# AK4493-Combi.net
KiCad netlist of a schematic drawn in EAGLE
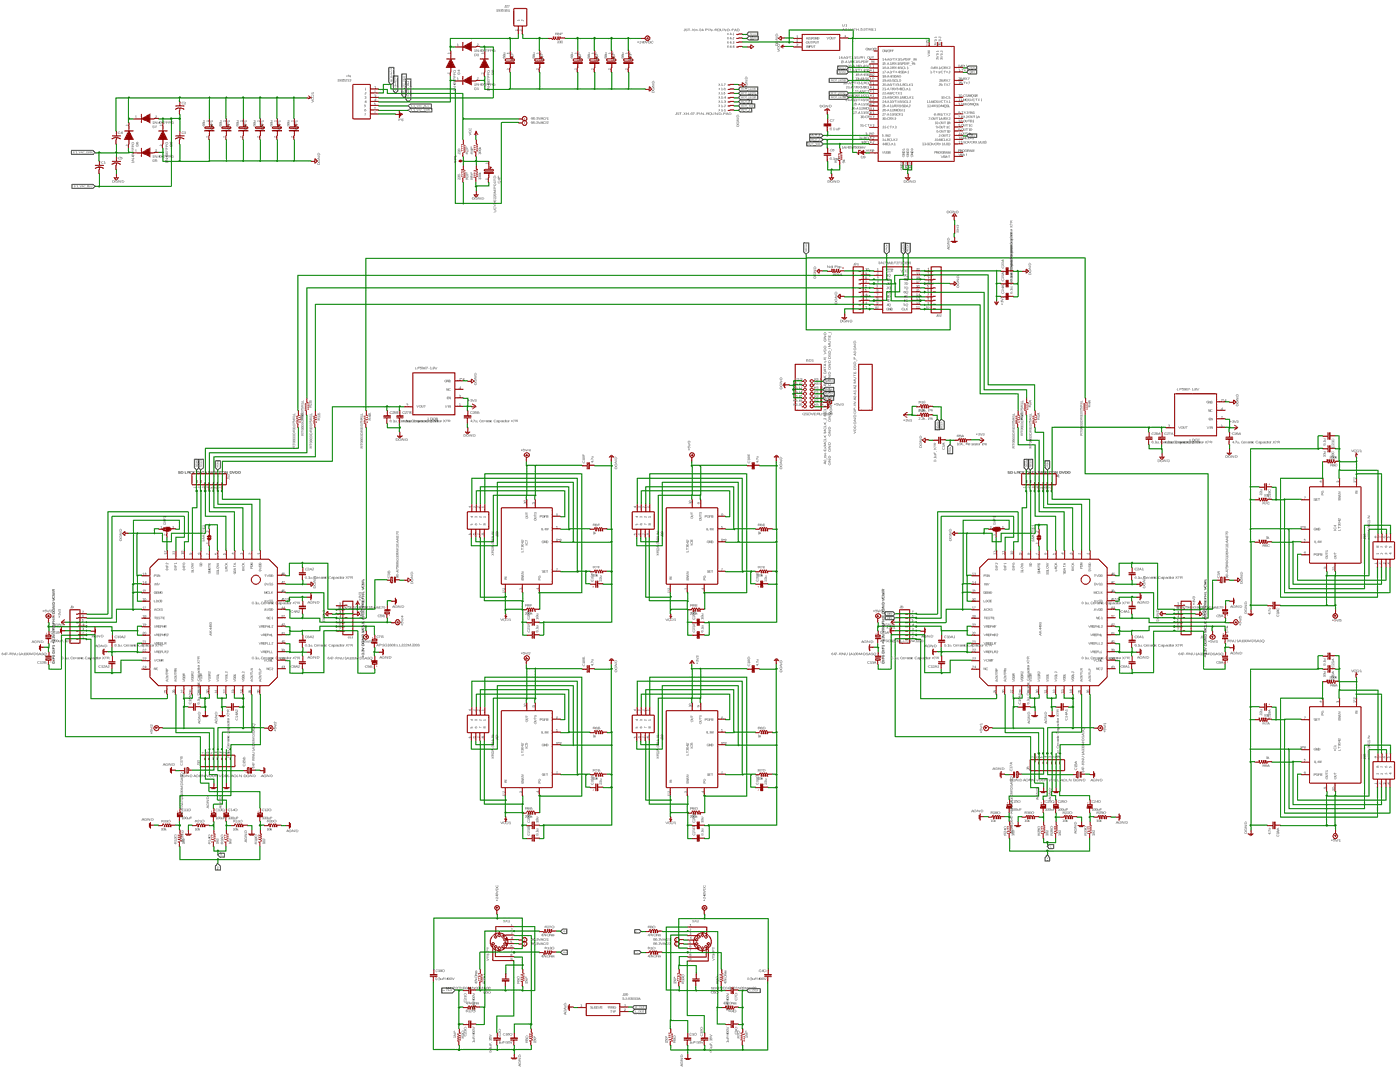
[diagram p0: schematic, sheet 1, overview]
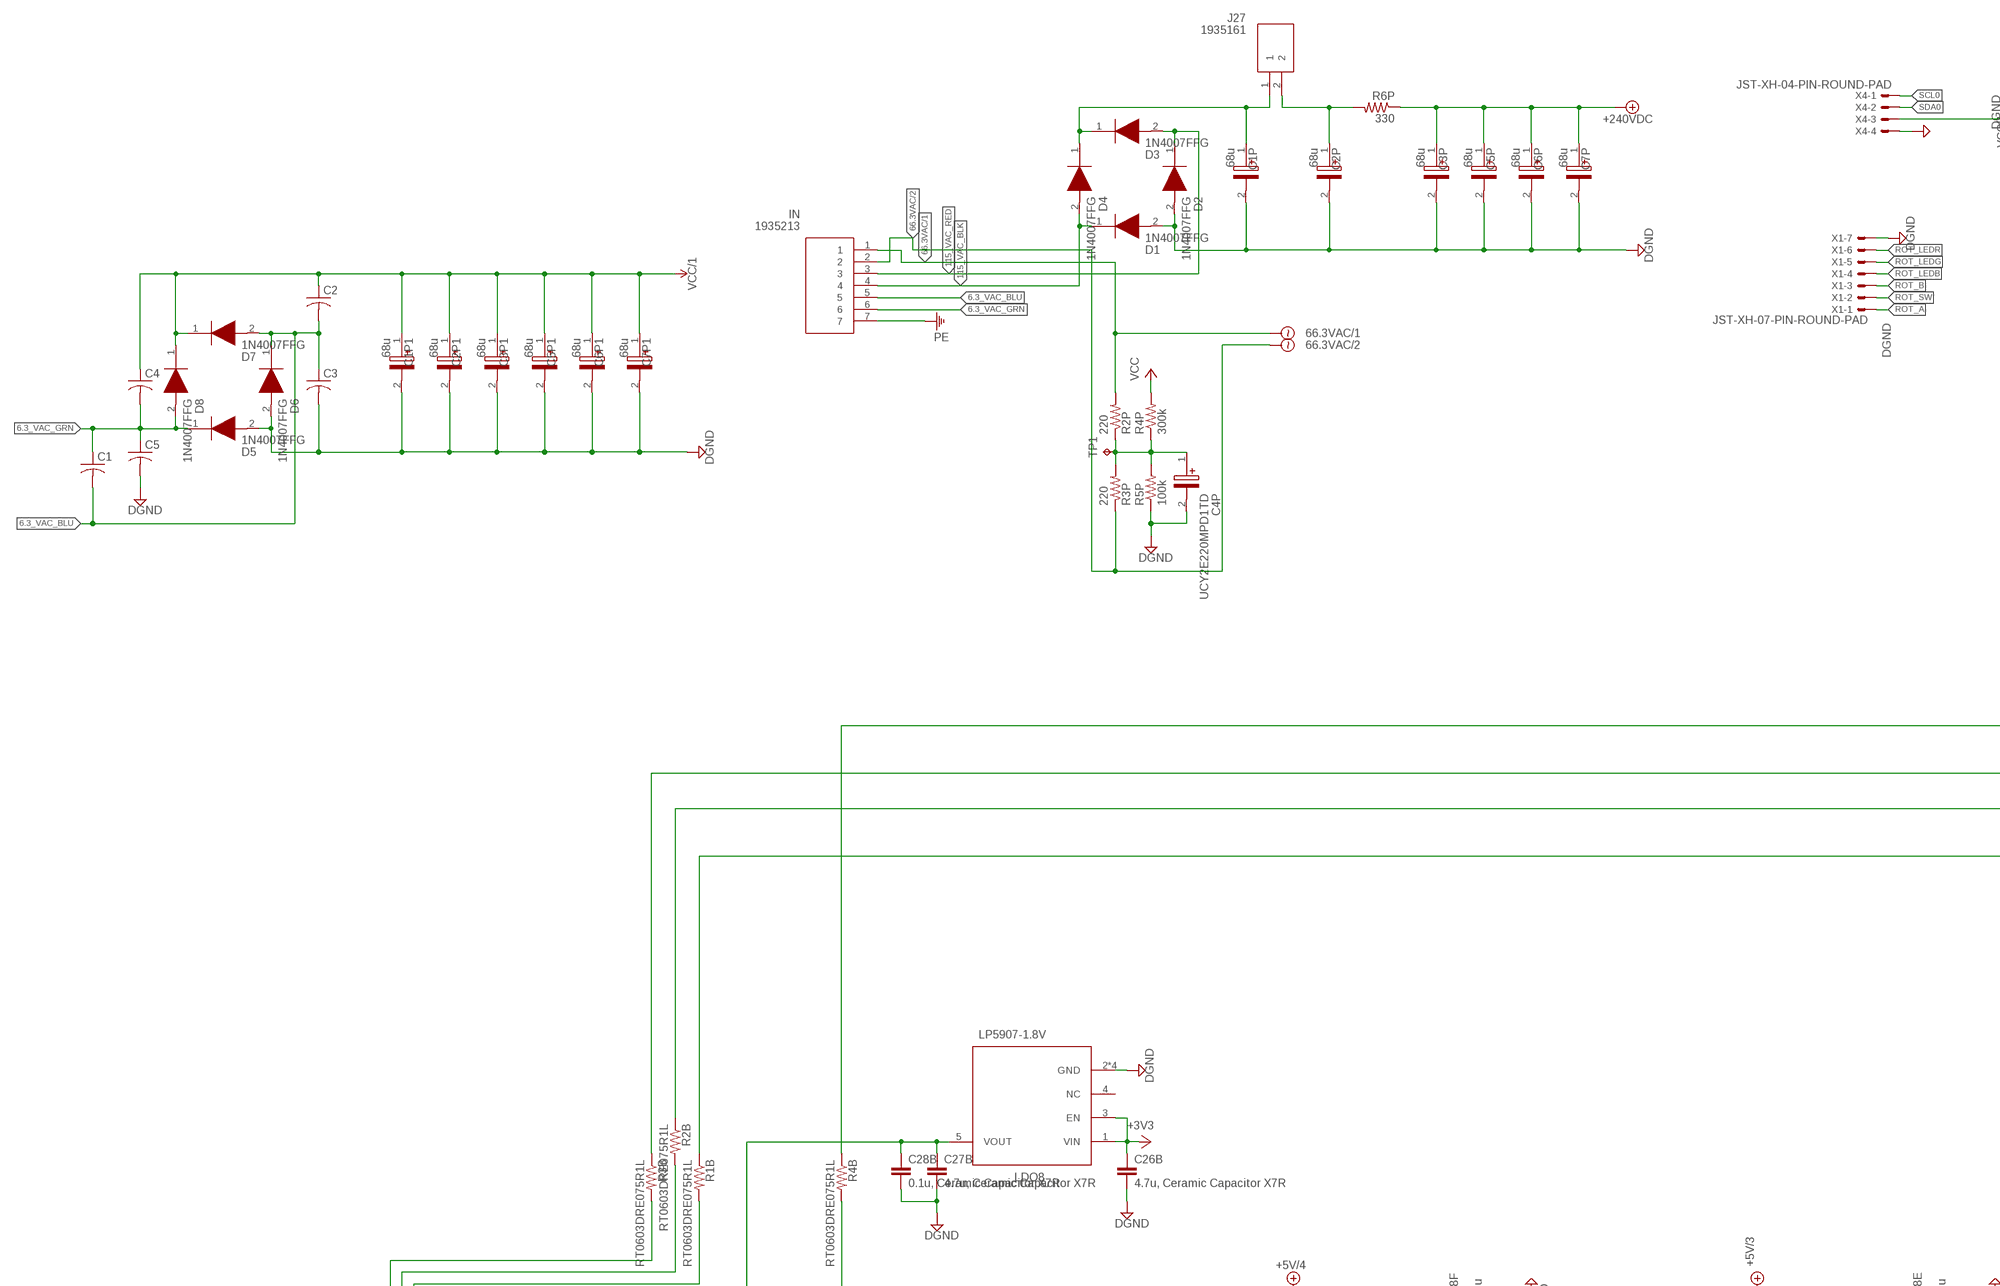
[diagram p1: schematic, sheet 1, part 1 of 4]
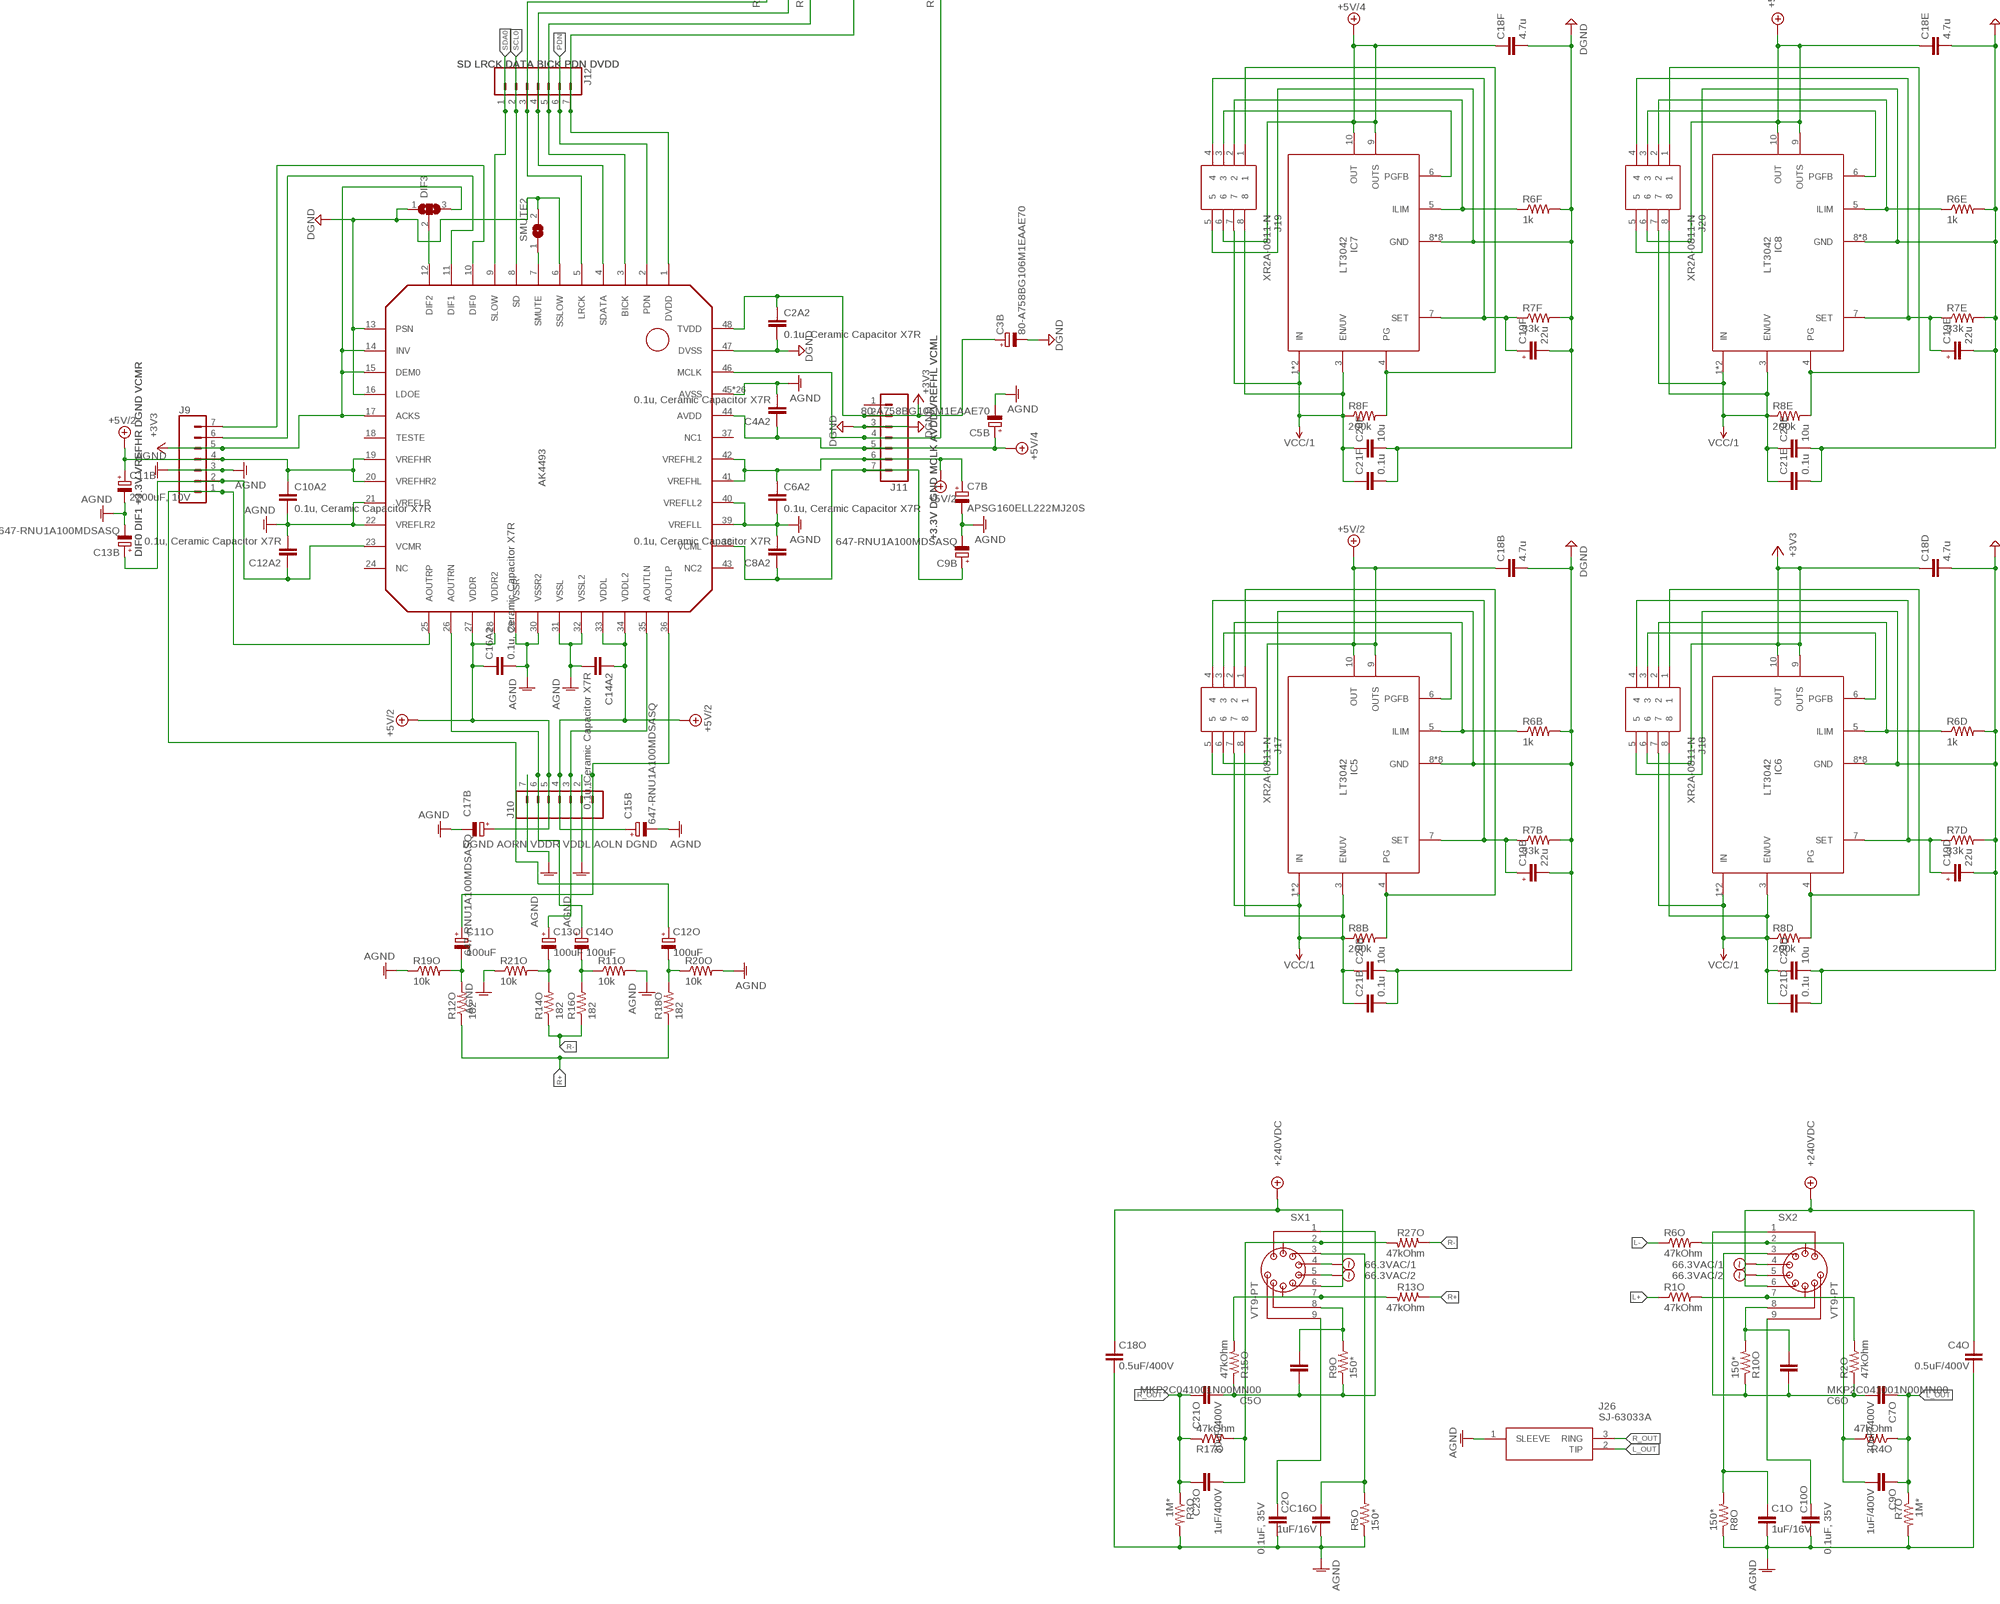
[diagram p2: schematic, sheet 1, part 2 of 4]
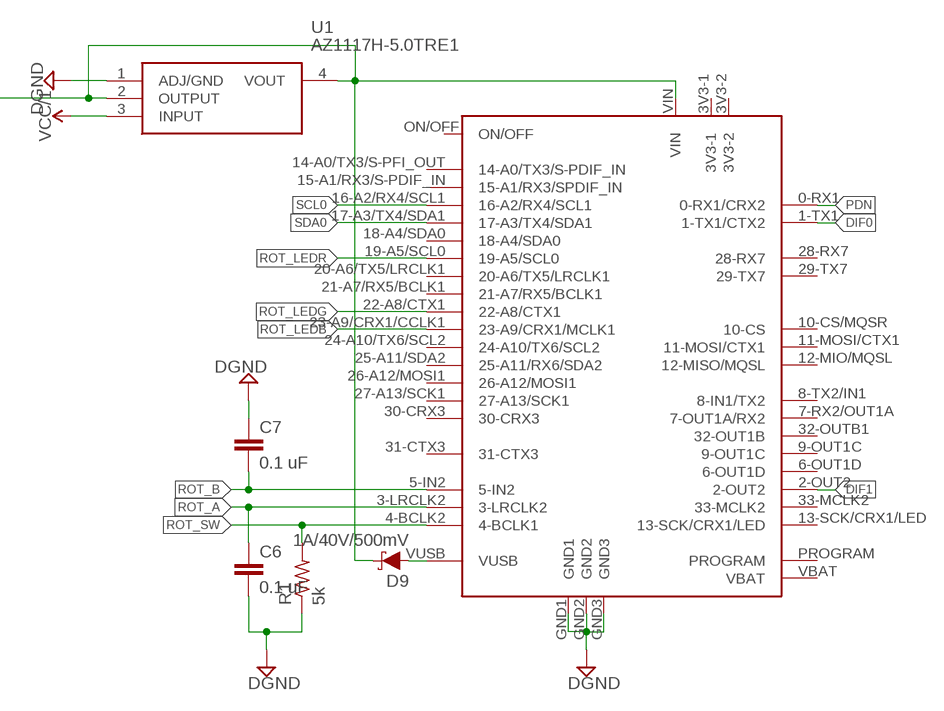
[diagram p3: schematic, sheet 1, part 3 of 4]
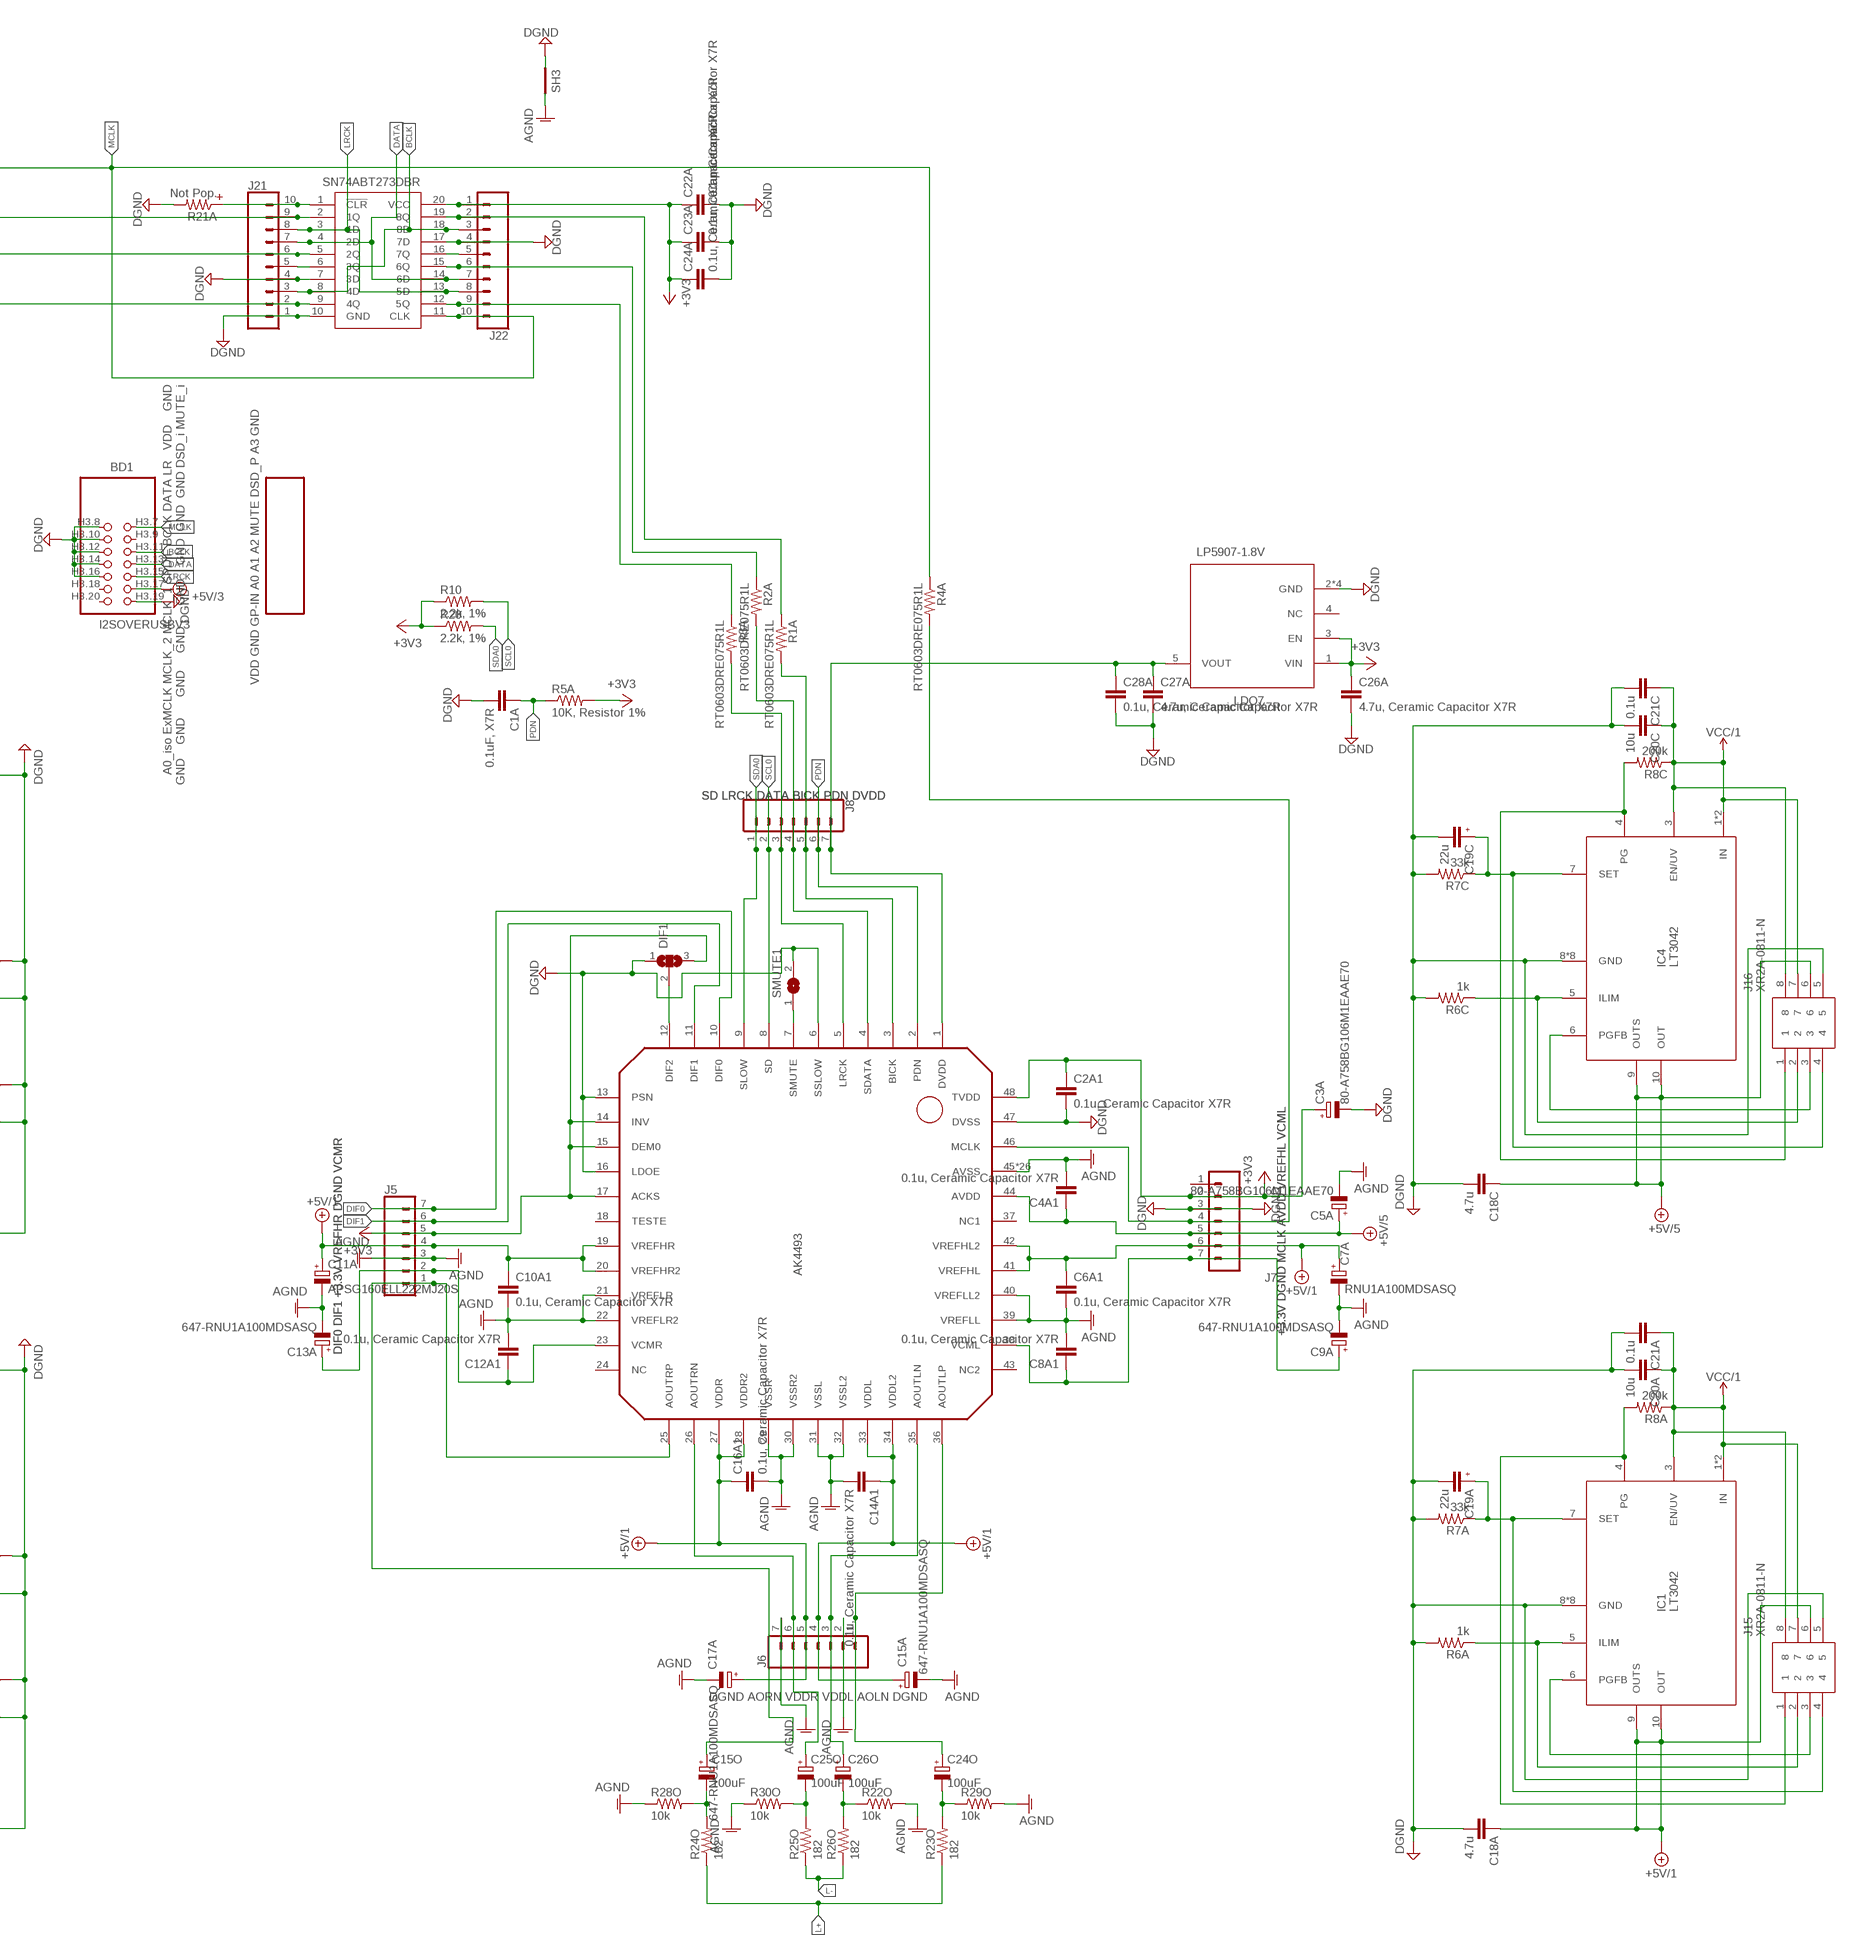
[diagram p4: schematic, sheet 1, part 4 of 4]

(export (version "E")
  (design (tool "Eeschema 10.0.6"))
  (components
    (comp (ref "BD1")
      (value "I2SOVERUSBV3")
      (footprint "eagle-import:I2SOVERUSBV3")
      (libsource (lib "eagle-import") (part "I2SOVERUSBV3"))
    )
    (comp (ref "C1")
      (value "C-US075-032X103")
      (footprint "eagle-import:C075-032X103")
      (libsource (lib "eagle-import") (part "C-US075-032X103"))
    )
    (comp (ref "C1A")
      (value "0.1uF, X7R")
      (footprint "eagle-import:CAPC2012X135N")
      (fields
        (field (name "MANUFACTURER_PART_NUMBER") "EMF212B7104KGHT")
        (field (name "MOUSER_PART_NUMBER") "963-EMF212B7104KGHT")
      )
      (libsource (lib "eagle-import") (part "EMF212B7104KGHT"))
    )
    (comp (ref "C1O")
      (value "1uF/16V")
      (footprint "eagle-import:MKP2C041001N00MN00")
      (fields
        (field (name "MANUFACTURER_PART_NUMBER") "MKP2C041001N00MN00")
        (field (name "MOUSER_PART_NUMBER") "505-MKP2C0411NMN")
      )
      (libsource (lib "eagle-import") (part "MKP2C041001N00MN00"))
    )
    (comp (ref "C1P")
      (value "68u")
      (footprint "eagle-import:CAPPRD750W80D1475H4700")
      (fields (field (name "MANUFACTURER_PART_NUMBER") "500HXW68MEFR14.5X45"))
      (libsource (lib "eagle-import") (part "500HXW68MEFR14.5X45"))
    )
    (comp (ref "C1P1")
      (value "68u")
      (footprint "eagle-import:CAPPRD750W80D1475H4700")
      (fields (field (name "MANUFACTURER_PART_NUMBER") "500HXW68MEFR14.5X45"))
      (libsource (lib "eagle-import") (part "500HXW68MEFR14.5X45"))
    )
    (comp (ref "C2")
      (value "C-US075-032X103")
      (footprint "eagle-import:C075-032X103")
      (libsource (lib "eagle-import") (part "C-US075-032X103"))
    )
    (comp (ref "C2A1")
      (value "0.1u, Ceramic Capacitor X7R")
      (footprint "eagle-import:CAPC1608X95N")
      (fields
        (field (name "MANUFACTURER_PART_NUMBER") "EMK107B7104KA-T")
        (field (name "MOUSER_PART_NUMBER") "963-EMK107B7104KA-T")
      )
      (libsource (lib "eagle-import") (part "EMK107B7104KA-T"))
    )
    (comp (ref "C2A2")
      (value "0.1u, Ceramic Capacitor X7R")
      (footprint "eagle-import:CAPC1608X95N")
      (fields
        (field (name "MANUFACTURER_PART_NUMBER") "EMK107B7104KA-T")
        (field (name "MOUSER_PART_NUMBER") "963-EMK107B7104KA-T")
      )
      (libsource (lib "eagle-import") (part "EMK107B7104KA-T"))
    )
    (comp (ref "C2O")
      (value "0.1uF, 35V")
      (footprint "eagle-import:MKS4B031002A00JC00")
      (fields
        (field (name "MANUFACTURER_PART_NUMBER") "MKS4B031002A00JC00")
        (field (name "MOUSER_PART_NUMBER") "505-MKS4B0312AJC")
      )
      (libsource (lib "eagle-import") (part "MKS4B031002A00JC00"))
    )
    (comp (ref "C2P")
      (value "68u")
      (footprint "eagle-import:CAPPRD750W80D1475H4700")
      (fields (field (name "MANUFACTURER_PART_NUMBER") "500HXW68MEFR14.5X45"))
      (libsource (lib "eagle-import") (part "500HXW68MEFR14.5X45"))
    )
    (comp (ref "C2P1")
      (value "68u")
      (footprint "eagle-import:CAPPRD750W80D1475H4700")
      (fields (field (name "MANUFACTURER_PART_NUMBER") "500HXW68MEFR14.5X45"))
      (libsource (lib "eagle-import") (part "500HXW68MEFR14.5X45"))
    )
    (comp (ref "C3")
      (value "C-US075-032X103")
      (footprint "eagle-import:C075-032X103")
      (libsource (lib "eagle-import") (part "C-US075-032X103"))
    )
    (comp (ref "C3A")
      (value "80-A758BG106M1EAAE70")
      (footprint "eagle-import:CAPPRD150W45D450H600")
      (fields
        (field (name "MANUFACTURER_PART_NUMBER") "RNU1A100MDSASQ")
        (field (name "MOUSER_PART_NUMBER") "647-RNU1A100MDSASQ")
      )
      (libsource (lib "eagle-import") (part "RNU1A100MDSASQ"))
    )
    (comp (ref "C3B")
      (value "80-A758BG106M1EAAE70")
      (footprint "eagle-import:CAPPRD200W55D500H800")
      (fields (field (name "MANUFACTURER_PART_NUMBER") "A758BG106M1EAAE070"))
      (libsource (lib "eagle-import") (part "A758BG106M1EAAE070"))
    )
    (comp (ref "C3P")
      (value "68u")
      (footprint "eagle-import:CAPPRD750W80D1475H4700")
      (fields (field (name "MANUFACTURER_PART_NUMBER") "500HXW68MEFR14.5X45"))
      (libsource (lib "eagle-import") (part "500HXW68MEFR14.5X45"))
    )
    (comp (ref "C3P1")
      (value "68u")
      (footprint "eagle-import:CAPPRD750W80D1475H4700")
      (fields (field (name "MANUFACTURER_PART_NUMBER") "500HXW68MEFR14.5X45"))
      (libsource (lib "eagle-import") (part "500HXW68MEFR14.5X45"))
    )
    (comp (ref "C4")
      (value "C-US075-032X103")
      (footprint "eagle-import:C075-032X103")
      (libsource (lib "eagle-import") (part "C-US075-032X103"))
    )
    (comp (ref "C4A1")
      (value "0.1u, Ceramic Capacitor X7R")
      (footprint "eagle-import:CAPC1608X95N")
      (fields
        (field (name "MANUFACTURER_PART_NUMBER") "EMK107B7104KA-T")
        (field (name "MOUSER_PART_NUMBER") "963-EMK107B7104KA-T")
      )
      (libsource (lib "eagle-import") (part "EMK107B7104KA-T"))
    )
    (comp (ref "C4A2")
      (value "0.1u, Ceramic Capacitor X7R")
      (footprint "eagle-import:CAPC1608X95N")
      (fields
        (field (name "MANUFACTURER_PART_NUMBER") "EMK107B7104KA-T")
        (field (name "MOUSER_PART_NUMBER") "963-EMK107B7104KA-T")
      )
      (libsource (lib "eagle-import") (part "EMK107B7104KA-T"))
    )
    (comp (ref "C4O")
      (value "0.5uF/400V")
      (footprint "eagle-import:MKP4G034705D00KSSD")
      (fields
        (field (name "MANUFACTURER_PART_NUMBER") "MKP4G034705D00KSSD")
        (field (name "MOUSER_PART_NUMBER") "505-MKP4G034705DKSSD")
      )
      (libsource (lib "eagle-import") (part "MKP4G034705D00KSSD"))
    )
    (comp (ref "C4P")
      (value "UCY2E220MPD1TD")
      (footprint "eagle-import:CAPPRD500W60D1025H1750")
      (fields (field (name "MOUSER_PART_NUMBER") "647-UCY2E220MPD1TD"))
      (libsource (lib "eagle-import") (part "UCY2E220MPD1TD"))
    )
    (comp (ref "C5")
      (value "C-US075-032X103")
      (footprint "eagle-import:C075-032X103")
      (libsource (lib "eagle-import") (part "C-US075-032X103"))
    )
    (comp (ref "C5A")
      (value "80-A758BG106M1EAAE70")
      (footprint "eagle-import:CAPPRD200W55D500H800")
      (fields (field (name "MANUFACTURER_PART_NUMBER") "A758BG106M1EAAE070"))
      (libsource (lib "eagle-import") (part "A758BG106M1EAAE070"))
    )
    (comp (ref "C5B")
      (value "80-A758BG106M1EAAE70")
      (footprint "eagle-import:CAPPRD200W55D500H800")
      (fields (field (name "MANUFACTURER_PART_NUMBER") "A758BG106M1EAAE070"))
      (libsource (lib "eagle-import") (part "A758BG106M1EAAE070"))
    )
    (comp (ref "C5O")
      (value "MKP2C041001N00MN00")
      (footprint "eagle-import:MKP2C041001N00MN00")
      (fields (field (name "MOUSER_PART_NUMBER") "505-MKP2C0411NMN"))
      (libsource (lib "eagle-import") (part "MKP2C041001N00MN00"))
    )
    (comp (ref "C5P")
      (value "68u")
      (footprint "eagle-import:CAPPRD750W80D1475H4700")
      (fields (field (name "MANUFACTURER_PART_NUMBER") "500HXW68MEFR14.5X45"))
      (libsource (lib "eagle-import") (part "500HXW68MEFR14.5X45"))
    )
    (comp (ref "C5P1")
      (value "68u")
      (footprint "eagle-import:CAPPRD750W80D1475H4700")
      (fields (field (name "MANUFACTURER_PART_NUMBER") "500HXW68MEFR14.5X45"))
      (libsource (lib "eagle-import") (part "500HXW68MEFR14.5X45"))
    )
    (comp (ref "C6")
      (value "0.1 uF")
      (footprint "eagle-import:C0603")
      (libsource (lib "eagle-import") (part "C0603"))
    )
    (comp (ref "C6A1")
      (value "0.1u, Ceramic Capacitor X7R")
      (footprint "eagle-import:CAPC1608X95N")
      (fields
        (field (name "MANUFACTURER_PART_NUMBER") "EMK107B7104KA-T")
        (field (name "MOUSER_PART_NUMBER") "963-EMK107B7104KA-T")
      )
      (libsource (lib "eagle-import") (part "EMK107B7104KA-T"))
    )
    (comp (ref "C6A2")
      (value "0.1u, Ceramic Capacitor X7R")
      (footprint "eagle-import:CAPC1608X95N")
      (fields
        (field (name "MANUFACTURER_PART_NUMBER") "EMK107B7104KA-T")
        (field (name "MOUSER_PART_NUMBER") "963-EMK107B7104KA-T")
      )
      (libsource (lib "eagle-import") (part "EMK107B7104KA-T"))
    )
    (comp (ref "C6O")
      (value "MKP2C041001N00MN00")
      (footprint "eagle-import:MKP2C041001N00MN00")
      (fields (field (name "MOUSER_PART_NUMBER") "505-MKP2C0411NMN"))
      (libsource (lib "eagle-import") (part "MKP2C041001N00MN00"))
    )
    (comp (ref "C6P")
      (value "68u")
      (footprint "eagle-import:CAPPRD750W80D1475H4700")
      (fields (field (name "MANUFACTURER_PART_NUMBER") "500HXW68MEFR14.5X45"))
      (libsource (lib "eagle-import") (part "500HXW68MEFR14.5X45"))
    )
    (comp (ref "C6P1")
      (value "68u")
      (footprint "eagle-import:CAPPRD750W80D1475H4700")
      (fields (field (name "MANUFACTURER_PART_NUMBER") "500HXW68MEFR14.5X45"))
      (libsource (lib "eagle-import") (part "500HXW68MEFR14.5X45"))
    )
    (comp (ref "C7")
      (value "0.1 uF")
      (footprint "eagle-import:C0603")
      (libsource (lib "eagle-import") (part "C0603"))
    )
    (comp (ref "C7A")
      (value "RNU1A100MDSASQ")
      (footprint "eagle-import:CAPPRD150W45D450H600")
      (fields (field (name "MOUSER_PART_NUMBER") "647-RNU1A100MDSASQ"))
      (libsource (lib "eagle-import") (part "RNU1A100MDSASQ"))
    )
    (comp (ref "C7B")
      (value "APSG160ELL222MJ20S")
      (footprint "eagle-import:CAPPRD500W60D1025H2150")
      (fields (field (name "MOUSER_PART_NUMBER") "661-APSG160E222MJ20S"))
      (libsource (lib "eagle-import") (part "APSG160ELL222MJ20S"))
    )
    (comp (ref "C7O")
      (value "30uF/400V")
      (footprint "eagle-import:DCP4G053006ID2KSSD")
      (fields
        (field (name "MANUFACTURER_PART_NUMBER") "DCP4G053006ID2KSSD")
        (field (name "MOUSER_PART_NUMBER") "505-DCP4G0536ID2KSSD")
      )
      (libsource (lib "eagle-import") (part "DCP4G053006ID2KSSD"))
    )
    (comp (ref "C7P")
      (value "68u")
      (footprint "eagle-import:CAPPRD750W80D1475H4700")
      (fields (field (name "MANUFACTURER_PART_NUMBER") "500HXW68MEFR14.5X45"))
      (libsource (lib "eagle-import") (part "500HXW68MEFR14.5X45"))
    )
    (comp (ref "C7P1")
      (value "68u")
      (footprint "eagle-import:CAPPRD750W80D1475H4700")
      (fields (field (name "MANUFACTURER_PART_NUMBER") "500HXW68MEFR14.5X45"))
      (libsource (lib "eagle-import") (part "500HXW68MEFR14.5X45"))
    )
    (comp (ref "C8A1")
      (value "0.1u, Ceramic Capacitor X7R")
      (footprint "eagle-import:CAPC1608X95N")
      (fields
        (field (name "MANUFACTURER_PART_NUMBER") "EMK107B7104KA-T")
        (field (name "MOUSER_PART_NUMBER") "963-EMK107B7104KA-T")
      )
      (libsource (lib "eagle-import") (part "EMK107B7104KA-T"))
    )
    (comp (ref "C8A2")
      (value "0.1u, Ceramic Capacitor X7R")
      (footprint "eagle-import:CAPC1608X95N")
      (fields
        (field (name "MANUFACTURER_PART_NUMBER") "EMK107B7104KA-T")
        (field (name "MOUSER_PART_NUMBER") "963-EMK107B7104KA-T")
      )
      (libsource (lib "eagle-import") (part "EMK107B7104KA-T"))
    )
    (comp (ref "C9A")
      (value "647-RNU1A100MDSASQ")
      (footprint "eagle-import:CAPPRD150W45D450H600")
      (fields (field (name "MANUFACTURER_PART_NUMBER") "RNU1A100MDSASQ"))
      (libsource (lib "eagle-import") (part "RNU1A100MDSASQ"))
    )
    (comp (ref "C9B")
      (value "647-RNU1A100MDSASQ")
      (footprint "eagle-import:CAPPRD150W45D450H600")
      (fields (field (name "MANUFACTURER_PART_NUMBER") "RNU1A100MDSASQ"))
      (libsource (lib "eagle-import") (part "RNU1A100MDSASQ"))
    )
    (comp (ref "C9O")
      (value "1uF/400V")
      (footprint "eagle-import:MKP4G041005I00JSSD")
      (fields
        (field (name "MANUFACTURER_PART_NUMBER") "MKP4G041005I00JSSD")
        (field (name "MOUSER_PART_NUMBER") "505-MKP4G041005I00JS")
      )
      (libsource (lib "eagle-import") (part "MKP4G041005I00JSSD"))
    )
    (comp (ref "C10A1")
      (value "0.1u, Ceramic Capacitor X7R")
      (footprint "eagle-import:CAPC1608X95N")
      (fields
        (field (name "MANUFACTURER_PART_NUMBER") "EMK107B7104KA-T")
        (field (name "MOUSER_PART_NUMBER") "963-EMK107B7104KA-T")
      )
      (libsource (lib "eagle-import") (part "EMK107B7104KA-T"))
    )
    (comp (ref "C10A2")
      (value "0.1u, Ceramic Capacitor X7R")
      (footprint "eagle-import:CAPC1608X95N")
      (fields
        (field (name "MANUFACTURER_PART_NUMBER") "EMK107B7104KA-T")
        (field (name "MOUSER_PART_NUMBER") "963-EMK107B7104KA-T")
      )
      (libsource (lib "eagle-import") (part "EMK107B7104KA-T"))
    )
    (comp (ref "C10O")
      (value "0.1uF, 35V")
      (footprint "eagle-import:MKS4B031002A00JC00")
      (fields
        (field (name "MANUFACTURER_PART_NUMBER") "MKS4B031002A00JC00")
        (field (name "MOUSER_PART_NUMBER") "505-MKS4B0312AJC")
      )
      (libsource (lib "eagle-import") (part "MKS4B031002A00JC00"))
    )
    (comp (ref "C11A")
      (value "APSG160ELL222MJ20S")
      (footprint "eagle-import:CAPPRD500W60D1025H2150")
      (fields (field (name "MOUSER_PART_NUMBER") "661-APSG160E222MJ20S"))
      (libsource (lib "eagle-import") (part "APSG160ELL222MJ20S"))
    )
    (comp (ref "C11B")
      (value "2200uF, 10V")
      (footprint "eagle-import:CAPPRD500W60D1025H2150")
      (fields
        (field (name "MANUFACTURER_PART_NUMBER") "APSG160ELL222MJ20S")
        (field (name "MOUSER_PART_NUMBER") "661-APSG160E222MJ20S")
      )
      (libsource (lib "eagle-import") (part "APSG160ELL222MJ20S"))
    )
    (comp (ref "C11O")
      (value "100uF")
      (footprint "eagle-import:CAPPRD350W60D825H1300")
      (fields
        (field (name "ARROW_PART_NUMBER") "UFW1H101MPD1TD")
        (field (name "MOUSER_PART_NUMBER") "647-UFW1H101MPD1TD")
      )
      (libsource (lib "eagle-import") (part "UFW1H101MPD1TD"))
    )
    (comp (ref "C12A1")
      (value "0.1u, Ceramic Capacitor X7R")
      (footprint "eagle-import:CAPC1608X95N")
      (fields
        (field (name "MANUFACTURER_PART_NUMBER") "EMK107B7104KA-T")
        (field (name "MOUSER_PART_NUMBER") "963-EMK107B7104KA-T")
      )
      (libsource (lib "eagle-import") (part "EMK107B7104KA-T"))
    )
    (comp (ref "C12A2")
      (value "0.1u, Ceramic Capacitor X7R")
      (footprint "eagle-import:CAPC1608X95N")
      (fields
        (field (name "MANUFACTURER_PART_NUMBER") "EMK107B7104KA-T")
        (field (name "MOUSER_PART_NUMBER") "963-EMK107B7104KA-T")
      )
      (libsource (lib "eagle-import") (part "EMK107B7104KA-T"))
    )
    (comp (ref "C12O")
      (value "100uF")
      (footprint "eagle-import:CAPPRD350W60D825H1300")
      (fields
        (field (name "ARROW_PART_NUMBER") "UFW1H101MPD1TD")
        (field (name "MOUSER_PART_NUMBER") "647-UFW1H101MPD1TD")
      )
      (libsource (lib "eagle-import") (part "UFW1H101MPD1TD"))
    )
    (comp (ref "C13A")
      (value "647-RNU1A100MDSASQ")
      (footprint "eagle-import:CAPPRD150W45D450H600")
      (fields (field (name "MANUFACTURER_PART_NUMBER") "RNU1A100MDSASQ"))
      (libsource (lib "eagle-import") (part "RNU1A100MDSASQ"))
    )
    (comp (ref "C13B")
      (value "647-RNU1A100MDSASQ")
      (footprint "eagle-import:CAPPRD150W45D450H600")
      (fields (field (name "MANUFACTURER_PART_NUMBER") "RNU1A100MDSASQ"))
      (libsource (lib "eagle-import") (part "RNU1A100MDSASQ"))
    )
    (comp (ref "C13O")
      (value "100uF")
      (footprint "eagle-import:CAPPRD350W60D825H1300")
      (fields
        (field (name "ARROW_PART_NUMBER") "UFW1H101MPD1TD")
        (field (name "MOUSER_PART_NUMBER") "647-UFW1H101MPD1TD")
      )
      (libsource (lib "eagle-import") (part "UFW1H101MPD1TD"))
    )
    (comp (ref "C14A1")
      (value "0.1u, Ceramic Capacitor X7R")
      (footprint "eagle-import:CAPC1608X95N")
      (fields
        (field (name "MANUFACTURER_PART_NUMBER") "EMK107B7104KA-T")
        (field (name "MOUSER_PART_NUMBER") "963-EMK107B7104KA-T")
      )
      (libsource (lib "eagle-import") (part "EMK107B7104KA-T"))
    )
    (comp (ref "C14A2")
      (value "0.1u, Ceramic Capacitor X7R")
      (footprint "eagle-import:CAPC1608X95N")
      (fields
        (field (name "MANUFACTURER_PART_NUMBER") "EMK107B7104KA-T")
        (field (name "MOUSER_PART_NUMBER") "963-EMK107B7104KA-T")
      )
      (libsource (lib "eagle-import") (part "EMK107B7104KA-T"))
    )
    (comp (ref "C14O")
      (value "100uF")
      (footprint "eagle-import:CAPPRD350W60D825H1300")
      (fields
        (field (name "ARROW_PART_NUMBER") "UFW1H101MPD1TD")
        (field (name "MOUSER_PART_NUMBER") "647-UFW1H101MPD1TD")
      )
      (libsource (lib "eagle-import") (part "UFW1H101MPD1TD"))
    )
    (comp (ref "C15A")
      (value "647-RNU1A100MDSASQ")
      (footprint "eagle-import:CAPPRD150W45D450H600")
      (fields (field (name "MANUFACTURER_PART_NUMBER") "RNU1A100MDSASQ"))
      (libsource (lib "eagle-import") (part "RNU1A100MDSASQ"))
    )
    (comp (ref "C15B")
      (value "647-RNU1A100MDSASQ")
      (footprint "eagle-import:CAPPRD150W45D450H600")
      (fields (field (name "MANUFACTURER_PART_NUMBER") "RNU1A100MDSASQ"))
      (libsource (lib "eagle-import") (part "RNU1A100MDSASQ"))
    )
    (comp (ref "C15O")
      (value "100uF")
      (footprint "eagle-import:CAPPRD350W60D825H1300")
      (fields
        (field (name "ARROW_PART_NUMBER") "UFW1H101MPD1TD")
        (field (name "MOUSER_PART_NUMBER") "647-UFW1H101MPD1TD")
      )
      (libsource (lib "eagle-import") (part "UFW1H101MPD1TD"))
    )
    (comp (ref "C16A1")
      (value "0.1u, Ceramic Capacitor X7R")
      (footprint "eagle-import:CAPC1608X95N")
      (fields
        (field (name "MANUFACTURER_PART_NUMBER") "EMK107B7104KA-T")
        (field (name "MOUSER_PART_NUMBER") "963-EMK107B7104KA-T")
      )
      (libsource (lib "eagle-import") (part "EMK107B7104KA-T"))
    )
    (comp (ref "C16A2")
      (value "0.1u, Ceramic Capacitor X7R")
      (footprint "eagle-import:CAPC1608X95N")
      (fields
        (field (name "MANUFACTURER_PART_NUMBER") "EMK107B7104KA-T")
        (field (name "MOUSER_PART_NUMBER") "963-EMK107B7104KA-T")
      )
      (libsource (lib "eagle-import") (part "EMK107B7104KA-T"))
    )
    (comp (ref "C16O")
      (value "1uF/16V")
      (footprint "eagle-import:MKP2C041001N00MN00")
      (fields
        (field (name "MANUFACTURER_PART_NUMBER") "MKP2C041001N00MN00")
        (field (name "MOUSER_PART_NUMBER") "505-MKP2C0411NMN")
      )
      (libsource (lib "eagle-import") (part "MKP2C041001N00MN00"))
    )
    (comp (ref "C17A")
      (value "647-RNU1A100MDSASQ")
      (footprint "eagle-import:CAPPRD150W45D450H600")
      (fields (field (name "MANUFACTURER_PART_NUMBER") "RNU1A100MDSASQ"))
      (libsource (lib "eagle-import") (part "RNU1A100MDSASQ"))
    )
    (comp (ref "C17B")
      (value "647-RNU1A100MDSASQ")
      (footprint "eagle-import:CAPPRD150W45D450H600")
      (fields (field (name "MANUFACTURER_PART_NUMBER") "RNU1A100MDSASQ"))
      (libsource (lib "eagle-import") (part "RNU1A100MDSASQ"))
    )
    (comp (ref "C18A")
      (value "4.7u")
      (footprint "eagle-import:CAPC2013X140N")
      (fields
        (field (name "MANUFACTURER_PART_NUMBER") "EMK212ABJ475KG-T")
        (field (name "MOUSER_PART_NUMBER") "963-EMK212ABJ475KG-T")
      )
      (libsource (lib "eagle-import") (part "EMK212ABJ475KG-T"))
    )
    (comp (ref "C18B")
      (value "4.7u")
      (footprint "eagle-import:CAPC2013X140N")
      (fields
        (field (name "MANUFACTURER_PART_NUMBER") "EMK212ABJ475KG-T")
        (field (name "MOUSER_PART_NUMBER") "963-EMK212ABJ475KG-T")
      )
      (libsource (lib "eagle-import") (part "EMK212ABJ475KG-T"))
    )
    (comp (ref "C18C")
      (value "4.7u")
      (footprint "eagle-import:CAPC2013X140N")
      (fields
        (field (name "MANUFACTURER_PART_NUMBER") "EMK212ABJ475KG-T")
        (field (name "MOUSER_PART_NUMBER") "963-EMK212ABJ475KG-T")
      )
      (libsource (lib "eagle-import") (part "EMK212ABJ475KG-T"))
    )
    (comp (ref "C18D")
      (value "4.7u")
      (footprint "eagle-import:CAPC2013X140N")
      (fields
        (field (name "MANUFACTURER_PART_NUMBER") "EMK212ABJ475KG-T")
        (field (name "MOUSER_PART_NUMBER") "963-EMK212ABJ475KG-T")
      )
      (libsource (lib "eagle-import") (part "EMK212ABJ475KG-T"))
    )
    (comp (ref "C18E")
      (value "4.7u")
      (footprint "eagle-import:CAPC2013X140N")
      (fields
        (field (name "MANUFACTURER_PART_NUMBER") "EMK212ABJ475KG-T")
        (field (name "MOUSER_PART_NUMBER") "963-EMK212ABJ475KG-T")
      )
      (libsource (lib "eagle-import") (part "EMK212ABJ475KG-T"))
    )
    (comp (ref "C18F")
      (value "4.7u")
      (footprint "eagle-import:CAPC2013X140N")
      (fields
        (field (name "MANUFACTURER_PART_NUMBER") "EMK212ABJ475KG-T")
        (field (name "MOUSER_PART_NUMBER") "963-EMK212ABJ475KG-T")
      )
      (libsource (lib "eagle-import") (part "EMK212ABJ475KG-T"))
    )
    (comp (ref "C18O")
      (value "0.5uF/400V")
      (footprint "eagle-import:MKP4G034705D00KSSD")
      (fields
        (field (name "MANUFACTURER_PART_NUMBER") "MKP4G034705D00KSSD")
        (field (name "MOUSER_PART_NUMBER") "505-MKP4G034705DKSSD")
      )
      (libsource (lib "eagle-import") (part "MKP4G034705D00KSSD"))
    )
    (comp (ref "C19A")
      (value "22u")
      (footprint "eagle-import:C1206")
      (fields
        (field (name "MANUFACTURER_PART_NUMBER") "EMK316BB7226ML-T")
        (field (name "MOUSER_PART_NUMBER") "963-EMK316BB7226ML-T")
      )
      (libsource (lib "eagle-import") (part "EMK316BB7226ML-T"))
    )
    (comp (ref "C19B")
      (value "22u")
      (footprint "eagle-import:C1206")
      (fields
        (field (name "MANUFACTURER_PART_NUMBER") "EMK316BB7226ML-T")
        (field (name "MOUSER_PART_NUMBER") "963-EMK316BB7226ML-T")
      )
      (libsource (lib "eagle-import") (part "EMK316BB7226ML-T"))
    )
    (comp (ref "C19C")
      (value "22u")
      (footprint "eagle-import:C1206")
      (fields
        (field (name "MANUFACTURER_PART_NUMBER") "EMK316BB7226ML-T")
        (field (name "MOUSER_PART_NUMBER") "963-EMK316BB7226ML-T")
      )
      (libsource (lib "eagle-import") (part "EMK316BB7226ML-T"))
    )
    (comp (ref "C19D")
      (value "22u")
      (footprint "eagle-import:C1206")
      (fields
        (field (name "MANUFACTURER_PART_NUMBER") "EMK316BB7226ML-T")
        (field (name "MOUSER_PART_NUMBER") "963-EMK316BB7226ML-T")
      )
      (libsource (lib "eagle-import") (part "EMK316BB7226ML-T"))
    )
    (comp (ref "C19E")
      (value "22u")
      (footprint "eagle-import:C1206")
      (fields
        (field (name "MANUFACTURER_PART_NUMBER") "EMK316BB7226ML-T")
        (field (name "MOUSER_PART_NUMBER") "963-EMK316BB7226ML-T")
      )
      (libsource (lib "eagle-import") (part "EMK316BB7226ML-T"))
    )
    (comp (ref "C19F")
      (value "22u")
      (footprint "eagle-import:C1206")
      (fields
        (field (name "MANUFACTURER_PART_NUMBER") "EMK316BB7226ML-T")
        (field (name "MOUSER_PART_NUMBER") "963-EMK316BB7226ML-T")
      )
      (libsource (lib "eagle-import") (part "EMK316BB7226ML-T"))
    )
    (comp (ref "C20A")
      (value "10u")
      (footprint "eagle-import:CAPC2012X135N")
      (fields
        (field (name "MANUFACTURER_PART_NUMBER") "EMK212BB7106KG-T")
        (field (name "MOUSER_PART_NUMBER") "963-EMK212BB7106KG-T")
      )
      (libsource (lib "eagle-import") (part "EMK212BB7106KG-T"))
    )
    (comp (ref "C20B")
      (value "10u")
      (footprint "eagle-import:CAPC2012X135N")
      (fields
        (field (name "MANUFACTURER_PART_NUMBER") "EMK212BB7106KG-T")
        (field (name "MOUSER_PART_NUMBER") "963-EMK212BB7106KG-T")
      )
      (libsource (lib "eagle-import") (part "EMK212BB7106KG-T"))
    )
    (comp (ref "C20C")
      (value "10u")
      (footprint "eagle-import:CAPC2012X135N")
      (fields
        (field (name "MANUFACTURER_PART_NUMBER") "EMK212BB7106KG-T")
        (field (name "MOUSER_PART_NUMBER") "963-EMK212BB7106KG-T")
      )
      (libsource (lib "eagle-import") (part "EMK212BB7106KG-T"))
    )
    (comp (ref "C20D")
      (value "10u")
      (footprint "eagle-import:CAPC2012X135N")
      (fields
        (field (name "MANUFACTURER_PART_NUMBER") "EMK212BB7106KG-T")
        (field (name "MOUSER_PART_NUMBER") "963-EMK212BB7106KG-T")
      )
      (libsource (lib "eagle-import") (part "EMK212BB7106KG-T"))
    )
    (comp (ref "C20E")
      (value "10u")
      (footprint "eagle-import:CAPC2012X135N")
      (fields
        (field (name "MANUFACTURER_PART_NUMBER") "EMK212BB7106KG-T")
        (field (name "MOUSER_PART_NUMBER") "963-EMK212BB7106KG-T")
      )
      (libsource (lib "eagle-import") (part "EMK212BB7106KG-T"))
    )
    (comp (ref "C20F")
      (value "10u")
      (footprint "eagle-import:CAPC2012X135N")
      (fields
        (field (name "MANUFACTURER_PART_NUMBER") "EMK212BB7106KG-T")
        (field (name "MOUSER_PART_NUMBER") "963-EMK212BB7106KG-T")
      )
      (libsource (lib "eagle-import") (part "EMK212BB7106KG-T"))
    )
    (comp (ref "C21A")
      (value "0.1u")
      (footprint "eagle-import:CAPC2012X135N")
      (fields
        (field (name "MANUFACTURER_PART_NUMBER") "EMF212B7104KGHT")
        (field (name "MOUSER_PART_NUMBER") "963-EMF212B7104KGHT")
      )
      (libsource (lib "eagle-import") (part "EMF212B7104KGHT"))
    )
    (comp (ref "C21B")
      (value "0.1u")
      (footprint "eagle-import:CAPC2012X135N")
      (fields
        (field (name "MANUFACTURER_PART_NUMBER") "EMF212B7104KGHT")
        (field (name "MOUSER_PART_NUMBER") "963-EMF212B7104KGHT")
      )
      (libsource (lib "eagle-import") (part "EMF212B7104KGHT"))
    )
    (comp (ref "C21C")
      (value "0.1u")
      (footprint "eagle-import:CAPC2012X135N")
      (fields
        (field (name "MANUFACTURER_PART_NUMBER") "EMF212B7104KGHT")
        (field (name "MOUSER_PART_NUMBER") "963-EMF212B7104KGHT")
      )
      (libsource (lib "eagle-import") (part "EMF212B7104KGHT"))
    )
    (comp (ref "C21D")
      (value "0.1u")
      (footprint "eagle-import:CAPC2012X135N")
      (fields
        (field (name "MANUFACTURER_PART_NUMBER") "EMF212B7104KGHT")
        (field (name "MOUSER_PART_NUMBER") "963-EMF212B7104KGHT")
      )
      (libsource (lib "eagle-import") (part "EMF212B7104KGHT"))
    )
    (comp (ref "C21E")
      (value "0.1u")
      (footprint "eagle-import:CAPC2012X135N")
      (fields
        (field (name "MANUFACTURER_PART_NUMBER") "EMF212B7104KGHT")
        (field (name "MOUSER_PART_NUMBER") "963-EMF212B7104KGHT")
      )
      (libsource (lib "eagle-import") (part "EMF212B7104KGHT"))
    )
    (comp (ref "C21F")
      (value "0.1u")
      (footprint "eagle-import:CAPC2012X135N")
      (fields
        (field (name "MANUFACTURER_PART_NUMBER") "EMF212B7104KGHT")
        (field (name "MOUSER_PART_NUMBER") "963-EMF212B7104KGHT")
      )
      (libsource (lib "eagle-import") (part "EMF212B7104KGHT"))
    )
    (comp (ref "C21O")
      (value "30uF/400V")
      (footprint "eagle-import:DCP4G053006ID2KSSD")
      (fields
        (field (name "MANUFACTURER_PART_NUMBER") "DCP4G053006ID2KSSD")
        (field (name "MOUSER_PART_NUMBER") "505-DCP4G0536ID2KSSD")
      )
      (libsource (lib "eagle-import") (part "DCP4G053006ID2KSSD"))
    )
    (comp (ref "C22A")
      (value "0.1u, Ceramic Capacitor X7R")
      (footprint "eagle-import:CAPC2012X135N")
      (fields
        (field (name "MANUFACTURER_PART_NUMBER") "EMF212B7104KGHT")
        (field (name "MOUSER_PART_NUMBER") "963-EMF212B7104KGHT")
      )
      (libsource (lib "eagle-import") (part "EMF212B7104KGHT"))
    )
    (comp (ref "C23A")
      (value "0.1u, Ceramic Capacitor X7R")
      (footprint "eagle-import:CAPC2012X135N")
      (fields
        (field (name "MANUFACTURER_PART_NUMBER") "EMF212B7104KGHT")
        (field (name "MOUSER_PART_NUMBER") "963-EMF212B7104KGHT")
      )
      (libsource (lib "eagle-import") (part "EMF212B7104KGHT"))
    )
    (comp (ref "C23O")
      (value "1uF/400V")
      (footprint "eagle-import:MKP4G041005I00JSSD")
      (fields
        (field (name "MANUFACTURER_PART_NUMBER") "MKP4G041005I00JSSD")
        (field (name "MOUSER_PART_NUMBER") "505-MKP4G041005I00JS")
      )
      (libsource (lib "eagle-import") (part "MKP4G041005I00JSSD"))
    )
    (comp (ref "C24A")
      (value "0.1u, Ceramic Capacitor X7R")
      (footprint "eagle-import:CAPC2012X135N")
      (fields
        (field (name "MANUFACTURER_PART_NUMBER") "EMF212B7104KGHT")
        (field (name "MOUSER_PART_NUMBER") "963-EMF212B7104KGHT")
      )
      (libsource (lib "eagle-import") (part "EMF212B7104KGHT"))
    )
    (comp (ref "C24O")
      (value "100uF")
      (footprint "eagle-import:CAPPRD350W60D825H1300")
      (fields
        (field (name "ARROW_PART_NUMBER") "UFW1H101MPD1TD")
        (field (name "MOUSER_PART_NUMBER") "647-UFW1H101MPD1TD")
      )
      (libsource (lib "eagle-import") (part "UFW1H101MPD1TD"))
    )
    (comp (ref "C25O")
      (value "100uF")
      (footprint "eagle-import:CAPPRD350W60D825H1300")
      (fields
        (field (name "ARROW_PART_NUMBER") "UFW1H101MPD1TD")
        (field (name "MOUSER_PART_NUMBER") "647-UFW1H101MPD1TD")
      )
      (libsource (lib "eagle-import") (part "UFW1H101MPD1TD"))
    )
    (comp (ref "C26A")
      (value "4.7u, Ceramic Capacitor X7R")
      (footprint "eagle-import:CAPC2013X140N")
      (fields
        (field (name "MANUFACTURER_PART_NUMBER") "EMK212ABJ475KG-T")
        (field (name "MOUSER_PART_NUMBER") "963-EMK212ABJ475KG-T")
      )
      (libsource (lib "eagle-import") (part "EMK212ABJ475KG-T"))
    )
    (comp (ref "C26B")
      (value "4.7u, Ceramic Capacitor X7R")
      (footprint "eagle-import:CAPC2013X140N")
      (fields
        (field (name "MANUFACTURER_PART_NUMBER") "EMK212ABJ475KG-T")
        (field (name "MOUSER_PART_NUMBER") "963-EMK212ABJ475KG-T")
      )
      (libsource (lib "eagle-import") (part "EMK212ABJ475KG-T"))
    )
    (comp (ref "C26O")
      (value "100uF")
      (footprint "eagle-import:CAPPRD350W60D825H1300")
      (fields
        (field (name "ARROW_PART_NUMBER") "UFW1H101MPD1TD")
        (field (name "MOUSER_PART_NUMBER") "647-UFW1H101MPD1TD")
      )
      (libsource (lib "eagle-import") (part "UFW1H101MPD1TD"))
    )
    (comp (ref "C27A")
      (value "4.7u, Ceramic Capacitor X7R")
      (footprint "eagle-import:CAPC2013X140N")
      (fields
        (field (name "MANUFACTURER_PART_NUMBER") "EMK212ABJ475KG-T")
        (field (name "MOUSER_PART_NUMBER") "963-EMK212ABJ475KG-T")
      )
      (libsource (lib "eagle-import") (part "EMK212ABJ475KG-T"))
    )
    (comp (ref "C27B")
      (value "4.7u, Ceramic Capacitor X7R")
      (footprint "eagle-import:CAPC2013X140N")
      (fields
        (field (name "MANUFACTURER_PART_NUMBER") "EMK212ABJ475KG-T")
        (field (name "MOUSER_PART_NUMBER") "963-EMK212ABJ475KG-T")
      )
      (libsource (lib "eagle-import") (part "EMK212ABJ475KG-T"))
    )
    (comp (ref "C28A")
      (value "0.1u, Ceramic Capacitor X7R")
      (footprint "eagle-import:CAPC2012X135N")
      (fields
        (field (name "MANUFACTURER_PART_NUMBER") "EMF212B7104KGHT")
        (field (name "MOUSER_PART_NUMBER") "963-EMF212B7104KGHT")
      )
      (libsource (lib "eagle-import") (part "EMF212B7104KGHT"))
    )
    (comp (ref "C28B")
      (value "0.1u, Ceramic Capacitor X7R")
      (footprint "eagle-import:CAPC2012X135N")
      (fields
        (field (name "MANUFACTURER_PART_NUMBER") "EMF212B7104KGHT")
        (field (name "MOUSER_PART_NUMBER") "963-EMF212B7104KGHT")
      )
      (libsource (lib "eagle-import") (part "EMF212B7104KGHT"))
    )
    (comp (ref "D1")
      (value "1N4007FFG")
      (footprint "eagle-import:DIOAD1405W86L465D235")
      (fields (field (name "MOUSER_PART_NUMBER") "863-1N4007FFG"))
      (libsource (lib "eagle-import") (part "1N4007FFG"))
    )
    (comp (ref "D2")
      (value "1N4007FFG")
      (footprint "eagle-import:DIOAD1405W86L465D235")
      (fields (field (name "MOUSER_PART_NUMBER") "863-1N4007FFG"))
      (libsource (lib "eagle-import") (part "1N4007FFG"))
    )
    (comp (ref "D3")
      (value "1N4007FFG")
      (footprint "eagle-import:DIOAD1405W86L465D235")
      (fields (field (name "MOUSER_PART_NUMBER") "863-1N4007FFG"))
      (libsource (lib "eagle-import") (part "1N4007FFG"))
    )
    (comp (ref "D4")
      (value "1N4007FFG")
      (footprint "eagle-import:DIOAD1405W86L465D235")
      (fields (field (name "MOUSER_PART_NUMBER") "863-1N4007FFG"))
      (libsource (lib "eagle-import") (part "1N4007FFG"))
    )
    (comp (ref "D5")
      (value "1N4007FFG")
      (footprint "eagle-import:DIOAD1405W86L465D235")
      (fields (field (name "MOUSER_PART_NUMBER") "863-1N4007FFG"))
      (libsource (lib "eagle-import") (part "1N4007FFG"))
    )
    (comp (ref "D6")
      (value "1N4007FFG")
      (footprint "eagle-import:DIOAD1405W86L465D235")
      (fields (field (name "MOUSER_PART_NUMBER") "863-1N4007FFG"))
      (libsource (lib "eagle-import") (part "1N4007FFG"))
    )
    (comp (ref "D7")
      (value "1N4007FFG")
      (footprint "eagle-import:DIOAD1405W86L465D235")
      (fields (field (name "MOUSER_PART_NUMBER") "863-1N4007FFG"))
      (libsource (lib "eagle-import") (part "1N4007FFG"))
    )
    (comp (ref "D8")
      (value "1N4007FFG")
      (footprint "eagle-import:DIOAD1405W86L465D235")
      (fields (field (name "MOUSER_PART_NUMBER") "863-1N4007FFG"))
      (libsource (lib "eagle-import") (part "1N4007FFG"))
    )
    (comp (ref "D9")
      (value "1A/40V/500mV")
      (footprint "eagle-import:SMA-DIODE")
      (libsource (lib "eagle-import") (part "DIODE-SCHOTTKY-SS14"))
    )
    (comp (ref "DIF1")
      (value "SJ2W")
      (footprint "eagle-import:SJ_2")
      (libsource (lib "eagle-import") (part "SJ2W"))
    )
    (comp (ref "DIF3")
      (value "SJ2W")
      (footprint "eagle-import:SJ_2")
      (libsource (lib "eagle-import") (part "SJ2W"))
    )
    (comp (ref "IC1")
      (value "LT3042")
      (footprint "eagle-import:SOP50P490X110-11N")
      (fields
        (field (name "MANUFACTURER_PART_NUMBER") "LT3042EMSE#PBF")
        (field (name "MOUSER_PART_NUMBER") "584-LT3042EMSE#PBF")
      )
      (libsource (lib "eagle-import") (part "LT3042"))
    )
    (comp (ref "IC2")
      (value "AK4493")
      (footprint "eagle-import:LQFP48_")
      (libsource (lib "eagle-import") (part "AK4493"))
    )
    (comp (ref "IC3")
      (value "AK4493")
      (footprint "eagle-import:LQFP48_")
      (libsource (lib "eagle-import") (part "AK4493"))
    )
    (comp (ref "IC4")
      (value "LT3042")
      (footprint "eagle-import:SOP50P490X110-11N")
      (fields
        (field (name "MANUFACTURER_PART_NUMBER") "LT3042EMSE#PBF")
        (field (name "MOUSER_PART_NUMBER") "584-LT3042EMSE#PBF")
      )
      (libsource (lib "eagle-import") (part "LT3042"))
    )
    (comp (ref "IC4A")
      (value "SN74ABT273DBR")
      (footprint "eagle-import:SOP65P780X200-20N")
      (fields (field (name "MOUSER_PART_NUMBER") "595-SN74ABT273DBR"))
      (libsource (lib "eagle-import") (part "SN74ABT273DBR"))
    )
    (comp (ref "IC5")
      (value "LT3042")
      (footprint "eagle-import:SOP50P490X110-11N")
      (fields
        (field (name "MANUFACTURER_PART_NUMBER") "LT3042EMSE#PBF")
        (field (name "MOUSER_PART_NUMBER") "584-LT3042EMSE#PBF")
      )
      (libsource (lib "eagle-import") (part "LT3042"))
    )
    (comp (ref "IC6")
      (value "LT3042")
      (footprint "eagle-import:SOP50P490X110-11N")
      (fields
        (field (name "MANUFACTURER_PART_NUMBER") "LT3042EMSE#PBF")
        (field (name "MOUSER_PART_NUMBER") "584-LT3042EMSE#PBF")
      )
      (libsource (lib "eagle-import") (part "LT3042"))
    )
    (comp (ref "IC7")
      (value "LT3042")
      (footprint "eagle-import:SOP50P490X110-11N")
      (fields
        (field (name "MANUFACTURER_PART_NUMBER") "LT3042EMSE#PBF")
        (field (name "MOUSER_PART_NUMBER") "584-LT3042EMSE#PBF")
      )
      (libsource (lib "eagle-import") (part "LT3042"))
    )
    (comp (ref "IC8")
      (value "LT3042")
      (footprint "eagle-import:SOP50P490X110-11N")
      (fields
        (field (name "MANUFACTURER_PART_NUMBER") "LT3042EMSE#PBF")
        (field (name "MOUSER_PART_NUMBER") "584-LT3042EMSE#PBF")
      )
      (libsource (lib "eagle-import") (part "LT3042"))
    )
    (comp (ref "IN")
      (value "1935213")
      (footprint "eagle-import:1935213")
      (fields (field (name "MOUSER_PART_NUMBER") "651-1935213"))
      (libsource (lib "eagle-import") (part "1935213"))
    )
    (comp (ref "J5")
      (value "CONN_07")
      (footprint "eagle-import:1X07")
      (libsource (lib "eagle-import") (part "CONN_07"))
    )
    (comp (ref "J6")
      (value "CONN_07")
      (footprint "eagle-import:1X07")
      (libsource (lib "eagle-import") (part "CONN_07"))
    )
    (comp (ref "J7")
      (value "CONN_07")
      (footprint "eagle-import:1X07")
      (libsource (lib "eagle-import") (part "CONN_07"))
    )
    (comp (ref "J8")
      (value "CONN_07")
      (footprint "eagle-import:1X07")
      (libsource (lib "eagle-import") (part "CONN_07"))
    )
    (comp (ref "J9")
      (value "CONN_07")
      (footprint "eagle-import:1X07")
      (libsource (lib "eagle-import") (part "CONN_07"))
    )
    (comp (ref "J10")
      (value "CONN_07")
      (footprint "eagle-import:1X07")
      (libsource (lib "eagle-import") (part "CONN_07"))
    )
    (comp (ref "J11")
      (value "CONN_07")
      (footprint "eagle-import:1X07")
      (libsource (lib "eagle-import") (part "CONN_07"))
    )
    (comp (ref "J12")
      (value "CONN_07")
      (footprint "eagle-import:1X07")
      (libsource (lib "eagle-import") (part "CONN_07"))
    )
    (comp (ref "J15")
      (value "XR2A-0811-N")
      (footprint "eagle-import:DIPS762W51P254L1016H390Q8N")
      (fields (field (name "MOUSER_PART_NUMBER") "653-XR2A-0811-N"))
      (libsource (lib "eagle-import") (part "XR2A-0811-N"))
    )
    (comp (ref "J16")
      (value "XR2A-0811-N")
      (footprint "eagle-import:DIPS762W51P254L1016H390Q8N")
      (fields (field (name "MOUSER_PART_NUMBER") "653-XR2A-0811-N"))
      (libsource (lib "eagle-import") (part "XR2A-0811-N"))
    )
    (comp (ref "J17")
      (value "XR2A-0811-N")
      (footprint "eagle-import:DIPS762W51P254L1016H390Q8N")
      (fields (field (name "MOUSER_PART_NUMBER") "653-XR2A-0811-N"))
      (libsource (lib "eagle-import") (part "XR2A-0811-N"))
    )
    (comp (ref "J18")
      (value "XR2A-0811-N")
      (footprint "eagle-import:DIPS762W51P254L1016H390Q8N")
      (fields (field (name "MOUSER_PART_NUMBER") "653-XR2A-0811-N"))
      (libsource (lib "eagle-import") (part "XR2A-0811-N"))
    )
    (comp (ref "J19")
      (value "XR2A-0811-N")
      (footprint "eagle-import:DIPS762W51P254L1016H390Q8N")
      (fields (field (name "MOUSER_PART_NUMBER") "653-XR2A-0811-N"))
      (libsource (lib "eagle-import") (part "XR2A-0811-N"))
    )
    (comp (ref "J20")
      (value "XR2A-0811-N")
      (footprint "eagle-import:DIPS762W51P254L1016H390Q8N")
      (fields (field (name "MOUSER_PART_NUMBER") "653-XR2A-0811-N"))
      (libsource (lib "eagle-import") (part "XR2A-0811-N"))
    )
    (comp (ref "J21")
      (value "CONN_10\"")
      (footprint "eagle-import:1X10")
      (libsource (lib "eagle-import") (part "CONN_10{dblquote}"))
    )
    (comp (ref "J22")
      (value "CONN_10\"")
      (footprint "eagle-import:1X10")
      (libsource (lib "eagle-import") (part "CONN_10{dblquote}"))
    )
    (comp (ref "J26")
      (value "SJ-63033A")
      (footprint "eagle-import:SJ63033A")
      (libsource (lib "eagle-import") (part "SJ-63033A"))
    )
    (comp (ref "J27")
      (value "1935161")
      (footprint "eagle-import:1935161")
      (fields (field (name "MOUSER_PART_NUMBER") "651-1935161"))
      (libsource (lib "eagle-import") (part "1935161"))
    )
    (comp (ref "LDO7")
      (value "LP5907-1.8V")
      (footprint "eagle-import:SOT95P280X145-5N")
      (fields
        (field (name "ARROW_PART_NUMBER") "LP5907MFX-1.8/NOPB")
        (field (name "MOUSER_PART_NUMBER") "595-LP5907MFX-1.8NPB")
      )
      (libsource (lib "eagle-import") (part "LP5907-1.8V"))
    )
    (comp (ref "LDO8")
      (value "LP5907-1.8V")
      (footprint "eagle-import:SOT95P280X145-5N")
      (fields
        (field (name "ARROW_PART_NUMBER") "LP5907MFX-1.8/NOPB")
        (field (name "MOUSER_PART_NUMBER") "595-LP5907MFX-1.8NPB")
      )
      (libsource (lib "eagle-import") (part "LP5907-1.8V"))
    )
    (comp (ref "R1")
      (value "5k")
      (footprint "eagle-import:R0603")
      (libsource (lib "eagle-import") (part "R-US_R0603"))
    )
    (comp (ref "R1A")
      (value "RT0603DRE075R1L")
      (footprint "eagle-import:RESC1608X55N")
      (libsource (lib "eagle-import") (part "RT0603DRE075R1L"))
    )
    (comp (ref "R1B")
      (value "RT0603DRE075R1L")
      (footprint "eagle-import:RESC1608X55N")
      (libsource (lib "eagle-import") (part "RT0603DRE075R1L"))
    )
    (comp (ref "R1O")
      (value "47kOhm")
      (footprint "eagle-import:RESAD1540W55L620D230")
      (fields
        (field (name "MANUFACTURER_PART_NUMBER") "LR1F47K")
        (field (name "MOUSER_PART_NUMBER") "279-LR1F47K")
      )
      (libsource (lib "eagle-import") (part "LR1F47K"))
    )
    (comp (ref "R2A")
      (value "RT0603DRE075R1L")
      (footprint "eagle-import:RESC1608X55N")
      (libsource (lib "eagle-import") (part "RT0603DRE075R1L"))
    )
    (comp (ref "R2B")
      (value "RT0603DRE075R1L")
      (footprint "eagle-import:RESC1608X55N")
      (libsource (lib "eagle-import") (part "RT0603DRE075R1L"))
    )
    (comp (ref "R2O")
      (value "47kOhm")
      (footprint "eagle-import:RESAD1540W55L620D230")
      (fields
        (field (name "MANUFACTURER_PART_NUMBER") "LR1F47K")
        (field (name "MOUSER_PART_NUMBER") "279-LR1F47K")
      )
      (libsource (lib "eagle-import") (part "LR1F47K"))
    )
    (comp (ref "R2P")
      (value "220")
      (footprint "eagle-import:0411_15")
      (libsource (lib "eagle-import") (part "R-US_0411/15"))
    )
    (comp (ref "R3A")
      (value "RT0603DRE075R1L")
      (footprint "eagle-import:RESC1608X55N")
      (libsource (lib "eagle-import") (part "RT0603DRE075R1L"))
    )
    (comp (ref "R3B")
      (value "RT0603DRE075R1L")
      (footprint "eagle-import:RESC1608X55N")
      (libsource (lib "eagle-import") (part "RT0603DRE075R1L"))
    )
    (comp (ref "R3O")
      (value "1M*")
      (footprint "eagle-import:RESAD1540W60L620D230")
      (fields
        (field (name "MANUFACTURER_PART_NUMBER") "LR1F1M0")
        (field (name "MOUSER_PART_NUMBER") "279-LR1F1M0")
      )
      (libsource (lib "eagle-import") (part "LR1F1M0"))
    )
    (comp (ref "R3P")
      (value "220")
      (footprint "eagle-import:0411_15")
      (libsource (lib "eagle-import") (part "R-US_0411/15"))
    )
    (comp (ref "R4A")
      (value "RT0603DRE075R1L")
      (footprint "eagle-import:RESC1608X55N")
      (libsource (lib "eagle-import") (part "RT0603DRE075R1L"))
    )
    (comp (ref "R4B")
      (value "RT0603DRE075R1L")
      (footprint "eagle-import:RESC1608X55N")
      (libsource (lib "eagle-import") (part "RT0603DRE075R1L"))
    )
    (comp (ref "R4O")
      (value "47kOhm")
      (footprint "eagle-import:RESAD1540W55L620D230")
      (fields
        (field (name "MANUFACTURER_PART_NUMBER") "LR1F47K")
        (field (name "MOUSER_PART_NUMBER") "279-LR1F47K")
      )
      (libsource (lib "eagle-import") (part "LR1F47K"))
    )
    (comp (ref "R4P")
      (value "300k")
      (footprint "eagle-import:0411_15")
      (libsource (lib "eagle-import") (part "R-US_0411/15"))
    )
    (comp (ref "R5A")
      (value "10K, Resistor 1%")
      (footprint "eagle-import:RESC2012X50N")
      (fields
        (field (name "MANUFACTURER_PART_NUMBER") "RCS080510K0FKEA")
        (field (name "MOUSER_PART_NUMBER") "71-RCS080510K0FKEA")
      )
      (libsource (lib "eagle-import") (part "RCS080510K0FKEA"))
    )
    (comp (ref "R5O")
      (value "150*")
      (footprint "eagle-import:RESAD1540W55L620D230")
      (fields (field (name "MANUFACTURER_PART_NUMBER") "LR1F150R"))
      (libsource (lib "eagle-import") (part "LR1F150R"))
    )
    (comp (ref "R5P")
      (value "100k")
      (footprint "eagle-import:0411_15")
      (libsource (lib "eagle-import") (part "R-US_0411/15"))
    )
    (comp (ref "R6A")
      (value "1k")
      (footprint "eagle-import:RESC2012X60N")
      (fields
        (field (name "MANUFACTURER_PART_NUMBER") "CHP0805-FX-1001ELF")
        (field (name "MOUSER_PART_NUMBER") "652-CHP0805FX1001ELF")
      )
      (libsource (lib "eagle-import") (part "CHP0805-FX-1001ELF"))
    )
    (comp (ref "R6B")
      (value "1k")
      (footprint "eagle-import:RESC2012X60N")
      (fields
        (field (name "MANUFACTURER_PART_NUMBER") "CHP0805-FX-1001ELF")
        (field (name "MOUSER_PART_NUMBER") "652-CHP0805FX1001ELF")
      )
      (libsource (lib "eagle-import") (part "CHP0805-FX-1001ELF"))
    )
    (comp (ref "R6C")
      (value "1k")
      (footprint "eagle-import:RESC2012X60N")
      (fields
        (field (name "MANUFACTURER_PART_NUMBER") "CHP0805-FX-1001ELF")
        (field (name "MOUSER_PART_NUMBER") "652-CHP0805FX1001ELF")
      )
      (libsource (lib "eagle-import") (part "CHP0805-FX-1001ELF"))
    )
    (comp (ref "R6D")
      (value "1k")
      (footprint "eagle-import:RESC2012X60N")
      (fields
        (field (name "MANUFACTURER_PART_NUMBER") "CHP0805-FX-1001ELF")
        (field (name "MOUSER_PART_NUMBER") "652-CHP0805FX1001ELF")
      )
      (libsource (lib "eagle-import") (part "CHP0805-FX-1001ELF"))
    )
    (comp (ref "R6E")
      (value "1k")
      (footprint "eagle-import:RESC2012X60N")
      (fields
        (field (name "MANUFACTURER_PART_NUMBER") "CHP0805-FX-1001ELF")
        (field (name "MOUSER_PART_NUMBER") "652-CHP0805FX1001ELF")
      )
      (libsource (lib "eagle-import") (part "CHP0805-FX-1001ELF"))
    )
    (comp (ref "R6F")
      (value "1k")
      (footprint "eagle-import:RESC2012X60N")
      (fields
        (field (name "MANUFACTURER_PART_NUMBER") "CHP0805-FX-1001ELF")
        (field (name "MOUSER_PART_NUMBER") "652-CHP0805FX1001ELF")
      )
      (libsource (lib "eagle-import") (part "CHP0805-FX-1001ELF"))
    )
    (comp (ref "R6O")
      (value "47kOhm")
      (footprint "eagle-import:RESAD1540W55L620D230")
      (fields
        (field (name "MANUFACTURER_PART_NUMBER") "LR1F47K")
        (field (name "MOUSER_PART_NUMBER") "279-LR1F47K")
      )
      (libsource (lib "eagle-import") (part "LR1F47K"))
    )
    (comp (ref "R6P")
      (value "330")
      (footprint "eagle-import:0411_15")
      (libsource (lib "eagle-import") (part "R-US_0411/15"))
    )
    (comp (ref "R7A")
      (value "33k")
      (footprint "eagle-import:R0805")
      (fields
        (field (name "MANUFACTURER_PART_NUMBER") "CPF0805B51KE1")
        (field (name "MOUSER_PART_NUMBER") "279-CPF0805B51KE1")
      )
      (libsource (lib "eagle-import") (part "CPF0805B51KE1"))
    )
    (comp (ref "R7B")
      (value "33k")
      (footprint "eagle-import:R0805")
      (fields
        (field (name "MANUFACTURER_PART_NUMBER") "CPF0805B51KE1")
        (field (name "MOUSER_PART_NUMBER") "279-CPF0805B51KE1")
      )
      (libsource (lib "eagle-import") (part "CPF0805B51KE1"))
    )
    (comp (ref "R7C")
      (value "33k")
      (footprint "eagle-import:R0805")
      (fields
        (field (name "MANUFACTURER_PART_NUMBER") "CPF0805B51KE1")
        (field (name "MOUSER_PART_NUMBER") "279-CPF0805B51KE1")
      )
      (libsource (lib "eagle-import") (part "CPF0805B51KE1"))
    )
    (comp (ref "R7D")
      (value "33k")
      (footprint "eagle-import:R0805")
      (fields
        (field (name "MANUFACTURER_PART_NUMBER") "CPF0805B51KE1")
        (field (name "MOUSER_PART_NUMBER") "279-CPF0805B51KE1")
      )
      (libsource (lib "eagle-import") (part "CPF0805B51KE1"))
    )
    (comp (ref "R7E")
      (value "33k")
      (footprint "eagle-import:R0805")
      (fields
        (field (name "MANUFACTURER_PART_NUMBER") "CPF0805B51KE1")
        (field (name "MOUSER_PART_NUMBER") "279-CPF0805B51KE1")
      )
      (libsource (lib "eagle-import") (part "CPF0805B51KE1"))
    )
    (comp (ref "R7F")
      (value "33k")
      (footprint "eagle-import:R0805")
      (fields
        (field (name "MANUFACTURER_PART_NUMBER") "CPF0805B51KE1")
        (field (name "MOUSER_PART_NUMBER") "279-CPF0805B51KE1")
      )
      (libsource (lib "eagle-import") (part "CPF0805B51KE1"))
    )
    (comp (ref "R7O")
      (value "1M*")
      (footprint "eagle-import:RESAD1540W60L620D230")
      (fields
        (field (name "MANUFACTURER_PART_NUMBER") "LR1F1M0")
        (field (name "MOUSER_PART_NUMBER") "279-LR1F1M0")
      )
      (libsource (lib "eagle-import") (part "LR1F1M0"))
    )
    (comp (ref "R8A")
      (value "200k")
      (footprint "eagle-import:R0805")
      (fields
        (field (name "MANUFACTURER_PART_NUMBER") "RR1220P-204-D")
        (field (name "MOUSER_PART_NUMBER") "754-RR1220P-204D")
      )
      (libsource (lib "eagle-import") (part "RR1220P-204-D"))
    )
    (comp (ref "R8B")
      (value "200k")
      (footprint "eagle-import:R0805")
      (fields
        (field (name "MANUFACTURER_PART_NUMBER") "RR1220P-204-D")
        (field (name "MOUSER_PART_NUMBER") "754-RR1220P-204D")
      )
      (libsource (lib "eagle-import") (part "RR1220P-204-D"))
    )
    (comp (ref "R8C")
      (value "200k")
      (footprint "eagle-import:R0805")
      (fields
        (field (name "MANUFACTURER_PART_NUMBER") "RR1220P-204-D")
        (field (name "MOUSER_PART_NUMBER") "754-RR1220P-204D")
      )
      (libsource (lib "eagle-import") (part "RR1220P-204-D"))
    )
    (comp (ref "R8D")
      (value "200k")
      (footprint "eagle-import:R0805")
      (fields
        (field (name "MANUFACTURER_PART_NUMBER") "RR1220P-204-D")
        (field (name "MOUSER_PART_NUMBER") "754-RR1220P-204D")
      )
      (libsource (lib "eagle-import") (part "RR1220P-204-D"))
    )
    (comp (ref "R8E")
      (value "200k")
      (footprint "eagle-import:R0805")
      (fields
        (field (name "MANUFACTURER_PART_NUMBER") "RR1220P-204-D")
        (field (name "MOUSER_PART_NUMBER") "754-RR1220P-204D")
      )
      (libsource (lib "eagle-import") (part "RR1220P-204-D"))
    )
    (comp (ref "R8F")
      (value "200k")
      (footprint "eagle-import:R0805")
      (fields
        (field (name "MANUFACTURER_PART_NUMBER") "RR1220P-204-D")
        (field (name "MOUSER_PART_NUMBER") "754-RR1220P-204D")
      )
      (libsource (lib "eagle-import") (part "RR1220P-204-D"))
    )
    (comp (ref "R8O")
      (value "150*")
      (footprint "eagle-import:RESAD1540W55L620D230")
      (fields (field (name "MANUFACTURER_PART_NUMBER") "LR1F150R"))
      (libsource (lib "eagle-import") (part "LR1F150R"))
    )
    (comp (ref "R9O")
      (value "150*")
      (footprint "eagle-import:RESAD1540W55L620D230")
      (fields (field (name "MANUFACTURER_PART_NUMBER") "LR1F150R"))
      (libsource (lib "eagle-import") (part "LR1F150R"))
    )
    (comp (ref "R10")
      (value "2.2k, 1%")
      (footprint "eagle-import:RCS0805_E3")
      (fields
        (field (name "MANUFACTURER_PART_NUMBER") "RCS08052K20FKEA")
        (field (name "MOUSER_PART_NUMBER") "71-RCS08052K20FKEA")
      )
      (libsource (lib "eagle-import") (part "RCS08052K20FKEA"))
    )
    (comp (ref "R10O")
      (value "150*")
      (footprint "eagle-import:RESAD1540W55L620D230")
      (fields (field (name "MANUFACTURER_PART_NUMBER") "LR1F150R"))
      (libsource (lib "eagle-import") (part "LR1F150R"))
    )
    (comp (ref "R11O")
      (value "10k")
      (footprint "eagle-import:RESAD1540W55L620D230")
      (fields
        (field (name "MANUFACTURER_PART_NUMBER") "LR1F10K")
        (field (name "MOUSER_PART_NUMBER") "279-LR1F10K")
      )
      (libsource (lib "eagle-import") (part "LR1F10K"))
    )
    (comp (ref "R12O")
      (value "182")
      (footprint "eagle-import:RESAD1590W60L630D240")
      (fields (field (name "MANUFACTURER_PART_NUMBER") "MF0207FTE52-182R"))
      (libsource (lib "eagle-import") (part "MF0207FTE52-182R"))
    )
    (comp (ref "R13O")
      (value "47kOhm")
      (footprint "eagle-import:RESAD1540W55L620D230")
      (fields
        (field (name "MANUFACTURER_PART_NUMBER") "LR1F47K")
        (field (name "MOUSER_PART_NUMBER") "279-LR1F47K")
      )
      (libsource (lib "eagle-import") (part "LR1F47K"))
    )
    (comp (ref "R14O")
      (value "182")
      (footprint "eagle-import:RESAD1590W60L630D240")
      (fields (field (name "MANUFACTURER_PART_NUMBER") "MF0207FTE52-182R"))
      (libsource (lib "eagle-import") (part "MF0207FTE52-182R"))
    )
    (comp (ref "R15O")
      (value "47kOhm")
      (footprint "eagle-import:RESAD1540W55L620D230")
      (fields
        (field (name "MANUFACTURER_PART_NUMBER") "LR1F47K")
        (field (name "MOUSER_PART_NUMBER") "279-LR1F47K")
      )
      (libsource (lib "eagle-import") (part "LR1F47K"))
    )
    (comp (ref "R16O")
      (value "182")
      (footprint "eagle-import:RESAD1590W60L630D240")
      (fields (field (name "MANUFACTURER_PART_NUMBER") "MF0207FTE52-182R"))
      (libsource (lib "eagle-import") (part "MF0207FTE52-182R"))
    )
    (comp (ref "R17O")
      (value "47kOhm")
      (footprint "eagle-import:RESAD1540W55L620D230")
      (fields
        (field (name "MANUFACTURER_PART_NUMBER") "LR1F47K")
        (field (name "MOUSER_PART_NUMBER") "279-LR1F47K")
      )
      (libsource (lib "eagle-import") (part "LR1F47K"))
    )
    (comp (ref "R18O")
      (value "182")
      (footprint "eagle-import:RESAD1590W60L630D240")
      (fields (field (name "MANUFACTURER_PART_NUMBER") "MF0207FTE52-182R"))
      (libsource (lib "eagle-import") (part "MF0207FTE52-182R"))
    )
    (comp (ref "R19O")
      (value "10k")
      (footprint "eagle-import:RESAD1540W55L620D230")
      (fields
        (field (name "MANUFACTURER_PART_NUMBER") "LR1F10K")
        (field (name "MOUSER_PART_NUMBER") "279-LR1F10K")
      )
      (libsource (lib "eagle-import") (part "LR1F10K"))
    )
    (comp (ref "R20")
      (value "2.2k, 1%")
      (footprint "eagle-import:RCS0805_E3")
      (fields
        (field (name "MANUFACTURER_PART_NUMBER") "RCS08052K20FKEA")
        (field (name "MOUSER_PART_NUMBER") "71-RCS08052K20FKEA")
      )
      (libsource (lib "eagle-import") (part "RCS08052K20FKEA"))
    )
    (comp (ref "R20O")
      (value "10k")
      (footprint "eagle-import:RESAD1540W55L620D230")
      (fields
        (field (name "MANUFACTURER_PART_NUMBER") "LR1F10K")
        (field (name "MOUSER_PART_NUMBER") "279-LR1F10K")
      )
      (libsource (lib "eagle-import") (part "LR1F10K"))
    )
    (comp (ref "R21A")
      (value "Not Pop.")
      (footprint "eagle-import:R0805-POL")
      (libsource (lib "eagle-import") (part "R-POLR0805"))
    )
    (comp (ref "R21O")
      (value "10k")
      (footprint "eagle-import:RESAD1540W55L620D230")
      (fields
        (field (name "MANUFACTURER_PART_NUMBER") "LR1F10K")
        (field (name "MOUSER_PART_NUMBER") "279-LR1F10K")
      )
      (libsource (lib "eagle-import") (part "LR1F10K"))
    )
    (comp (ref "R22O")
      (value "10k")
      (footprint "eagle-import:RESAD1540W55L620D230")
      (fields
        (field (name "MANUFACTURER_PART_NUMBER") "LR1F10K")
        (field (name "MOUSER_PART_NUMBER") "279-LR1F10K")
      )
      (libsource (lib "eagle-import") (part "LR1F10K"))
    )
    (comp (ref "R23O")
      (value "182")
      (footprint "eagle-import:RESAD1590W60L630D240")
      (fields (field (name "MANUFACTURER_PART_NUMBER") "MF0207FTE52-182R"))
      (libsource (lib "eagle-import") (part "MF0207FTE52-182R"))
    )
    (comp (ref "R24O")
      (value "182")
      (footprint "eagle-import:RESAD1590W60L630D240")
      (fields (field (name "MANUFACTURER_PART_NUMBER") "MF0207FTE52-182R"))
      (libsource (lib "eagle-import") (part "MF0207FTE52-182R"))
    )
    (comp (ref "R25O")
      (value "182")
      (footprint "eagle-import:RESAD1590W60L630D240")
      (fields (field (name "MANUFACTURER_PART_NUMBER") "MF0207FTE52-182R"))
      (libsource (lib "eagle-import") (part "MF0207FTE52-182R"))
    )
    (comp (ref "R26O")
      (value "182")
      (footprint "eagle-import:RESAD1590W60L630D240")
      (fields (field (name "MANUFACTURER_PART_NUMBER") "MF0207FTE52-182R"))
      (libsource (lib "eagle-import") (part "MF0207FTE52-182R"))
    )
    (comp (ref "R27O")
      (value "47kOhm")
      (footprint "eagle-import:RESAD1540W55L620D230")
      (fields
        (field (name "MANUFACTURER_PART_NUMBER") "LR1F47K")
        (field (name "MOUSER_PART_NUMBER") "279-LR1F47K")
      )
      (libsource (lib "eagle-import") (part "LR1F47K"))
    )
    (comp (ref "R28O")
      (value "10k")
      (footprint "eagle-import:RESAD1540W55L620D230")
      (fields
        (field (name "MANUFACTURER_PART_NUMBER") "LR1F10K")
        (field (name "MOUSER_PART_NUMBER") "279-LR1F10K")
      )
      (libsource (lib "eagle-import") (part "LR1F10K"))
    )
    (comp (ref "R29O")
      (value "10k")
      (footprint "eagle-import:RESAD1540W55L620D230")
      (fields
        (field (name "MANUFACTURER_PART_NUMBER") "LR1F10K")
        (field (name "MOUSER_PART_NUMBER") "279-LR1F10K")
      )
      (libsource (lib "eagle-import") (part "LR1F10K"))
    )
    (comp (ref "R30O")
      (value "10k")
      (footprint "eagle-import:RESAD1540W55L620D230")
      (fields
        (field (name "MANUFACTURER_PART_NUMBER") "LR1F10K")
        (field (name "MOUSER_PART_NUMBER") "279-LR1F10K")
      )
      (libsource (lib "eagle-import") (part "LR1F10K"))
    )
    (comp (ref "SH3")
      (value "SHORTA5")
      (footprint "eagle-import:SHORT_ALL-50")
      (libsource (lib "eagle-import") (part "SHORTA5"))
    )
    (comp (ref "SMUTE1")
      (value "SJ")
      (footprint "eagle-import:SJ")
      (libsource (lib "eagle-import") (part "SJ"))
    )
    (comp (ref "SMUTE2")
      (value "SJ")
      (footprint "eagle-import:SJ")
      (libsource (lib "eagle-import") (part "SJ"))
    )
    (comp (ref "SX1")
      (value "VT9-PT")
      (footprint "eagle-import:VT9-PT")
      (libsource (lib "eagle-import") (part "VT9-PT"))
    )
    (comp (ref "SX2")
      (value "VT9-PT")
      (footprint "eagle-import:VT9-PT")
      (libsource (lib "eagle-import") (part "VT9-PT"))
    )
    (comp (ref "TP1")
      (value "TPB2,54")
      (footprint "eagle-import:B2,54")
      (libsource (lib "eagle-import") (part "TPB2,54"))
    )
    (comp (ref "U$1")
      (value "TEENSY40")
      (footprint "eagle-import:TEENSY40")
      (libsource (lib "eagle-import") (part "TEENSY40"))
    )
    (comp (ref "U1")
      (value "AZ1117H-5.0TRE1")
      (footprint "eagle-import:SOT230P700X180-4N")
      (fields (field (name "MOUSER_PART_NUMBER") "621-AZ1117H-5.0TRE1"))
      (libsource (lib "eagle-import") (part "AZ1117H-5.0TRE1"))
    )
    (comp (ref "X1")
      (value "JST-XH-07-PIN-ROUND-PAD")
      (footprint "eagle-import:JST-XH-07-PACKAGE-ROUND-PAD")
      (libsource (lib "eagle-import") (part "JST-XH-07-PIN-ROUND-PAD"))
    )
    (comp (ref "X4")
      (value "JST-XH-04-PIN-ROUND-PAD")
      (footprint "eagle-import:JST-XH-04-PACKAGE-ROUND-PAD")
      (libsource (lib "eagle-import") (part "JST-XH-04-PIN-ROUND-PAD"))
    )
  )
  (nets
    (net (code "1") (name "+3V3") (class "Default")
      (node (ref "C18D") (pin "1") (pinfunction "1_1") (pintype "passive"))
      (node (ref "C22A") (pin "1") (pinfunction "1_1") (pintype "passive"))
      (node (ref "C23A") (pin "1") (pinfunction "1_1") (pintype "passive"))
      (node (ref "C24A") (pin "1") (pinfunction "1_1") (pintype "passive"))
      (node (ref "C26A") (pin "1") (pinfunction "1_1") (pintype "passive"))
      (node (ref "C26B") (pin "1") (pinfunction "1_1") (pintype "passive"))
      (node (ref "C2A1") (pin "1") (pinfunction "1_1") (pintype "passive"))
      (node (ref "C2A2") (pin "1") (pinfunction "1_1") (pintype "passive"))
      (node (ref "C3A") (pin "1") (pinfunction "+_1") (pintype "passive"))
      (node (ref "C3B") (pin "1") (pinfunction "+_1") (pintype "passive"))
      (node (ref "DIF1") (pin "3") (pinfunction "3_3") (pintype "passive"))
      (node (ref "DIF3") (pin "3") (pinfunction "3_3") (pintype "passive"))
      (node (ref "IC2") (pin "14") (pinfunction "INV_14") (pintype "input"))
      (node (ref "IC2") (pin "15") (pinfunction "DEM0_15") (pintype "input"))
      (node (ref "IC2") (pin "17") (pinfunction "ACKS_17") (pintype "input"))
      (node (ref "IC2") (pin "48") (pinfunction "TVDD_48") (pintype "power_in"))
      (node (ref "IC3") (pin "14") (pinfunction "INV_14") (pintype "input"))
      (node (ref "IC3") (pin "15") (pinfunction "DEM0_15") (pintype "input"))
      (node (ref "IC3") (pin "17") (pinfunction "ACKS_17") (pintype "input"))
      (node (ref "IC3") (pin "48") (pinfunction "TVDD_48") (pintype "power_in"))
      (node (ref "IC4A") (pin "20") (pinfunction "VCC_20") (pintype "bidirectional"))
      (node (ref "IC6") (pin "10") (pinfunction "OUT_10") (pintype "bidirectional"))
      (node (ref "IC6") (pin "9") (pinfunction "OUTS_9") (pintype "bidirectional"))
      (node (ref "J11") (pin "2") (pinfunction "2_2") (pintype "passive"))
      (node (ref "J18") (pin "6") (pinfunction "6_6") (pintype "bidirectional"))
      (node (ref "J22") (pin "1") (pinfunction "1_1") (pintype "passive"))
      (node (ref "J5") (pin "5") (pinfunction "5_5") (pintype "passive"))
      (node (ref "J7") (pin "2") (pinfunction "2_2") (pintype "passive"))
      (node (ref "J9") (pin "5") (pinfunction "5_5") (pintype "passive"))
      (node (ref "LDO7") (pin "1") (pinfunction "VIN_1") (pintype "bidirectional"))
      (node (ref "LDO7") (pin "3") (pinfunction "EN_3") (pintype "bidirectional"))
      (node (ref "LDO8") (pin "1") (pinfunction "VIN_1") (pintype "bidirectional"))
      (node (ref "LDO8") (pin "3") (pinfunction "EN_3") (pintype "bidirectional"))
      (node (ref "R10") (pin "1") (pinfunction "1_1") (pintype "passive"))
      (node (ref "R20") (pin "1") (pinfunction "1_1") (pintype "passive"))
      (node (ref "R5A") (pin "2") (pinfunction "2_2") (pintype "passive"))
    )
    (net (code "2") (name "+5V{slash}1") (class "Default")
      (node (ref "C10A1") (pin "1") (pinfunction "1_1") (pintype "passive"))
      (node (ref "C11A") (pin "1") (pinfunction "+_1") (pintype "passive"))
      (node (ref "C14A1") (pin "1") (pinfunction "1_1") (pintype "passive"))
      (node (ref "C15A") (pin "1") (pinfunction "+_1") (pintype "passive"))
      (node (ref "C16A1") (pin "1") (pinfunction "1_1") (pintype "passive"))
      (node (ref "C17A") (pin "1") (pinfunction "+_1") (pintype "passive"))
      (node (ref "C18A") (pin "1") (pinfunction "1_1") (pintype "passive"))
      (node (ref "C6A1") (pin "1") (pinfunction "1_1") (pintype "passive"))
      (node (ref "C7A") (pin "1") (pinfunction "+_1") (pintype "passive"))
      (node (ref "IC1") (pin "10") (pinfunction "OUT_10") (pintype "bidirectional"))
      (node (ref "IC1") (pin "9") (pinfunction "OUTS_9") (pintype "bidirectional"))
      (node (ref "IC2") (pin "19") (pinfunction "VREFHR_19") (pintype "input"))
      (node (ref "IC2") (pin "20") (pinfunction "VREFHR2_20") (pintype "input"))
      (node (ref "IC2") (pin "27") (pinfunction "VDDR_27") (pintype "power_in"))
      (node (ref "IC2") (pin "28") (pinfunction "VDDR2_28") (pintype "power_in"))
      (node (ref "IC2") (pin "33") (pinfunction "VDDL_33") (pintype "power_in"))
      (node (ref "IC2") (pin "34") (pinfunction "VDDL2_34") (pintype "power_in"))
      (node (ref "IC2") (pin "41") (pinfunction "VREFHL_41") (pintype "input"))
      (node (ref "IC2") (pin "42") (pinfunction "VREFHL2_42") (pintype "input"))
      (node (ref "J15") (pin "6") (pinfunction "6_6") (pintype "bidirectional"))
      (node (ref "J5") (pin "4") (pinfunction "4_4") (pintype "passive"))
      (node (ref "J6") (pin "4") (pinfunction "4_4") (pintype "passive"))
      (node (ref "J6") (pin "5") (pinfunction "5_5") (pintype "passive"))
      (node (ref "J7") (pin "6") (pinfunction "6_6") (pintype "passive"))
    )
    (net (code "3") (name "+5V{slash}2") (class "Default")
      (node (ref "C10A2") (pin "1") (pinfunction "1_1") (pintype "passive"))
      (node (ref "C11B") (pin "1") (pinfunction "+_1") (pintype "passive"))
      (node (ref "C14A2") (pin "1") (pinfunction "1_1") (pintype "passive"))
      (node (ref "C15B") (pin "1") (pinfunction "+_1") (pintype "passive"))
      (node (ref "C16A2") (pin "1") (pinfunction "1_1") (pintype "passive"))
      (node (ref "C17B") (pin "1") (pinfunction "+_1") (pintype "passive"))
      (node (ref "C18B") (pin "1") (pinfunction "1_1") (pintype "passive"))
      (node (ref "C6A2") (pin "1") (pinfunction "1_1") (pintype "passive"))
      (node (ref "C7B") (pin "1") (pinfunction "+_1") (pintype "passive"))
      (node (ref "IC3") (pin "19") (pinfunction "VREFHR_19") (pintype "input"))
      (node (ref "IC3") (pin "20") (pinfunction "VREFHR2_20") (pintype "input"))
      (node (ref "IC3") (pin "27") (pinfunction "VDDR_27") (pintype "power_in"))
      (node (ref "IC3") (pin "28") (pinfunction "VDDR2_28") (pintype "power_in"))
      (node (ref "IC3") (pin "33") (pinfunction "VDDL_33") (pintype "power_in"))
      (node (ref "IC3") (pin "34") (pinfunction "VDDL2_34") (pintype "power_in"))
      (node (ref "IC3") (pin "41") (pinfunction "VREFHL_41") (pintype "input"))
      (node (ref "IC3") (pin "42") (pinfunction "VREFHL2_42") (pintype "input"))
      (node (ref "IC5") (pin "10") (pinfunction "OUT_10") (pintype "bidirectional"))
      (node (ref "IC5") (pin "9") (pinfunction "OUTS_9") (pintype "bidirectional"))
      (node (ref "J10") (pin "4") (pinfunction "4_4") (pintype "passive"))
      (node (ref "J10") (pin "5") (pinfunction "5_5") (pintype "passive"))
      (node (ref "J11") (pin "6") (pinfunction "6_6") (pintype "passive"))
      (node (ref "J17") (pin "6") (pinfunction "6_6") (pintype "bidirectional"))
      (node (ref "J9") (pin "4") (pinfunction "4_4") (pintype "passive"))
    )
    (net (code "4") (name "+5V{slash}3") (class "Default")
      (node (ref "BD1") (pin "H3.17") (pinfunction "H3.17_H3.17") (pintype "passive"))
      (node (ref "C18E") (pin "1") (pinfunction "1_1") (pintype "passive"))
      (node (ref "IC8") (pin "10") (pinfunction "OUT_10") (pintype "bidirectional"))
      (node (ref "IC8") (pin "9") (pinfunction "OUTS_9") (pintype "bidirectional"))
      (node (ref "J20") (pin "6") (pinfunction "6_6") (pintype "bidirectional"))
    )
    (net (code "5") (name "+5V{slash}4") (class "Default")
      (node (ref "C18F") (pin "1") (pinfunction "1_1") (pintype "passive"))
      (node (ref "C4A2") (pin "1") (pinfunction "1_1") (pintype "passive"))
      (node (ref "C5B") (pin "1") (pinfunction "+_1") (pintype "passive"))
      (node (ref "IC3") (pin "44") (pinfunction "AVDD_44") (pintype "power_in"))
      (node (ref "IC7") (pin "10") (pinfunction "OUT_10") (pintype "bidirectional"))
      (node (ref "IC7") (pin "9") (pinfunction "OUTS_9") (pintype "bidirectional"))
      (node (ref "J11") (pin "5") (pinfunction "5_5") (pintype "passive"))
      (node (ref "J19") (pin "6") (pinfunction "6_6") (pintype "bidirectional"))
    )
    (net (code "6") (name "+5V{slash}5") (class "Default")
      (node (ref "C18C") (pin "1") (pinfunction "1_1") (pintype "passive"))
      (node (ref "C4A1") (pin "1") (pinfunction "1_1") (pintype "passive"))
      (node (ref "C5A") (pin "1") (pinfunction "+_1") (pintype "passive"))
      (node (ref "IC2") (pin "44") (pinfunction "AVDD_44") (pintype "power_in"))
      (node (ref "IC4") (pin "10") (pinfunction "OUT_10") (pintype "bidirectional"))
      (node (ref "IC4") (pin "9") (pinfunction "OUTS_9") (pintype "bidirectional"))
      (node (ref "J16") (pin "6") (pinfunction "6_6") (pintype "bidirectional"))
      (node (ref "J7") (pin "5") (pinfunction "5_5") (pintype "passive"))
    )
    (net (code "7") (name "+240VDC") (class "Default")
      (node (ref "C18O") (pin "1") (pinfunction "1_1") (pintype "passive"))
      (node (ref "C3P") (pin "1") (pinfunction "+_1") (pintype "bidirectional"))
      (node (ref "C4O") (pin "1") (pinfunction "1_1") (pintype "passive"))
      (node (ref "C5P") (pin "1") (pinfunction "+_1") (pintype "bidirectional"))
      (node (ref "C6P") (pin "1") (pinfunction "+_1") (pintype "bidirectional"))
      (node (ref "C7P") (pin "1") (pinfunction "+_1") (pintype "bidirectional"))
      (node (ref "R6P") (pin "1") (pinfunction "1_1") (pintype "passive"))
      (node (ref "SX1") (pin "6") (pinfunction "6_6") (pintype "passive"))
      (node (ref "SX2") (pin "6") (pinfunction "6_6") (pintype "passive"))
    )
    (net (code "8") (name "6.3_VAC_BLU") (class "Default")
      (node (ref "C1") (pin "2") (pinfunction "2_2") (pintype "passive"))
      (node (ref "C2") (pin "2") (pinfunction "2_2") (pintype "passive"))
      (node (ref "C3") (pin "1") (pinfunction "1_1") (pintype "passive"))
      (node (ref "D6") (pin "1") (pinfunction "K_1") (pintype "bidirectional"))
      (node (ref "D7") (pin "2") (pinfunction "A_2") (pintype "bidirectional"))
      (node (ref "IN") (pin "5") (pinfunction "5_5") (pintype "bidirectional"))
    )
    (net (code "9") (name "6.3_VAC_GRN") (class "Default")
      (node (ref "C1") (pin "1") (pinfunction "1_1") (pintype "passive"))
      (node (ref "C4") (pin "2") (pinfunction "2_2") (pintype "passive"))
      (node (ref "C5") (pin "1") (pinfunction "1_1") (pintype "passive"))
      (node (ref "D5") (pin "1") (pinfunction "K_1") (pintype "bidirectional"))
      (node (ref "D8") (pin "2") (pinfunction "A_2") (pintype "bidirectional"))
      (node (ref "IN") (pin "6") (pinfunction "6_6") (pintype "bidirectional"))
    )
    (net (code "10") (name "66.3VAC{slash}1") (class "Default")
      (node (ref "IN") (pin "1") (pinfunction "1_1") (pintype "bidirectional"))
      (node (ref "R2P") (pin "2") (pinfunction "2_2") (pintype "passive"))
      (node (ref "SX1") (pin "4") (pinfunction "4_4") (pintype "passive"))
      (node (ref "SX2") (pin "4") (pinfunction "4_4") (pintype "passive"))
    )
    (net (code "11") (name "66.3VAC{slash}2") (class "Default")
      (node (ref "IN") (pin "2") (pinfunction "2_2") (pintype "bidirectional"))
      (node (ref "R3P") (pin "1") (pinfunction "1_1") (pintype "passive"))
      (node (ref "SX1") (pin "5") (pinfunction "5_5") (pintype "passive"))
      (node (ref "SX2") (pin "5") (pinfunction "5_5") (pintype "passive"))
    )
    (net (code "12") (name "115_VAC_BLK") (class "Default")
      (node (ref "D1") (pin "1") (pinfunction "K_1") (pintype "bidirectional"))
      (node (ref "D4") (pin "2") (pinfunction "A_2") (pintype "bidirectional"))
      (node (ref "IN") (pin "4") (pinfunction "4_4") (pintype "bidirectional"))
    )
    (net (code "13") (name "115_VAC_RED") (class "Default")
      (node (ref "D2") (pin "1") (pinfunction "K_1") (pintype "bidirectional"))
      (node (ref "D3") (pin "2") (pinfunction "A_2") (pintype "bidirectional"))
      (node (ref "IN") (pin "3") (pinfunction "3_3") (pintype "bidirectional"))
    )
    (net (code "14") (name "AGND") (class "Default")
      (node (ref "C10A1") (pin "2") (pinfunction "2_2") (pintype "passive"))
      (node (ref "C10A2") (pin "2") (pinfunction "2_2") (pintype "passive"))
      (node (ref "C10O") (pin "2") (pinfunction "2_2") (pintype "passive"))
      (node (ref "C11A") (pin "2") (pinfunction "-_2") (pintype "passive"))
      (node (ref "C11B") (pin "2") (pinfunction "-_2") (pintype "passive"))
      (node (ref "C12A1") (pin "2") (pinfunction "2_2") (pintype "passive"))
      (node (ref "C12A2") (pin "2") (pinfunction "2_2") (pintype "passive"))
      (node (ref "C13A") (pin "2") (pinfunction "-_2") (pintype "passive"))
      (node (ref "C13B") (pin "2") (pinfunction "-_2") (pintype "passive"))
      (node (ref "C14A1") (pin "2") (pinfunction "2_2") (pintype "passive"))
      (node (ref "C14A2") (pin "2") (pinfunction "2_2") (pintype "passive"))
      (node (ref "C15A") (pin "2") (pinfunction "-_2") (pintype "passive"))
      (node (ref "C15B") (pin "2") (pinfunction "-_2") (pintype "passive"))
      (node (ref "C16A1") (pin "2") (pinfunction "2_2") (pintype "passive"))
      (node (ref "C16A2") (pin "2") (pinfunction "2_2") (pintype "passive"))
      (node (ref "C16O") (pin "2") (pinfunction "2_2") (pintype "passive"))
      (node (ref "C17A") (pin "2") (pinfunction "-_2") (pintype "passive"))
      (node (ref "C17B") (pin "2") (pinfunction "-_2") (pintype "passive"))
      (node (ref "C18O") (pin "2") (pinfunction "2_2") (pintype "passive"))
      (node (ref "C1O") (pin "2") (pinfunction "2_2") (pintype "passive"))
      (node (ref "C2O") (pin "2") (pinfunction "2_2") (pintype "passive"))
      (node (ref "C4A1") (pin "2") (pinfunction "2_2") (pintype "passive"))
      (node (ref "C4A2") (pin "2") (pinfunction "2_2") (pintype "passive"))
      (node (ref "C4O") (pin "2") (pinfunction "2_2") (pintype "passive"))
      (node (ref "C5A") (pin "2") (pinfunction "-_2") (pintype "passive"))
      (node (ref "C5B") (pin "2") (pinfunction "-_2") (pintype "passive"))
      (node (ref "C6A1") (pin "2") (pinfunction "2_2") (pintype "passive"))
      (node (ref "C6A2") (pin "2") (pinfunction "2_2") (pintype "passive"))
      (node (ref "C7A") (pin "2") (pinfunction "-_2") (pintype "passive"))
      (node (ref "C7B") (pin "2") (pinfunction "-_2") (pintype "passive"))
      (node (ref "C8A1") (pin "2") (pinfunction "2_2") (pintype "passive"))
      (node (ref "C8A2") (pin "2") (pinfunction "2_2") (pintype "passive"))
      (node (ref "C9A") (pin "2") (pinfunction "-_2") (pintype "passive"))
      (node (ref "C9B") (pin "2") (pinfunction "-_2") (pintype "passive"))
      (node (ref "IC2") (pin "21") (pinfunction "VREFLR_21") (pintype "input"))
      (node (ref "IC2") (pin "22") (pinfunction "VREFLR2_22") (pintype "input"))
      (node (ref "IC2") (pin "29") (pinfunction "VSSR_29") (pintype "power_in"))
      (node (ref "IC2") (pin "30") (pinfunction "VSSR2_30") (pintype "power_in"))
      (node (ref "IC2") (pin "31") (pinfunction "VSSL_31") (pintype "power_in"))
      (node (ref "IC2") (pin "32") (pinfunction "VSSL2_32") (pintype "power_in"))
      (node (ref "IC2") (pin "39") (pinfunction "VREFLL_39") (pintype "input"))
      (node (ref "IC2") (pin "40") (pinfunction "VREFLL2_40") (pintype "input"))
      (node (ref "IC2") (pin "45") (pinfunction "AVSS_45") (pintype "power_in"))
      (node (ref "IC2") (pin "P$1") (pinfunction "AVSS_P$1") (pintype "power_in"))
      (node (ref "IC2") (pin "P$10") (pinfunction "AVSS_P$10") (pintype "power_in"))
      (node (ref "IC2") (pin "P$11") (pinfunction "AVSS_P$11") (pintype "power_in"))
      (node (ref "IC2") (pin "P$12") (pinfunction "AVSS_P$12") (pintype "power_in"))
      (node (ref "IC2") (pin "P$13") (pinfunction "AVSS_P$13") (pintype "power_in"))
      (node (ref "IC2") (pin "P$14") (pinfunction "AVSS_P$14") (pintype "power_in"))
      (node (ref "IC2") (pin "P$15") (pinfunction "AVSS_P$15") (pintype "power_in"))
      (node (ref "IC2") (pin "P$16") (pinfunction "AVSS_P$16") (pintype "power_in"))
      (node (ref "IC2") (pin "P$17") (pinfunction "AVSS_P$17") (pintype "power_in"))
      (node (ref "IC2") (pin "P$18") (pinfunction "AVSS_P$18") (pintype "power_in"))
      (node (ref "IC2") (pin "P$19") (pinfunction "AVSS_P$19") (pintype "power_in"))
      (node (ref "IC2") (pin "P$2") (pinfunction "AVSS_P$2") (pintype "power_in"))
      (node (ref "IC2") (pin "P$20") (pinfunction "AVSS_P$20") (pintype "power_in"))
      (node (ref "IC2") (pin "P$21") (pinfunction "AVSS_P$21") (pintype "power_in"))
      (node (ref "IC2") (pin "P$22") (pinfunction "AVSS_P$22") (pintype "power_in"))
      (node (ref "IC2") (pin "P$23") (pinfunction "AVSS_P$23") (pintype "power_in"))
      (node (ref "IC2") (pin "P$24") (pinfunction "AVSS_P$24") (pintype "power_in"))
      (node (ref "IC2") (pin "P$25") (pinfunction "AVSS_P$25") (pintype "power_in"))
      (node (ref "IC2") (pin "P$3") (pinfunction "AVSS_P$3") (pintype "power_in"))
      (node (ref "IC2") (pin "P$4") (pinfunction "AVSS_P$4") (pintype "power_in"))
      (node (ref "IC2") (pin "P$5") (pinfunction "AVSS_P$5") (pintype "power_in"))
      (node (ref "IC2") (pin "P$6") (pinfunction "AVSS_P$6") (pintype "power_in"))
      (node (ref "IC2") (pin "P$7") (pinfunction "AVSS_P$7") (pintype "power_in"))
      (node (ref "IC2") (pin "P$8") (pinfunction "AVSS_P$8") (pintype "power_in"))
      (node (ref "IC2") (pin "P$9") (pinfunction "AVSS_P$9") (pintype "power_in"))
      (node (ref "IC3") (pin "21") (pinfunction "VREFLR_21") (pintype "input"))
      (node (ref "IC3") (pin "22") (pinfunction "VREFLR2_22") (pintype "input"))
      (node (ref "IC3") (pin "29") (pinfunction "VSSR_29") (pintype "power_in"))
      (node (ref "IC3") (pin "30") (pinfunction "VSSR2_30") (pintype "power_in"))
      (node (ref "IC3") (pin "31") (pinfunction "VSSL_31") (pintype "power_in"))
      (node (ref "IC3") (pin "32") (pinfunction "VSSL2_32") (pintype "power_in"))
      (node (ref "IC3") (pin "39") (pinfunction "VREFLL_39") (pintype "input"))
      (node (ref "IC3") (pin "40") (pinfunction "VREFLL2_40") (pintype "input"))
      (node (ref "IC3") (pin "45") (pinfunction "AVSS_45") (pintype "power_in"))
      (node (ref "IC3") (pin "P$1") (pinfunction "AVSS_P$1") (pintype "power_in"))
      (node (ref "IC3") (pin "P$10") (pinfunction "AVSS_P$10") (pintype "power_in"))
      (node (ref "IC3") (pin "P$11") (pinfunction "AVSS_P$11") (pintype "power_in"))
      (node (ref "IC3") (pin "P$12") (pinfunction "AVSS_P$12") (pintype "power_in"))
      (node (ref "IC3") (pin "P$13") (pinfunction "AVSS_P$13") (pintype "power_in"))
      (node (ref "IC3") (pin "P$14") (pinfunction "AVSS_P$14") (pintype "power_in"))
      (node (ref "IC3") (pin "P$15") (pinfunction "AVSS_P$15") (pintype "power_in"))
      (node (ref "IC3") (pin "P$16") (pinfunction "AVSS_P$16") (pintype "power_in"))
      (node (ref "IC3") (pin "P$17") (pinfunction "AVSS_P$17") (pintype "power_in"))
      (node (ref "IC3") (pin "P$18") (pinfunction "AVSS_P$18") (pintype "power_in"))
      (node (ref "IC3") (pin "P$19") (pinfunction "AVSS_P$19") (pintype "power_in"))
      (node (ref "IC3") (pin "P$2") (pinfunction "AVSS_P$2") (pintype "power_in"))
      (node (ref "IC3") (pin "P$20") (pinfunction "AVSS_P$20") (pintype "power_in"))
      (node (ref "IC3") (pin "P$21") (pinfunction "AVSS_P$21") (pintype "power_in"))
      (node (ref "IC3") (pin "P$22") (pinfunction "AVSS_P$22") (pintype "power_in"))
      (node (ref "IC3") (pin "P$23") (pinfunction "AVSS_P$23") (pintype "power_in"))
      (node (ref "IC3") (pin "P$24") (pinfunction "AVSS_P$24") (pintype "power_in"))
      (node (ref "IC3") (pin "P$25") (pinfunction "AVSS_P$25") (pintype "power_in"))
      (node (ref "IC3") (pin "P$3") (pinfunction "AVSS_P$3") (pintype "power_in"))
      (node (ref "IC3") (pin "P$4") (pinfunction "AVSS_P$4") (pintype "power_in"))
      (node (ref "IC3") (pin "P$5") (pinfunction "AVSS_P$5") (pintype "power_in"))
      (node (ref "IC3") (pin "P$6") (pinfunction "AVSS_P$6") (pintype "power_in"))
      (node (ref "IC3") (pin "P$7") (pinfunction "AVSS_P$7") (pintype "power_in"))
      (node (ref "IC3") (pin "P$8") (pinfunction "AVSS_P$8") (pintype "power_in"))
      (node (ref "IC3") (pin "P$9") (pinfunction "AVSS_P$9") (pintype "power_in"))
      (node (ref "J10") (pin "2") (pinfunction "2_2") (pintype "passive"))
      (node (ref "J10") (pin "7") (pinfunction "7_7") (pintype "passive"))
      (node (ref "J26") (pin "1") (pinfunction "SLEEVE_1") (pintype "bidirectional"))
      (node (ref "J5") (pin "3") (pinfunction "3_3") (pintype "passive"))
      (node (ref "J6") (pin "2") (pinfunction "2_2") (pintype "passive"))
      (node (ref "J6") (pin "7") (pinfunction "7_7") (pintype "passive"))
      (node (ref "J9") (pin "3") (pinfunction "3_3") (pintype "passive"))
      (node (ref "R11O") (pin "2") (pinfunction "2_2") (pintype "passive"))
      (node (ref "R19O") (pin "1") (pinfunction "1_1") (pintype "passive"))
      (node (ref "R20O") (pin "2") (pinfunction "2_2") (pintype "passive"))
      (node (ref "R21O") (pin "1") (pinfunction "1_1") (pintype "passive"))
      (node (ref "R22O") (pin "2") (pinfunction "2_2") (pintype "passive"))
      (node (ref "R28O") (pin "1") (pinfunction "1_1") (pintype "passive"))
      (node (ref "R29O") (pin "2") (pinfunction "2_2") (pintype "passive"))
      (node (ref "R30O") (pin "1") (pinfunction "1_1") (pintype "passive"))
      (node (ref "R3O") (pin "2") (pinfunction "2_2") (pintype "passive"))
      (node (ref "R5O") (pin "1") (pinfunction "1_1") (pintype "passive"))
      (node (ref "R7O") (pin "2") (pinfunction "2_2") (pintype "passive"))
      (node (ref "R8O") (pin "1") (pinfunction "1_1") (pintype "passive"))
      (node (ref "SH3") (pin "2") (pinfunction "P$2_2") (pintype "bidirectional"))
    )
    (net (code "15") (name "BCLK") (class "Default")
      (node (ref "BD1") (pin "H3.11") (pinfunction "H3.11_H3.11") (pintype "passive"))
      (node (ref "IC4A") (pin "18") (pinfunction "8D_18") (pintype "bidirectional"))
      (node (ref "IC4A") (pin "8") (pinfunction "4D_8") (pintype "bidirectional"))
      (node (ref "J21") (pin "3") (pinfunction "3_3") (pintype "passive"))
      (node (ref "J22") (pin "3") (pinfunction "3_3") (pintype "passive"))
    )
    (net (code "16") (name "DATA") (class "Default")
      (node (ref "BD1") (pin "H3.13") (pinfunction "H3.13_H3.13") (pintype "passive"))
      (node (ref "IC4A") (pin "14") (pinfunction "6D_14") (pintype "bidirectional"))
      (node (ref "IC4A") (pin "4") (pinfunction "2D_4") (pintype "bidirectional"))
      (node (ref "J21") (pin "7") (pinfunction "7_7") (pintype "passive"))
      (node (ref "J22") (pin "7") (pinfunction "7_7") (pintype "passive"))
    )
    (net (code "17") (name "DGND") (class "Default")
      (node (ref "BD1") (pin "H3.10") (pinfunction "H3.10_H3.10") (pintype "passive"))
      (node (ref "BD1") (pin "H3.12") (pinfunction "H3.12_H3.12") (pintype "passive"))
      (node (ref "BD1") (pin "H3.14") (pinfunction "H3.14_H3.14") (pintype "passive"))
      (node (ref "BD1") (pin "H3.16") (pinfunction "H3.16_H3.16") (pintype "passive"))
      (node (ref "BD1") (pin "H3.19") (pinfunction "H3.19_H3.19") (pintype "passive"))
      (node (ref "BD1") (pin "H3.8") (pinfunction "H3.8_H3.8") (pintype "passive"))
      (node (ref "C18A") (pin "2") (pinfunction "2_2") (pintype "passive"))
      (node (ref "C18B") (pin "2") (pinfunction "2_2") (pintype "passive"))
      (node (ref "C18C") (pin "2") (pinfunction "2_2") (pintype "passive"))
      (node (ref "C18D") (pin "2") (pinfunction "2_2") (pintype "passive"))
      (node (ref "C18E") (pin "2") (pinfunction "2_2") (pintype "passive"))
      (node (ref "C18F") (pin "2") (pinfunction "2_2") (pintype "passive"))
      (node (ref "C19A") (pin "2") (pinfunction "2_2") (pintype "passive"))
      (node (ref "C19A") (pin "DGND") (pinfunction "2_DGND") (pintype "passive"))
      (node (ref "C19B") (pin "2") (pinfunction "2_2") (pintype "passive"))
      (node (ref "C19B") (pin "DGND") (pinfunction "2_DGND") (pintype "passive"))
      (node (ref "C19C") (pin "2") (pinfunction "2_2") (pintype "passive"))
      (node (ref "C19C") (pin "DGND") (pinfunction "2_DGND") (pintype "passive"))
      (node (ref "C19D") (pin "2") (pinfunction "2_2") (pintype "passive"))
      (node (ref "C19D") (pin "DGND") (pinfunction "2_DGND") (pintype "passive"))
      (node (ref "C19E") (pin "2") (pinfunction "2_2") (pintype "passive"))
      (node (ref "C19E") (pin "DGND") (pinfunction "2_DGND") (pintype "passive"))
      (node (ref "C19F") (pin "2") (pinfunction "2_2") (pintype "passive"))
      (node (ref "C19F") (pin "DGND") (pinfunction "2_DGND") (pintype "passive"))
      (node (ref "C1A") (pin "2") (pinfunction "2_2") (pintype "passive"))
      (node (ref "C1P") (pin "2") (pinfunction "-_2") (pintype "bidirectional"))
      (node (ref "C1P1") (pin "2") (pinfunction "-_2") (pintype "bidirectional"))
      (node (ref "C20A") (pin "2") (pinfunction "2_2") (pintype "passive"))
      (node (ref "C20B") (pin "2") (pinfunction "2_2") (pintype "passive"))
      (node (ref "C20C") (pin "2") (pinfunction "2_2") (pintype "passive"))
      (node (ref "C20D") (pin "2") (pinfunction "2_2") (pintype "passive"))
      (node (ref "C20E") (pin "2") (pinfunction "2_2") (pintype "passive"))
      (node (ref "C20F") (pin "2") (pinfunction "2_2") (pintype "passive"))
      (node (ref "C21A") (pin "2") (pinfunction "2_2") (pintype "passive"))
      (node (ref "C21B") (pin "2") (pinfunction "2_2") (pintype "passive"))
      (node (ref "C21C") (pin "2") (pinfunction "2_2") (pintype "passive"))
      (node (ref "C21D") (pin "2") (pinfunction "2_2") (pintype "passive"))
      (node (ref "C21E") (pin "2") (pinfunction "2_2") (pintype "passive"))
      (node (ref "C21F") (pin "2") (pinfunction "2_2") (pintype "passive"))
      (node (ref "C22A") (pin "2") (pinfunction "2_2") (pintype "passive"))
      (node (ref "C23A") (pin "2") (pinfunction "2_2") (pintype "passive"))
      (node (ref "C24A") (pin "2") (pinfunction "2_2") (pintype "passive"))
      (node (ref "C26A") (pin "2") (pinfunction "2_2") (pintype "passive"))
      (node (ref "C26B") (pin "2") (pinfunction "2_2") (pintype "passive"))
      (node (ref "C27A") (pin "2") (pinfunction "2_2") (pintype "passive"))
      (node (ref "C27B") (pin "2") (pinfunction "2_2") (pintype "passive"))
      (node (ref "C28A") (pin "2") (pinfunction "2_2") (pintype "passive"))
      (node (ref "C28B") (pin "2") (pinfunction "2_2") (pintype "passive"))
      (node (ref "C2A1") (pin "2") (pinfunction "2_2") (pintype "passive"))
      (node (ref "C2A2") (pin "2") (pinfunction "2_2") (pintype "passive"))
      (node (ref "C2P") (pin "2") (pinfunction "-_2") (pintype "bidirectional"))
      (node (ref "C2P1") (pin "2") (pinfunction "-_2") (pintype "bidirectional"))
      (node (ref "C3") (pin "2") (pinfunction "2_2") (pintype "passive"))
      (node (ref "C3A") (pin "2") (pinfunction "-_2") (pintype "passive"))
      (node (ref "C3B") (pin "2") (pinfunction "-_2") (pintype "passive"))
      (node (ref "C3P") (pin "2") (pinfunction "-_2") (pintype "bidirectional"))
      (node (ref "C3P1") (pin "2") (pinfunction "-_2") (pintype "bidirectional"))
      (node (ref "C4P") (pin "2") (pinfunction "-_2") (pintype "bidirectional"))
      (node (ref "C5") (pin "2") (pinfunction "2_2") (pintype "passive"))
      (node (ref "C5P") (pin "2") (pinfunction "-_2") (pintype "bidirectional"))
      (node (ref "C5P1") (pin "2") (pinfunction "-_2") (pintype "bidirectional"))
      (node (ref "C6") (pin "2") (pinfunction "2_2") (pintype "passive"))
      (node (ref "C6P") (pin "2") (pinfunction "-_2") (pintype "bidirectional"))
      (node (ref "C6P1") (pin "2") (pinfunction "-_2") (pintype "bidirectional"))
      (node (ref "C7") (pin "1") (pinfunction "1_1") (pintype "passive"))
      (node (ref "C7P") (pin "2") (pinfunction "-_2") (pintype "bidirectional"))
      (node (ref "C7P1") (pin "2") (pinfunction "-_2") (pintype "bidirectional"))
      (node (ref "D1") (pin "2") (pinfunction "A_2") (pintype "bidirectional"))
      (node (ref "D2") (pin "2") (pinfunction "A_2") (pintype "bidirectional"))
      (node (ref "D5") (pin "2") (pinfunction "A_2") (pintype "bidirectional"))
      (node (ref "D6") (pin "2") (pinfunction "A_2") (pintype "bidirectional"))
      (node (ref "DIF1") (pin "1") (pinfunction "1_1") (pintype "passive"))
      (node (ref "DIF3") (pin "1") (pinfunction "1_1") (pintype "passive"))
      (node (ref "IC1") (pin "11") (pinfunction "GND_11") (pintype "bidirectional"))
      (node (ref "IC1") (pin "8") (pinfunction "GND_8") (pintype "bidirectional"))
      (node (ref "IC1") (pin "P$1") (pinfunction "GND_P$1") (pintype "bidirectional"))
      (node (ref "IC1") (pin "P$2") (pinfunction "GND_P$2") (pintype "bidirectional"))
      (node (ref "IC1") (pin "P$3") (pinfunction "GND_P$3") (pintype "bidirectional"))
      (node (ref "IC1") (pin "P$4") (pinfunction "GND_P$4") (pintype "bidirectional"))
      (node (ref "IC1") (pin "P$5") (pinfunction "GND_P$5") (pintype "bidirectional"))
      (node (ref "IC1") (pin "P$6") (pinfunction "GND_P$6") (pintype "bidirectional"))
      (node (ref "IC2") (pin "13") (pinfunction "PSN_13") (pintype "input"))
      (node (ref "IC2") (pin "16") (pinfunction "LDOE_16") (pintype "input"))
      (node (ref "IC2") (pin "47") (pinfunction "DVSS_47") (pintype "power_in"))
      (node (ref "IC2") (pin "6") (pinfunction "SSLOW_6") (pintype "input"))
      (node (ref "IC3") (pin "13") (pinfunction "PSN_13") (pintype "input"))
      (node (ref "IC3") (pin "16") (pinfunction "LDOE_16") (pintype "input"))
      (node (ref "IC3") (pin "47") (pinfunction "DVSS_47") (pintype "power_in"))
      (node (ref "IC3") (pin "6") (pinfunction "SSLOW_6") (pintype "input"))
      (node (ref "IC4") (pin "11") (pinfunction "GND_11") (pintype "bidirectional"))
      (node (ref "IC4") (pin "8") (pinfunction "GND_8") (pintype "bidirectional"))
      (node (ref "IC4") (pin "P$1") (pinfunction "GND_P$1") (pintype "bidirectional"))
      (node (ref "IC4") (pin "P$2") (pinfunction "GND_P$2") (pintype "bidirectional"))
      (node (ref "IC4") (pin "P$3") (pinfunction "GND_P$3") (pintype "bidirectional"))
      (node (ref "IC4") (pin "P$4") (pinfunction "GND_P$4") (pintype "bidirectional"))
      (node (ref "IC4") (pin "P$5") (pinfunction "GND_P$5") (pintype "bidirectional"))
      (node (ref "IC4") (pin "P$6") (pinfunction "GND_P$6") (pintype "bidirectional"))
      (node (ref "IC4A") (pin "10") (pinfunction "GND_10") (pintype "bidirectional"))
      (node (ref "IC4A") (pin "17") (pinfunction "7D_17") (pintype "bidirectional"))
      (node (ref "IC4A") (pin "7") (pinfunction "3D_7") (pintype "bidirectional"))
      (node (ref "IC5") (pin "11") (pinfunction "GND_11") (pintype "bidirectional"))
      (node (ref "IC5") (pin "8") (pinfunction "GND_8") (pintype "bidirectional"))
      (node (ref "IC5") (pin "P$1") (pinfunction "GND_P$1") (pintype "bidirectional"))
      (node (ref "IC5") (pin "P$2") (pinfunction "GND_P$2") (pintype "bidirectional"))
      (node (ref "IC5") (pin "P$3") (pinfunction "GND_P$3") (pintype "bidirectional"))
      (node (ref "IC5") (pin "P$4") (pinfunction "GND_P$4") (pintype "bidirectional"))
      (node (ref "IC5") (pin "P$5") (pinfunction "GND_P$5") (pintype "bidirectional"))
      (node (ref "IC5") (pin "P$6") (pinfunction "GND_P$6") (pintype "bidirectional"))
      (node (ref "IC6") (pin "11") (pinfunction "GND_11") (pintype "bidirectional"))
      (node (ref "IC6") (pin "8") (pinfunction "GND_8") (pintype "bidirectional"))
      (node (ref "IC6") (pin "P$1") (pinfunction "GND_P$1") (pintype "bidirectional"))
      (node (ref "IC6") (pin "P$2") (pinfunction "GND_P$2") (pintype "bidirectional"))
      (node (ref "IC6") (pin "P$3") (pinfunction "GND_P$3") (pintype "bidirectional"))
      (node (ref "IC6") (pin "P$4") (pinfunction "GND_P$4") (pintype "bidirectional"))
      (node (ref "IC6") (pin "P$5") (pinfunction "GND_P$5") (pintype "bidirectional"))
      (node (ref "IC6") (pin "P$6") (pinfunction "GND_P$6") (pintype "bidirectional"))
      (node (ref "IC7") (pin "11") (pinfunction "GND_11") (pintype "bidirectional"))
      (node (ref "IC7") (pin "8") (pinfunction "GND_8") (pintype "bidirectional"))
      (node (ref "IC7") (pin "P$1") (pinfunction "GND_P$1") (pintype "bidirectional"))
      (node (ref "IC7") (pin "P$2") (pinfunction "GND_P$2") (pintype "bidirectional"))
      (node (ref "IC7") (pin "P$3") (pinfunction "GND_P$3") (pintype "bidirectional"))
      (node (ref "IC7") (pin "P$4") (pinfunction "GND_P$4") (pintype "bidirectional"))
      (node (ref "IC7") (pin "P$5") (pinfunction "GND_P$5") (pintype "bidirectional"))
      (node (ref "IC7") (pin "P$6") (pinfunction "GND_P$6") (pintype "bidirectional"))
      (node (ref "IC8") (pin "11") (pinfunction "GND_11") (pintype "bidirectional"))
      (node (ref "IC8") (pin "8") (pinfunction "GND_8") (pintype "bidirectional"))
      (node (ref "IC8") (pin "P$1") (pinfunction "GND_P$1") (pintype "bidirectional"))
      (node (ref "IC8") (pin "P$2") (pinfunction "GND_P$2") (pintype "bidirectional"))
      (node (ref "IC8") (pin "P$3") (pinfunction "GND_P$3") (pintype "bidirectional"))
      (node (ref "IC8") (pin "P$4") (pinfunction "GND_P$4") (pintype "bidirectional"))
      (node (ref "IC8") (pin "P$5") (pinfunction "GND_P$5") (pintype "bidirectional"))
      (node (ref "IC8") (pin "P$6") (pinfunction "GND_P$6") (pintype "bidirectional"))
      (node (ref "J11") (pin "3") (pinfunction "3_3") (pintype "passive"))
      (node (ref "J15") (pin "5") (pinfunction "5_5") (pintype "bidirectional"))
      (node (ref "J16") (pin "5") (pinfunction "5_5") (pintype "bidirectional"))
      (node (ref "J17") (pin "5") (pinfunction "5_5") (pintype "bidirectional"))
      (node (ref "J18") (pin "5") (pinfunction "5_5") (pintype "bidirectional"))
      (node (ref "J19") (pin "5") (pinfunction "5_5") (pintype "bidirectional"))
      (node (ref "J20") (pin "5") (pinfunction "5_5") (pintype "bidirectional"))
      (node (ref "J21") (pin "1") (pinfunction "1_1") (pintype "passive"))
      (node (ref "J21") (pin "4") (pinfunction "4_4") (pintype "passive"))
      (node (ref "J22") (pin "4") (pinfunction "4_4") (pintype "passive"))
      (node (ref "J7") (pin "3") (pinfunction "3_3") (pintype "passive"))
      (node (ref "LDO7") (pin "2") (pinfunction "GND_2") (pintype "bidirectional"))
      (node (ref "LDO7") (pin "DGND") (pinfunction "GND_DGND") (pintype "bidirectional"))
      (node (ref "LDO7") (pin "DGND2") (pinfunction "GND_DGND2") (pintype "bidirectional"))
      (node (ref "LDO7") (pin "DGND3") (pinfunction "GND_DGND3") (pintype "bidirectional"))
      (node (ref "LDO8") (pin "2") (pinfunction "GND_2") (pintype "bidirectional"))
      (node (ref "LDO8") (pin "DGND") (pinfunction "GND_DGND") (pintype "bidirectional"))
      (node (ref "LDO8") (pin "DGND2") (pinfunction "GND_DGND2") (pintype "bidirectional"))
      (node (ref "LDO8") (pin "DGND3") (pinfunction "GND_DGND3") (pintype "bidirectional"))
      (node (ref "R1") (pin "1") (pinfunction "1_1") (pintype "passive"))
      (node (ref "R21A") (pin "2") (pinfunction "2_2") (pintype "passive"))
      (node (ref "R21A") (pin "DGND") (pinfunction "2_DGND") (pintype "passive"))
      (node (ref "R5P") (pin "1") (pinfunction "1_1") (pintype "passive"))
      (node (ref "R6A") (pin "2") (pinfunction "2_2") (pintype "passive"))
      (node (ref "R6B") (pin "2") (pinfunction "2_2") (pintype "passive"))
      (node (ref "R6C") (pin "2") (pinfunction "2_2") (pintype "passive"))
      (node (ref "R6D") (pin "2") (pinfunction "2_2") (pintype "passive"))
      (node (ref "R6E") (pin "2") (pinfunction "2_2") (pintype "passive"))
      (node (ref "R6F") (pin "2") (pinfunction "2_2") (pintype "passive"))
      (node (ref "R7A") (pin "2") (pinfunction "2_2") (pintype "passive"))
      (node (ref "R7B") (pin "2") (pinfunction "2_2") (pintype "passive"))
      (node (ref "R7C") (pin "2") (pinfunction "2_2") (pintype "passive"))
      (node (ref "R7D") (pin "2") (pinfunction "2_2") (pintype "passive"))
      (node (ref "R7E") (pin "2") (pinfunction "2_2") (pintype "passive"))
      (node (ref "R7F") (pin "2") (pinfunction "2_2") (pintype "passive"))
      (node (ref "SH3") (pin "1") (pinfunction "P$1_1") (pintype "bidirectional"))
      (node (ref "SMUTE1") (pin "2") (pinfunction "2_2") (pintype "passive"))
      (node (ref "SMUTE2") (pin "2") (pinfunction "2_2") (pintype "passive"))
      (node (ref "U$1") (pin "GND1") (pinfunction "GND1_GND1") (pintype "bidirectional"))
      (node (ref "U$1") (pin "GND2") (pinfunction "GND2_GND2") (pintype "bidirectional"))
      (node (ref "U$1") (pin "GND3") (pinfunction "GND3_GND3") (pintype "bidirectional"))
      (node (ref "U1") (pin "1") (pinfunction "ADJ/GND_1") (pintype "bidirectional"))
      (node (ref "X1") (pin "7") (pinfunction "S_7") (pintype "passive"))
      (node (ref "X4") (pin "4") (pinfunction "S_4") (pintype "passive"))
    )
    (net (code "18") (name "DIF0") (class "Default")
      (node (ref "IC2") (pin "10") (pinfunction "DIF0_10") (pintype "input"))
      (node (ref "J5") (pin "7") (pinfunction "7_7") (pintype "passive"))
      (node (ref "U$1") (pin "1-TX1") (pinfunction "1-TX1/CTX2_1-TX1") (pintype "bidirectional"))
    )
    (net (code "19") (name "DIF1") (class "Default")
      (node (ref "IC2") (pin "11") (pinfunction "DIF1_11") (pintype "input"))
      (node (ref "J5") (pin "6") (pinfunction "6_6") (pintype "passive"))
      (node (ref "U$1") (pin "2-OUT2") (pinfunction "2-OUT2_2-OUT2") (pintype "bidirectional"))
    )
    (net (code "20") (name "L+") (class "Default")
      (node (ref "R1O") (pin "1") (pinfunction "1_1") (pintype "passive"))
      (node (ref "R23O") (pin "1") (pinfunction "1_1") (pintype "passive"))
      (node (ref "R24O") (pin "1") (pinfunction "1_1") (pintype "passive"))
    )
    (net (code "21") (name "L-") (class "Default")
      (node (ref "R25O") (pin "1") (pinfunction "1_1") (pintype "passive"))
      (node (ref "R26O") (pin "1") (pinfunction "1_1") (pintype "passive"))
      (node (ref "R6O") (pin "1") (pinfunction "1_1") (pintype "passive"))
    )
    (net (code "22") (name "LRCK") (class "Default")
      (node (ref "BD1") (pin "H3.15") (pinfunction "H3.15_H3.15") (pintype "passive"))
      (node (ref "IC4A") (pin "13") (pinfunction "5D_13") (pintype "bidirectional"))
      (node (ref "IC4A") (pin "3") (pinfunction "1D_3") (pintype "bidirectional"))
      (node (ref "J21") (pin "8") (pinfunction "8_8") (pintype "passive"))
      (node (ref "J22") (pin "8") (pinfunction "8_8") (pintype "passive"))
    )
    (net (code "23") (name "L_OUT") (class "Default")
      (node (ref "C7O") (pin "1") (pinfunction "1_1") (pintype "passive"))
      (node (ref "C9O") (pin "1") (pinfunction "1_1") (pintype "passive"))
      (node (ref "J26") (pin "2") (pinfunction "TIP_2") (pintype "bidirectional"))
      (node (ref "R4O") (pin "1") (pinfunction "1_1") (pintype "passive"))
      (node (ref "R7O") (pin "1") (pinfunction "1_1") (pintype "passive"))
    )
    (net (code "24") (name "MCLK") (class "Default")
      (node (ref "BD1") (pin "H3.7") (pinfunction "H3.7_H3.7") (pintype "passive"))
      (node (ref "IC4A") (pin "11") (pinfunction "CLK_11") (pintype "bidirectional"))
      (node (ref "J22") (pin "10") (pinfunction "10_10") (pintype "passive"))
      (node (ref "R4A") (pin "1") (pinfunction "1_1") (pintype "passive"))
      (node (ref "R4B") (pin "1") (pinfunction "1_1") (pintype "passive"))
    )
    (net (code "25") (name "Net-(C1O-Pad1)") (class "Default")
      (node (ref "C1O") (pin "1") (pinfunction "1_1") (pintype "passive"))
      (node (ref "R8O") (pin "2") (pinfunction "2_2") (pintype "passive"))
      (node (ref "SX2") (pin "3") (pinfunction "3_3") (pintype "passive"))
    )
    (net (code "26") (name "Net-(C1P-+)") (class "Default")
      (node (ref "C1P") (pin "1") (pinfunction "+_1") (pintype "bidirectional"))
      (node (ref "D3") (pin "1") (pinfunction "K_1") (pintype "bidirectional"))
      (node (ref "D4") (pin "1") (pinfunction "K_1") (pintype "bidirectional"))
      (node (ref "J27") (pin "1") (pinfunction "1_1") (pintype "bidirectional"))
    )
    (net (code "27") (name "Net-(C2O-Pad1)") (class "Default")
      (node (ref "C2O") (pin "1") (pinfunction "1_1") (pintype "passive"))
      (node (ref "SX1") (pin "9") (pinfunction "9_9") (pintype "passive"))
    )
    (net (code "28") (name "Net-(C2P-+)") (class "Default")
      (node (ref "C2P") (pin "1") (pinfunction "+_1") (pintype "bidirectional"))
      (node (ref "J27") (pin "2") (pinfunction "2_2") (pintype "bidirectional"))
      (node (ref "R6P") (pin "2") (pinfunction "2_2") (pintype "passive"))
    )
    (net (code "29") (name "Net-(C4P-+)") (class "Default")
      (node (ref "C4P") (pin "1") (pinfunction "+_1") (pintype "bidirectional"))
      (node (ref "R2P") (pin "1") (pinfunction "1_1") (pintype "passive"))
      (node (ref "R3P") (pin "2") (pinfunction "2_2") (pintype "passive"))
      (node (ref "R4P") (pin "1") (pinfunction "1_1") (pintype "passive"))
      (node (ref "R5P") (pin "2") (pinfunction "2_2") (pintype "passive"))
      (node (ref "TP1") (pin "TP") (pinfunction "TP_TP") (pintype "input"))
    )
    (net (code "30") (name "Net-(C5O-Pad2)") (class "Default")
      (node (ref "C5O") (pin "2") (pinfunction "2_2") (pintype "passive"))
      (node (ref "R9O") (pin "2") (pinfunction "2_2") (pintype "passive"))
      (node (ref "SX1") (pin "8") (pinfunction "8_8") (pintype "passive"))
    )
    (net (code "31") (name "Net-(C6O-Pad1)") (class "Default")
      (node (ref "C6O") (pin "1") (pinfunction "1_1") (pintype "passive"))
      (node (ref "C7O") (pin "2") (pinfunction "2_2") (pintype "passive"))
      (node (ref "R10O") (pin "1") (pinfunction "1_1") (pintype "passive"))
      (node (ref "R2O") (pin "1") (pinfunction "1_1") (pintype "passive"))
      (node (ref "SX2") (pin "1") (pinfunction "1_1") (pintype "passive"))
    )
    (net (code "32") (name "Net-(C6O-Pad2)") (class "Default")
      (node (ref "C6O") (pin "2") (pinfunction "2_2") (pintype "passive"))
      (node (ref "R10O") (pin "2") (pinfunction "2_2") (pintype "passive"))
      (node (ref "SX2") (pin "8") (pinfunction "8_8") (pintype "passive"))
    )
    (net (code "33") (name "Net-(C9A-+)") (class "Default")
      (node (ref "C8A1") (pin "1") (pinfunction "1_1") (pintype "passive"))
      (node (ref "C9A") (pin "1") (pinfunction "+_1") (pintype "passive"))
      (node (ref "IC2") (pin "38") (pinfunction "VCML_38") (pintype "power_in"))
      (node (ref "J7") (pin "7") (pinfunction "7_7") (pintype "passive"))
    )
    (net (code "34") (name "Net-(C9B-+)") (class "Default")
      (node (ref "C8A2") (pin "1") (pinfunction "1_1") (pintype "passive"))
      (node (ref "C9B") (pin "1") (pinfunction "+_1") (pintype "passive"))
      (node (ref "IC3") (pin "38") (pinfunction "VCML_38") (pintype "power_in"))
      (node (ref "J11") (pin "7") (pinfunction "7_7") (pintype "passive"))
    )
    (net (code "35") (name "Net-(C9O-Pad2)") (class "Default")
      (node (ref "C9O") (pin "2") (pinfunction "2_2") (pintype "passive"))
      (node (ref "R4O") (pin "2") (pinfunction "2_2") (pintype "passive"))
      (node (ref "R6O") (pin "2") (pinfunction "2_2") (pintype "passive"))
      (node (ref "SX2") (pin "2") (pinfunction "2_2") (pintype "passive"))
    )
    (net (code "36") (name "Net-(C10O-Pad1)") (class "Default")
      (node (ref "C10O") (pin "1") (pinfunction "1_1") (pintype "passive"))
      (node (ref "SX2") (pin "9") (pinfunction "9_9") (pintype "passive"))
    )
    (net (code "37") (name "Net-(C11O-+)") (class "Default")
      (node (ref "C11O") (pin "1") (pinfunction "+_1") (pintype "passive"))
      (node (ref "IC3") (pin "36") (pinfunction "AOUTLP_36") (pintype "output"))
      (node (ref "J10") (pin "1") (pinfunction "1_1") (pintype "passive"))
    )
    (net (code "38") (name "Net-(C11O--)") (class "Default")
      (node (ref "C11O") (pin "2") (pinfunction "-_2") (pintype "passive"))
      (node (ref "R12O") (pin "2") (pinfunction "2_2") (pintype "passive"))
      (node (ref "R19O") (pin "2") (pinfunction "2_2") (pintype "passive"))
    )
    (net (code "39") (name "Net-(C12O-+)") (class "Default")
      (node (ref "C12O") (pin "1") (pinfunction "+_1") (pintype "passive"))
      (node (ref "IC3") (pin "25") (pinfunction "AOUTRP_25") (pintype "output"))
      (node (ref "J9") (pin "1") (pinfunction "1_1") (pintype "passive"))
    )
    (net (code "40") (name "Net-(C12O--)") (class "Default")
      (node (ref "C12O") (pin "2") (pinfunction "-_2") (pintype "passive"))
      (node (ref "R18O") (pin "2") (pinfunction "2_2") (pintype "passive"))
      (node (ref "R20O") (pin "1") (pinfunction "1_1") (pintype "passive"))
    )
    (net (code "41") (name "Net-(C13A-+)") (class "Default")
      (node (ref "C12A1") (pin "1") (pinfunction "1_1") (pintype "passive"))
      (node (ref "C13A") (pin "1") (pinfunction "+_1") (pintype "passive"))
      (node (ref "IC2") (pin "23") (pinfunction "VCMR_23") (pintype "power_in"))
      (node (ref "J5") (pin "2") (pinfunction "2_2") (pintype "passive"))
    )
    (net (code "42") (name "Net-(C13B-+)") (class "Default")
      (node (ref "C12A2") (pin "1") (pinfunction "1_1") (pintype "passive"))
      (node (ref "C13B") (pin "1") (pinfunction "+_1") (pintype "passive"))
      (node (ref "IC3") (pin "23") (pinfunction "VCMR_23") (pintype "power_in"))
      (node (ref "J9") (pin "2") (pinfunction "2_2") (pintype "passive"))
    )
    (net (code "43") (name "Net-(C13O-+)") (class "Default")
      (node (ref "C13O") (pin "1") (pinfunction "+_1") (pintype "passive"))
      (node (ref "IC3") (pin "35") (pinfunction "AOUTLN_35") (pintype "output"))
      (node (ref "J10") (pin "3") (pinfunction "3_3") (pintype "passive"))
    )
    (net (code "44") (name "Net-(C13O--)") (class "Default")
      (node (ref "C13O") (pin "2") (pinfunction "-_2") (pintype "passive"))
      (node (ref "R14O") (pin "2") (pinfunction "2_2") (pintype "passive"))
      (node (ref "R21O") (pin "2") (pinfunction "2_2") (pintype "passive"))
    )
    (net (code "45") (name "Net-(C14O-+)") (class "Default")
      (node (ref "C14O") (pin "1") (pinfunction "+_1") (pintype "passive"))
      (node (ref "IC3") (pin "26") (pinfunction "AOUTRN_26") (pintype "output"))
      (node (ref "J10") (pin "6") (pinfunction "6_6") (pintype "passive"))
    )
    (net (code "46") (name "Net-(C14O--)") (class "Default")
      (node (ref "C14O") (pin "2") (pinfunction "-_2") (pintype "passive"))
      (node (ref "R11O") (pin "1") (pinfunction "1_1") (pintype "passive"))
      (node (ref "R16O") (pin "2") (pinfunction "2_2") (pintype "passive"))
    )
    (net (code "47") (name "Net-(C15O-+)") (class "Default")
      (node (ref "C15O") (pin "1") (pinfunction "+_1") (pintype "passive"))
      (node (ref "IC2") (pin "25") (pinfunction "AOUTRP_25") (pintype "output"))
      (node (ref "J5") (pin "1") (pinfunction "1_1") (pintype "passive"))
    )
    (net (code "48") (name "Net-(C15O--)") (class "Default")
      (node (ref "C15O") (pin "2") (pinfunction "-_2") (pintype "passive"))
      (node (ref "R24O") (pin "2") (pinfunction "2_2") (pintype "passive"))
      (node (ref "R28O") (pin "2") (pinfunction "2_2") (pintype "passive"))
    )
    (net (code "49") (name "Net-(C16O-Pad1)") (class "Default")
      (node (ref "C16O") (pin "1") (pinfunction "1_1") (pintype "passive"))
      (node (ref "R5O") (pin "2") (pinfunction "2_2") (pintype "passive"))
      (node (ref "SX1") (pin "3") (pinfunction "3_3") (pintype "passive"))
    )
    (net (code "50") (name "Net-(C21O-Pad2)") (class "Default")
      (node (ref "C21O") (pin "2") (pinfunction "2_2") (pintype "passive"))
      (node (ref "C5O") (pin "1") (pinfunction "1_1") (pintype "passive"))
      (node (ref "R15O") (pin "1") (pinfunction "1_1") (pintype "passive"))
      (node (ref "R9O") (pin "1") (pinfunction "1_1") (pintype "passive"))
      (node (ref "SX1") (pin "1") (pinfunction "1_1") (pintype "passive"))
    )
    (net (code "51") (name "Net-(C23O-Pad2)") (class "Default")
      (node (ref "C23O") (pin "2") (pinfunction "2_2") (pintype "passive"))
      (node (ref "R17O") (pin "2") (pinfunction "2_2") (pintype "passive"))
      (node (ref "R27O") (pin "2") (pinfunction "2_2") (pintype "passive"))
      (node (ref "SX1") (pin "2") (pinfunction "2_2") (pintype "passive"))
    )
    (net (code "52") (name "Net-(C24O-+)") (class "Default")
      (node (ref "C24O") (pin "1") (pinfunction "+_1") (pintype "passive"))
      (node (ref "IC2") (pin "36") (pinfunction "AOUTLP_36") (pintype "output"))
      (node (ref "J6") (pin "1") (pinfunction "1_1") (pintype "passive"))
    )
    (net (code "53") (name "Net-(C24O--)") (class "Default")
      (node (ref "C24O") (pin "2") (pinfunction "-_2") (pintype "passive"))
      (node (ref "R23O") (pin "2") (pinfunction "2_2") (pintype "passive"))
      (node (ref "R29O") (pin "1") (pinfunction "1_1") (pintype "passive"))
    )
    (net (code "54") (name "Net-(C25O-+)") (class "Default")
      (node (ref "C25O") (pin "1") (pinfunction "+_1") (pintype "passive"))
      (node (ref "IC2") (pin "26") (pinfunction "AOUTRN_26") (pintype "output"))
      (node (ref "J6") (pin "6") (pinfunction "6_6") (pintype "passive"))
    )
    (net (code "55") (name "Net-(C25O--)") (class "Default")
      (node (ref "C25O") (pin "2") (pinfunction "-_2") (pintype "passive"))
      (node (ref "R25O") (pin "2") (pinfunction "2_2") (pintype "passive"))
      (node (ref "R30O") (pin "2") (pinfunction "2_2") (pintype "passive"))
    )
    (net (code "56") (name "Net-(C26O-+)") (class "Default")
      (node (ref "C26O") (pin "1") (pinfunction "+_1") (pintype "passive"))
      (node (ref "IC2") (pin "35") (pinfunction "AOUTLN_35") (pintype "output"))
      (node (ref "J6") (pin "3") (pinfunction "3_3") (pintype "passive"))
    )
    (net (code "57") (name "Net-(C26O--)") (class "Default")
      (node (ref "C26O") (pin "2") (pinfunction "-_2") (pintype "passive"))
      (node (ref "R22O") (pin "1") (pinfunction "1_1") (pintype "passive"))
      (node (ref "R26O") (pin "2") (pinfunction "2_2") (pintype "passive"))
    )
    (net (code "58") (name "Net-(D9-PadA)") (class "Default")
      (node (ref "D9") (pin "A") (pinfunction "A_A") (pintype "passive"))
      (node (ref "U$1") (pin "VUSB") (pinfunction "VUSB_VUSB") (pintype "bidirectional"))
    )
    (net (code "59") (name "Net-(IC1-ILIM)") (class "Default")
      (node (ref "IC1") (pin "5") (pinfunction "ILIM_5") (pintype "bidirectional"))
      (node (ref "J15") (pin "2") (pinfunction "2_2") (pintype "bidirectional"))
      (node (ref "R6A") (pin "1") (pinfunction "1_1") (pintype "passive"))
    )
    (net (code "60") (name "Net-(IC1-PG)") (class "Default")
      (node (ref "IC1") (pin "4") (pinfunction "PG_4") (pintype "bidirectional"))
      (node (ref "J15") (pin "1") (pinfunction "1_1") (pintype "bidirectional"))
      (node (ref "R8A") (pin "2") (pinfunction "2_2") (pintype "passive"))
    )
    (net (code "61") (name "Net-(IC1-PGFB)") (class "Default")
      (node (ref "IC1") (pin "6") (pinfunction "PGFB_6") (pintype "bidirectional"))
      (node (ref "J15") (pin "3") (pinfunction "3_3") (pintype "bidirectional"))
    )
    (net (code "62") (name "Net-(IC1-SET)") (class "Default")
      (node (ref "C19A") (pin "1") (pinfunction "1_1") (pintype "passive"))
      (node (ref "IC1") (pin "7") (pinfunction "SET_7") (pintype "bidirectional"))
      (node (ref "J15") (pin "4") (pinfunction "4_4") (pintype "bidirectional"))
      (node (ref "R7A") (pin "1") (pinfunction "1_1") (pintype "passive"))
    )
    (net (code "63") (name "Net-(IC2-BICK)") (class "Default")
      (node (ref "IC2") (pin "3") (pinfunction "BICK_3") (pintype "input"))
      (node (ref "J8") (pin "5") (pinfunction "5_5") (pintype "passive"))
      (node (ref "R1A") (pin "2") (pinfunction "2_2") (pintype "passive"))
    )
    (net (code "64") (name "Net-(IC2-DIF2)") (class "Default")
      (node (ref "DIF1") (pin "2") (pinfunction "2_2") (pintype "passive"))
      (node (ref "IC2") (pin "12") (pinfunction "DIF2_12") (pintype "input"))
    )
    (net (code "65") (name "Net-(IC2-DVDD)") (class "Default")
      (node (ref "C27A") (pin "1") (pinfunction "1_1") (pintype "passive"))
      (node (ref "C28A") (pin "1") (pinfunction "1_1") (pintype "passive"))
      (node (ref "IC2") (pin "1") (pinfunction "DVDD_1") (pintype "power_in"))
      (node (ref "J8") (pin "7") (pinfunction "7_7") (pintype "passive"))
      (node (ref "LDO7") (pin "5") (pinfunction "VOUT_5") (pintype "bidirectional"))
    )
    (net (code "66") (name "Net-(IC2-LRCK)") (class "Default")
      (node (ref "IC2") (pin "5") (pinfunction "LRCK_5") (pintype "input"))
      (node (ref "J8") (pin "3") (pinfunction "3_3") (pintype "passive"))
      (node (ref "R3A") (pin "2") (pinfunction "2_2") (pintype "passive"))
    )
    (net (code "67") (name "Net-(IC2-MCLK)") (class "Default")
      (node (ref "IC2") (pin "46") (pinfunction "MCLK_46") (pintype "input"))
      (node (ref "J7") (pin "4") (pinfunction "4_4") (pintype "passive"))
      (node (ref "R4A") (pin "2") (pinfunction "2_2") (pintype "passive"))
    )
    (net (code "68") (name "Net-(IC2-SDATA)") (class "Default")
      (node (ref "IC2") (pin "4") (pinfunction "SDATA_4") (pintype "input"))
      (node (ref "J8") (pin "4") (pinfunction "4_4") (pintype "passive"))
      (node (ref "R2A") (pin "2") (pinfunction "2_2") (pintype "passive"))
    )
    (net (code "69") (name "Net-(IC2-SMUTE)") (class "Default")
      (node (ref "IC2") (pin "7") (pinfunction "SMUTE_7") (pintype "input"))
      (node (ref "SMUTE1") (pin "1") (pinfunction "1_1") (pintype "passive"))
    )
    (net (code "70") (name "Net-(IC3-BICK)") (class "Default")
      (node (ref "IC3") (pin "3") (pinfunction "BICK_3") (pintype "input"))
      (node (ref "J12") (pin "5") (pinfunction "5_5") (pintype "passive"))
      (node (ref "R1B") (pin "2") (pinfunction "2_2") (pintype "passive"))
    )
    (net (code "71") (name "Net-(IC3-DIF0)") (class "Default")
      (node (ref "IC3") (pin "10") (pinfunction "DIF0_10") (pintype "input"))
      (node (ref "J9") (pin "7") (pinfunction "7_7") (pintype "passive"))
    )
    (net (code "72") (name "Net-(IC3-DIF1)") (class "Default")
      (node (ref "IC3") (pin "11") (pinfunction "DIF1_11") (pintype "input"))
      (node (ref "J9") (pin "6") (pinfunction "6_6") (pintype "passive"))
    )
    (net (code "73") (name "Net-(IC3-DIF2)") (class "Default")
      (node (ref "DIF3") (pin "2") (pinfunction "2_2") (pintype "passive"))
      (node (ref "IC3") (pin "12") (pinfunction "DIF2_12") (pintype "input"))
    )
    (net (code "74") (name "Net-(IC3-DVDD)") (class "Default")
      (node (ref "C27B") (pin "1") (pinfunction "1_1") (pintype "passive"))
      (node (ref "C28B") (pin "1") (pinfunction "1_1") (pintype "passive"))
      (node (ref "IC3") (pin "1") (pinfunction "DVDD_1") (pintype "power_in"))
      (node (ref "J12") (pin "7") (pinfunction "7_7") (pintype "passive"))
      (node (ref "LDO8") (pin "5") (pinfunction "VOUT_5") (pintype "bidirectional"))
    )
    (net (code "75") (name "Net-(IC3-LRCK)") (class "Default")
      (node (ref "IC3") (pin "5") (pinfunction "LRCK_5") (pintype "input"))
      (node (ref "J12") (pin "3") (pinfunction "3_3") (pintype "passive"))
      (node (ref "R3B") (pin "2") (pinfunction "2_2") (pintype "passive"))
    )
    (net (code "76") (name "Net-(IC3-MCLK)") (class "Default")
      (node (ref "IC3") (pin "46") (pinfunction "MCLK_46") (pintype "input"))
      (node (ref "J11") (pin "4") (pinfunction "4_4") (pintype "passive"))
      (node (ref "R4B") (pin "2") (pinfunction "2_2") (pintype "passive"))
    )
    (net (code "77") (name "Net-(IC3-SDATA)") (class "Default")
      (node (ref "IC3") (pin "4") (pinfunction "SDATA_4") (pintype "input"))
      (node (ref "J12") (pin "4") (pinfunction "4_4") (pintype "passive"))
      (node (ref "R2B") (pin "2") (pinfunction "2_2") (pintype "passive"))
    )
    (net (code "78") (name "Net-(IC3-SMUTE)") (class "Default")
      (node (ref "IC3") (pin "7") (pinfunction "SMUTE_7") (pintype "input"))
      (node (ref "SMUTE2") (pin "1") (pinfunction "1_1") (pintype "passive"))
    )
    (net (code "79") (name "Net-(IC4-ILIM)") (class "Default")
      (node (ref "IC4") (pin "5") (pinfunction "ILIM_5") (pintype "bidirectional"))
      (node (ref "J16") (pin "2") (pinfunction "2_2") (pintype "bidirectional"))
      (node (ref "R6C") (pin "1") (pinfunction "1_1") (pintype "passive"))
    )
    (net (code "80") (name "Net-(IC4-PG)") (class "Default")
      (node (ref "IC4") (pin "4") (pinfunction "PG_4") (pintype "bidirectional"))
      (node (ref "J16") (pin "1") (pinfunction "1_1") (pintype "bidirectional"))
      (node (ref "R8C") (pin "2") (pinfunction "2_2") (pintype "passive"))
    )
    (net (code "81") (name "Net-(IC4-PGFB)") (class "Default")
      (node (ref "IC4") (pin "6") (pinfunction "PGFB_6") (pintype "bidirectional"))
      (node (ref "J16") (pin "3") (pinfunction "3_3") (pintype "bidirectional"))
    )
    (net (code "82") (name "Net-(IC4-SET)") (class "Default")
      (node (ref "C19C") (pin "1") (pinfunction "1_1") (pintype "passive"))
      (node (ref "IC4") (pin "7") (pinfunction "SET_7") (pintype "bidirectional"))
      (node (ref "J16") (pin "4") (pinfunction "4_4") (pintype "bidirectional"))
      (node (ref "R7C") (pin "1") (pinfunction "1_1") (pintype "passive"))
    )
    (net (code "83") (name "Net-(IC4A-1Q)") (class "Default")
      (node (ref "IC4A") (pin "2") (pinfunction "1Q_2") (pintype "bidirectional"))
      (node (ref "J21") (pin "9") (pinfunction "9_9") (pintype "passive"))
      (node (ref "R3B") (pin "1") (pinfunction "1_1") (pintype "passive"))
    )
    (net (code "84") (name "Net-(IC4A-2Q)") (class "Default")
      (node (ref "IC4A") (pin "5") (pinfunction "2Q_5") (pintype "bidirectional"))
      (node (ref "J21") (pin "6") (pinfunction "6_6") (pintype "passive"))
      (node (ref "R2B") (pin "1") (pinfunction "1_1") (pintype "passive"))
    )
    (net (code "85") (name "Net-(IC4A-3Q)") (class "Default")
      (node (ref "IC4A") (pin "6") (pinfunction "3Q_6") (pintype "bidirectional"))
      (node (ref "J21") (pin "5") (pinfunction "5_5") (pintype "passive"))
    )
    (net (code "86") (name "Net-(IC4A-4Q)") (class "Default")
      (node (ref "IC4A") (pin "9") (pinfunction "4Q_9") (pintype "bidirectional"))
      (node (ref "J21") (pin "2") (pinfunction "2_2") (pintype "passive"))
      (node (ref "R1B") (pin "1") (pinfunction "1_1") (pintype "passive"))
    )
    (net (code "87") (name "Net-(IC4A-5Q)") (class "Default")
      (node (ref "IC4A") (pin "12") (pinfunction "5Q_12") (pintype "bidirectional"))
      (node (ref "J22") (pin "9") (pinfunction "9_9") (pintype "passive"))
      (node (ref "R3A") (pin "1") (pinfunction "1_1") (pintype "passive"))
    )
    (net (code "88") (name "Net-(IC4A-6Q)") (class "Default")
      (node (ref "IC4A") (pin "15") (pinfunction "6Q_15") (pintype "bidirectional"))
      (node (ref "J22") (pin "6") (pinfunction "6_6") (pintype "passive"))
      (node (ref "R2A") (pin "1") (pinfunction "1_1") (pintype "passive"))
    )
    (net (code "89") (name "Net-(IC4A-7Q)") (class "Default")
      (node (ref "IC4A") (pin "16") (pinfunction "7Q_16") (pintype "bidirectional"))
      (node (ref "J22") (pin "5") (pinfunction "5_5") (pintype "passive"))
    )
    (net (code "90") (name "Net-(IC4A-8Q)") (class "Default")
      (node (ref "IC4A") (pin "19") (pinfunction "8Q_19") (pintype "bidirectional"))
      (node (ref "J22") (pin "2") (pinfunction "2_2") (pintype "passive"))
      (node (ref "R1A") (pin "1") (pinfunction "1_1") (pintype "passive"))
    )
    (net (code "91") (name "Net-(IC4A-~{CLR})") (class "Default")
      (node (ref "IC4A") (pin "1") (pinfunction "~{CLR}_1") (pintype "bidirectional"))
      (node (ref "J21") (pin "10") (pinfunction "10_10") (pintype "passive"))
      (node (ref "R21A") (pin "1") (pinfunction "1_1") (pintype "passive"))
    )
    (net (code "92") (name "Net-(IC5-ILIM)") (class "Default")
      (node (ref "IC5") (pin "5") (pinfunction "ILIM_5") (pintype "bidirectional"))
      (node (ref "J17") (pin "2") (pinfunction "2_2") (pintype "bidirectional"))
      (node (ref "R6B") (pin "1") (pinfunction "1_1") (pintype "passive"))
    )
    (net (code "93") (name "Net-(IC5-PG)") (class "Default")
      (node (ref "IC5") (pin "4") (pinfunction "PG_4") (pintype "bidirectional"))
      (node (ref "J17") (pin "1") (pinfunction "1_1") (pintype "bidirectional"))
      (node (ref "R8B") (pin "2") (pinfunction "2_2") (pintype "passive"))
    )
    (net (code "94") (name "Net-(IC5-PGFB)") (class "Default")
      (node (ref "IC5") (pin "6") (pinfunction "PGFB_6") (pintype "bidirectional"))
      (node (ref "J17") (pin "3") (pinfunction "3_3") (pintype "bidirectional"))
    )
    (net (code "95") (name "Net-(IC5-SET)") (class "Default")
      (node (ref "C19B") (pin "1") (pinfunction "1_1") (pintype "passive"))
      (node (ref "IC5") (pin "7") (pinfunction "SET_7") (pintype "bidirectional"))
      (node (ref "J17") (pin "4") (pinfunction "4_4") (pintype "bidirectional"))
      (node (ref "R7B") (pin "1") (pinfunction "1_1") (pintype "passive"))
    )
    (net (code "96") (name "Net-(IC6-ILIM)") (class "Default")
      (node (ref "IC6") (pin "5") (pinfunction "ILIM_5") (pintype "bidirectional"))
      (node (ref "J18") (pin "2") (pinfunction "2_2") (pintype "bidirectional"))
      (node (ref "R6D") (pin "1") (pinfunction "1_1") (pintype "passive"))
    )
    (net (code "97") (name "Net-(IC6-PG)") (class "Default")
      (node (ref "IC6") (pin "4") (pinfunction "PG_4") (pintype "bidirectional"))
      (node (ref "J18") (pin "1") (pinfunction "1_1") (pintype "bidirectional"))
      (node (ref "R8D") (pin "2") (pinfunction "2_2") (pintype "passive"))
    )
    (net (code "98") (name "Net-(IC6-PGFB)") (class "Default")
      (node (ref "IC6") (pin "6") (pinfunction "PGFB_6") (pintype "bidirectional"))
      (node (ref "J18") (pin "3") (pinfunction "3_3") (pintype "bidirectional"))
    )
    (net (code "99") (name "Net-(IC6-SET)") (class "Default")
      (node (ref "C19D") (pin "1") (pinfunction "1_1") (pintype "passive"))
      (node (ref "IC6") (pin "7") (pinfunction "SET_7") (pintype "bidirectional"))
      (node (ref "J18") (pin "4") (pinfunction "4_4") (pintype "bidirectional"))
      (node (ref "R7D") (pin "1") (pinfunction "1_1") (pintype "passive"))
    )
    (net (code "100") (name "Net-(IC7-ILIM)") (class "Default")
      (node (ref "IC7") (pin "5") (pinfunction "ILIM_5") (pintype "bidirectional"))
      (node (ref "J19") (pin "2") (pinfunction "2_2") (pintype "bidirectional"))
      (node (ref "R6F") (pin "1") (pinfunction "1_1") (pintype "passive"))
    )
    (net (code "101") (name "Net-(IC7-PG)") (class "Default")
      (node (ref "IC7") (pin "4") (pinfunction "PG_4") (pintype "bidirectional"))
      (node (ref "J19") (pin "1") (pinfunction "1_1") (pintype "bidirectional"))
      (node (ref "R8F") (pin "2") (pinfunction "2_2") (pintype "passive"))
    )
    (net (code "102") (name "Net-(IC7-PGFB)") (class "Default")
      (node (ref "IC7") (pin "6") (pinfunction "PGFB_6") (pintype "bidirectional"))
      (node (ref "J19") (pin "3") (pinfunction "3_3") (pintype "bidirectional"))
    )
    (net (code "103") (name "Net-(IC7-SET)") (class "Default")
      (node (ref "C19F") (pin "1") (pinfunction "1_1") (pintype "passive"))
      (node (ref "IC7") (pin "7") (pinfunction "SET_7") (pintype "bidirectional"))
      (node (ref "J19") (pin "4") (pinfunction "4_4") (pintype "bidirectional"))
      (node (ref "R7F") (pin "1") (pinfunction "1_1") (pintype "passive"))
    )
    (net (code "104") (name "Net-(IC8-ILIM)") (class "Default")
      (node (ref "IC8") (pin "5") (pinfunction "ILIM_5") (pintype "bidirectional"))
      (node (ref "J20") (pin "2") (pinfunction "2_2") (pintype "bidirectional"))
      (node (ref "R6E") (pin "1") (pinfunction "1_1") (pintype "passive"))
    )
    (net (code "105") (name "Net-(IC8-PG)") (class "Default")
      (node (ref "IC8") (pin "4") (pinfunction "PG_4") (pintype "bidirectional"))
      (node (ref "J20") (pin "1") (pinfunction "1_1") (pintype "bidirectional"))
      (node (ref "R8E") (pin "2") (pinfunction "2_2") (pintype "passive"))
    )
    (net (code "106") (name "Net-(IC8-PGFB)") (class "Default")
      (node (ref "IC8") (pin "6") (pinfunction "PGFB_6") (pintype "bidirectional"))
      (node (ref "J20") (pin "3") (pinfunction "3_3") (pintype "bidirectional"))
    )
    (net (code "107") (name "Net-(IC8-SET)") (class "Default")
      (node (ref "C19E") (pin "1") (pinfunction "1_1") (pintype "passive"))
      (node (ref "IC8") (pin "7") (pinfunction "SET_7") (pintype "bidirectional"))
      (node (ref "J20") (pin "4") (pinfunction "4_4") (pintype "bidirectional"))
      (node (ref "R7E") (pin "1") (pinfunction "1_1") (pintype "passive"))
    )
    (net (code "108") (name "Net-(R1O-Pad2)") (class "Default")
      (node (ref "R1O") (pin "2") (pinfunction "2_2") (pintype "passive"))
      (node (ref "R2O") (pin "2") (pinfunction "2_2") (pintype "passive"))
      (node (ref "SX2") (pin "7") (pinfunction "7_7") (pintype "passive"))
    )
    (net (code "109") (name "Net-(R13O-Pad2)") (class "Default")
      (node (ref "R13O") (pin "2") (pinfunction "2_2") (pintype "passive"))
      (node (ref "R15O") (pin "2") (pinfunction "2_2") (pintype "passive"))
      (node (ref "SX1") (pin "7") (pinfunction "7_7") (pintype "passive"))
    )
    (net (code "110") (name "Net-(U1-OUTPUT)") (class "Default")
      (node (ref "D9") (pin "C") (pinfunction "C_C") (pintype "passive"))
      (node (ref "U$1") (pin "VIN") (pinfunction "VIN_VIN") (pintype "bidirectional"))
      (node (ref "U1") (pin "2") (pinfunction "OUTPUT_2") (pintype "bidirectional"))
      (node (ref "U1") (pin "4") (pinfunction "VOUT_4") (pintype "bidirectional"))
      (node (ref "X4") (pin "3") (pinfunction "S_3") (pintype "passive"))
    )
    (net (code "111") (name "PDN") (class "Default")
      (node (ref "C1A") (pin "1") (pinfunction "1_1") (pintype "passive"))
      (node (ref "IC2") (pin "2") (pinfunction "PDN_2") (pintype "input"))
      (node (ref "IC3") (pin "2") (pinfunction "PDN_2") (pintype "input"))
      (node (ref "J12") (pin "6") (pinfunction "6_6") (pintype "passive"))
      (node (ref "J8") (pin "6") (pinfunction "6_6") (pintype "passive"))
      (node (ref "R5A") (pin "1") (pinfunction "1_1") (pintype "passive"))
      (node (ref "U$1") (pin "0-RX1") (pinfunction "0-RX1/CRX2_0-RX1") (pintype "bidirectional"))
    )
    (net (code "112") (name "PE") (class "Default")
      (node (ref "IN") (pin "7") (pinfunction "7_7") (pintype "bidirectional"))
    )
    (net (code "113") (name "R+") (class "Default")
      (node (ref "R12O") (pin "1") (pinfunction "1_1") (pintype "passive"))
      (node (ref "R13O") (pin "1") (pinfunction "1_1") (pintype "passive"))
      (node (ref "R18O") (pin "1") (pinfunction "1_1") (pintype "passive"))
    )
    (net (code "114") (name "R-") (class "Default")
      (node (ref "R14O") (pin "1") (pinfunction "1_1") (pintype "passive"))
      (node (ref "R16O") (pin "1") (pinfunction "1_1") (pintype "passive"))
      (node (ref "R27O") (pin "1") (pinfunction "1_1") (pintype "passive"))
    )
    (net (code "115") (name "ROT_A") (class "Default")
      (node (ref "C6") (pin "1") (pinfunction "1_1") (pintype "passive"))
      (node (ref "U$1") (pin "3-LRCLK2") (pinfunction "3-LRCLK2_3-LRCLK2") (pintype "bidirectional"))
      (node (ref "X1") (pin "1") (pinfunction "S_1") (pintype "passive"))
    )
    (net (code "116") (name "ROT_B") (class "Default")
      (node (ref "C7") (pin "2") (pinfunction "2_2") (pintype "passive"))
      (node (ref "U$1") (pin "5-IN2") (pinfunction "5-IN2_5-IN2") (pintype "bidirectional"))
      (node (ref "X1") (pin "3") (pinfunction "S_3") (pintype "passive"))
    )
    (net (code "117") (name "ROT_LEDB") (class "Default")
      (node (ref "U$1") (pin "23-A9/CRX1/CCLK1") (pinfunction "23-A9/CRX1/MCLK1_23-A9/CRX1/CCLK1") (pintype "bidirectional"))
      (node (ref "X1") (pin "4") (pinfunction "S_4") (pintype "passive"))
    )
    (net (code "118") (name "ROT_LEDG") (class "Default")
      (node (ref "U$1") (pin "22-A8/CTX1") (pinfunction "22-A8/CTX1_22-A8/CTX1") (pintype "bidirectional"))
      (node (ref "X1") (pin "5") (pinfunction "S_5") (pintype "passive"))
    )
    (net (code "119") (name "ROT_LEDR") (class "Default")
      (node (ref "U$1") (pin "19-A5/SCL0") (pinfunction "19-A5/SCL0_19-A5/SCL0") (pintype "bidirectional"))
      (node (ref "X1") (pin "6") (pinfunction "S_6") (pintype "passive"))
    )
    (net (code "120") (name "ROT_SW") (class "Default")
      (node (ref "R1") (pin "2") (pinfunction "2_2") (pintype "passive"))
      (node (ref "U$1") (pin "4-BCLK2") (pinfunction "4-BCLK1_4-BCLK2") (pintype "bidirectional"))
      (node (ref "X1") (pin "2") (pinfunction "S_2") (pintype "passive"))
    )
    (net (code "121") (name "R_OUT") (class "Default")
      (node (ref "C21O") (pin "1") (pinfunction "1_1") (pintype "passive"))
      (node (ref "C23O") (pin "1") (pinfunction "1_1") (pintype "passive"))
      (node (ref "J26") (pin "3") (pinfunction "RING_3") (pintype "bidirectional"))
      (node (ref "R17O") (pin "1") (pinfunction "1_1") (pintype "passive"))
      (node (ref "R3O") (pin "1") (pinfunction "1_1") (pintype "passive"))
    )
    (net (code "122") (name "SCL0") (class "Default")
      (node (ref "IC2") (pin "8") (pinfunction "SD_8") (pintype "input"))
      (node (ref "IC3") (pin "8") (pinfunction "SD_8") (pintype "input"))
      (node (ref "J12") (pin "2") (pinfunction "2_2") (pintype "passive"))
      (node (ref "J8") (pin "2") (pinfunction "2_2") (pintype "passive"))
      (node (ref "R10") (pin "2") (pinfunction "2_2") (pintype "passive"))
      (node (ref "U$1") (pin "16-A2/RX4/SCL1") (pinfunction "16-A2/RX4/SCL1_16-A2/RX4/SCL1") (pintype "bidirectional"))
      (node (ref "X4") (pin "1") (pinfunction "S_1") (pintype "passive"))
    )
    (net (code "123") (name "SDA0") (class "Default")
      (node (ref "IC2") (pin "9") (pinfunction "SLOW_9") (pintype "input"))
      (node (ref "IC3") (pin "9") (pinfunction "SLOW_9") (pintype "input"))
      (node (ref "J12") (pin "1") (pinfunction "1_1") (pintype "passive"))
      (node (ref "J8") (pin "1") (pinfunction "1_1") (pintype "passive"))
      (node (ref "R20") (pin "2") (pinfunction "2_2") (pintype "passive"))
      (node (ref "U$1") (pin "17-A3/TX4/SDA1") (pinfunction "17-A3/TX4/SDA1_17-A3/TX4/SDA1") (pintype "bidirectional"))
      (node (ref "X4") (pin "2") (pinfunction "S_2") (pintype "passive"))
    )
    (net (code "124") (name "VCC") (class "Default")
      (node (ref "R4P") (pin "2") (pinfunction "2_2") (pintype "passive"))
    )
    (net (code "125") (name "VCC{slash}1") (class "Default")
      (node (ref "C1P1") (pin "1") (pinfunction "+_1") (pintype "bidirectional"))
      (node (ref "C2") (pin "1") (pinfunction "1_1") (pintype "passive"))
      (node (ref "C20A") (pin "1") (pinfunction "1_1") (pintype "passive"))
      (node (ref "C20B") (pin "1") (pinfunction "1_1") (pintype "passive"))
      (node (ref "C20C") (pin "1") (pinfunction "1_1") (pintype "passive"))
      (node (ref "C20D") (pin "1") (pinfunction "1_1") (pintype "passive"))
      (node (ref "C20E") (pin "1") (pinfunction "1_1") (pintype "passive"))
      (node (ref "C20F") (pin "1") (pinfunction "1_1") (pintype "passive"))
      (node (ref "C21A") (pin "1") (pinfunction "1_1") (pintype "passive"))
      (node (ref "C21B") (pin "1") (pinfunction "1_1") (pintype "passive"))
      (node (ref "C21C") (pin "1") (pinfunction "1_1") (pintype "passive"))
      (node (ref "C21D") (pin "1") (pinfunction "1_1") (pintype "passive"))
      (node (ref "C21E") (pin "1") (pinfunction "1_1") (pintype "passive"))
      (node (ref "C21F") (pin "1") (pinfunction "1_1") (pintype "passive"))
      (node (ref "C2P1") (pin "1") (pinfunction "+_1") (pintype "bidirectional"))
      (node (ref "C3P1") (pin "1") (pinfunction "+_1") (pintype "bidirectional"))
      (node (ref "C4") (pin "1") (pinfunction "1_1") (pintype "passive"))
      (node (ref "C5P1") (pin "1") (pinfunction "+_1") (pintype "bidirectional"))
      (node (ref "C6P1") (pin "1") (pinfunction "+_1") (pintype "bidirectional"))
      (node (ref "C7P1") (pin "1") (pinfunction "+_1") (pintype "bidirectional"))
      (node (ref "D7") (pin "1") (pinfunction "K_1") (pintype "bidirectional"))
      (node (ref "D8") (pin "1") (pinfunction "K_1") (pintype "bidirectional"))
      (node (ref "IC1") (pin "1") (pinfunction "IN_1") (pintype "bidirectional"))
      (node (ref "IC1") (pin "2") (pinfunction "IN_2") (pintype "bidirectional"))
      (node (ref "IC1") (pin "3") (pinfunction "EN/UV_3") (pintype "bidirectional"))
      (node (ref "IC4") (pin "1") (pinfunction "IN_1") (pintype "bidirectional"))
      (node (ref "IC4") (pin "2") (pinfunction "IN_2") (pintype "bidirectional"))
      (node (ref "IC4") (pin "3") (pinfunction "EN/UV_3") (pintype "bidirectional"))
      (node (ref "IC5") (pin "1") (pinfunction "IN_1") (pintype "bidirectional"))
      (node (ref "IC5") (pin "2") (pinfunction "IN_2") (pintype "bidirectional"))
      (node (ref "IC5") (pin "3") (pinfunction "EN/UV_3") (pintype "bidirectional"))
      (node (ref "IC6") (pin "1") (pinfunction "IN_1") (pintype "bidirectional"))
      (node (ref "IC6") (pin "2") (pinfunction "IN_2") (pintype "bidirectional"))
      (node (ref "IC6") (pin "3") (pinfunction "EN/UV_3") (pintype "bidirectional"))
      (node (ref "IC7") (pin "1") (pinfunction "IN_1") (pintype "bidirectional"))
      (node (ref "IC7") (pin "2") (pinfunction "IN_2") (pintype "bidirectional"))
      (node (ref "IC7") (pin "3") (pinfunction "EN/UV_3") (pintype "bidirectional"))
      (node (ref "IC8") (pin "1") (pinfunction "IN_1") (pintype "bidirectional"))
      (node (ref "IC8") (pin "2") (pinfunction "IN_2") (pintype "bidirectional"))
      (node (ref "IC8") (pin "3") (pinfunction "EN/UV_3") (pintype "bidirectional"))
      (node (ref "J15") (pin "7") (pinfunction "7_7") (pintype "bidirectional"))
      (node (ref "J15") (pin "8") (pinfunction "8_8") (pintype "bidirectional"))
      (node (ref "J16") (pin "7") (pinfunction "7_7") (pintype "bidirectional"))
      (node (ref "J16") (pin "8") (pinfunction "8_8") (pintype "bidirectional"))
      (node (ref "J17") (pin "7") (pinfunction "7_7") (pintype "bidirectional"))
      (node (ref "J17") (pin "8") (pinfunction "8_8") (pintype "bidirectional"))
      (node (ref "J18") (pin "7") (pinfunction "7_7") (pintype "bidirectional"))
      (node (ref "J18") (pin "8") (pinfunction "8_8") (pintype "bidirectional"))
      (node (ref "J19") (pin "7") (pinfunction "7_7") (pintype "bidirectional"))
      (node (ref "J19") (pin "8") (pinfunction "8_8") (pintype "bidirectional"))
      (node (ref "J20") (pin "7") (pinfunction "7_7") (pintype "bidirectional"))
      (node (ref "J20") (pin "8") (pinfunction "8_8") (pintype "bidirectional"))
      (node (ref "R8A") (pin "1") (pinfunction "1_1") (pintype "passive"))
      (node (ref "R8B") (pin "1") (pinfunction "1_1") (pintype "passive"))
      (node (ref "R8C") (pin "1") (pinfunction "1_1") (pintype "passive"))
      (node (ref "R8D") (pin "1") (pinfunction "1_1") (pintype "passive"))
      (node (ref "R8E") (pin "1") (pinfunction "1_1") (pintype "passive"))
      (node (ref "R8F") (pin "1") (pinfunction "1_1") (pintype "passive"))
      (node (ref "U1") (pin "3") (pinfunction "INPUT_3") (pintype "bidirectional"))
    )
    (net (code "126") (name "unconnected-(BD1-PadH3.9)") (class "Default")
      (node (ref "BD1") (pin "H3.9") (pinfunction "H3.9_H3.9") (pintype "passive"))
    )
    (net (code "127") (name "unconnected-(BD1-PadH3.18)") (class "Default")
      (node (ref "BD1") (pin "H3.18") (pinfunction "H3.18_H3.18") (pintype "passive"))
    )
    (net (code "128") (name "unconnected-(BD1-PadH3.20)") (class "Default")
      (node (ref "BD1") (pin "H3.20") (pinfunction "H3.20_H3.20") (pintype "passive"))
    )
    (net (code "129") (name "unconnected-(IC2-NC-Pad24)") (class "Default")
      (node (ref "IC2") (pin "24") (pinfunction "NC_24") (pintype "no_connect"))
    )
    (net (code "130") (name "unconnected-(IC2-NC1-Pad37)") (class "Default")
      (node (ref "IC2") (pin "37") (pinfunction "NC1_37") (pintype "no_connect"))
    )
    (net (code "131") (name "unconnected-(IC2-NC2-Pad43)") (class "Default")
      (node (ref "IC2") (pin "43") (pinfunction "NC2_43") (pintype "no_connect"))
    )
    (net (code "132") (name "unconnected-(IC2-TESTE-Pad18)") (class "Default")
      (node (ref "IC2") (pin "18") (pinfunction "TESTE_18") (pintype "input"))
    )
    (net (code "133") (name "unconnected-(IC3-NC-Pad24)") (class "Default")
      (node (ref "IC3") (pin "24") (pinfunction "NC_24") (pintype "no_connect"))
    )
    (net (code "134") (name "unconnected-(IC3-NC1-Pad37)") (class "Default")
      (node (ref "IC3") (pin "37") (pinfunction "NC1_37") (pintype "no_connect"))
    )
    (net (code "135") (name "unconnected-(IC3-NC2-Pad43)") (class "Default")
      (node (ref "IC3") (pin "43") (pinfunction "NC2_43") (pintype "no_connect"))
    )
    (net (code "136") (name "unconnected-(IC3-TESTE-Pad18)") (class "Default")
      (node (ref "IC3") (pin "18") (pinfunction "TESTE_18") (pintype "input"))
    )
    (net (code "137") (name "unconnected-(J7-Pad1)") (class "Default")
      (node (ref "J7") (pin "1") (pinfunction "1_1") (pintype "passive"))
    )
    (net (code "138") (name "unconnected-(J11-Pad1)") (class "Default")
      (node (ref "J11") (pin "1") (pinfunction "1_1") (pintype "passive"))
    )
    (net (code "139") (name "unconnected-(LDO7-NC-Pad4)") (class "Default")
      (node (ref "LDO7") (pin "4") (pinfunction "NC_4") (pintype "no_connect"))
    )
    (net (code "140") (name "unconnected-(LDO8-NC-Pad4)") (class "Default")
      (node (ref "LDO8") (pin "4") (pinfunction "NC_4") (pintype "no_connect"))
    )
    (net (code "141") (name "unconnected-(U$1-7-OUT1A{slash}RX2-Pad7-RX2{slash}OUT1A)") (class "Default")
      (node (ref "U$1") (pin "7-RX2/OUT1A") (pinfunction "7-OUT1A/RX2_7-RX2/OUT1A") (pintype "bidirectional"))
    )
    (net (code "142") (name "unconnected-(U$1-8-IN1{slash}TX2-Pad8-TX2{slash}IN1)") (class "Default")
      (node (ref "U$1") (pin "8-TX2/IN1") (pinfunction "8-IN1/TX2_8-TX2/IN1") (pintype "bidirectional"))
    )
    (net (code "143") (name "unconnected-(U$1-10-CS-Pad10-CS{slash}MQSR)") (class "Default")
      (node (ref "U$1") (pin "10-CS/MQSR") (pinfunction "10-CS_10-CS/MQSR") (pintype "bidirectional"))
    )
    (net (code "144") (name "unconnected-(U$1-12-MISO{slash}MQSL-Pad12-MIO{slash}MQSL)") (class "Default")
      (node (ref "U$1") (pin "12-MIO/MQSL") (pinfunction "12-MISO/MQSL_12-MIO/MQSL") (pintype "bidirectional"))
    )
    (net (code "145") (name "unconnected-(U$1-14-A0{slash}TX3{slash}S-PDIF_IN-Pad14-A0{slash}TX3{slash}S-PFI_OUT)") (class "Default")
      (node (ref "U$1") (pin "14-A0/TX3/S-PFI_OUT") (pinfunction "14-A0/TX3/S-PDIF_IN_14-A0/TX3/S-PFI_OUT") (pintype "bidirectional"))
    )
    (net (code "146") (name "unconnected-(U$1-15-A1{slash}RX3{slash}SPDIF_IN-Pad15-A1{slash}RX3{slash}S-PDIF_IN)") (class "Default")
      (node (ref "U$1") (pin "15-A1/RX3/S-PDIF_IN") (pinfunction "15-A1/RX3/SPDIF_IN_15-A1/RX3/S-PDIF_IN") (pintype "bidirectional"))
    )
    (net (code "147") (name "unconnected-(U$1-25-A11{slash}RX6{slash}SDA2-Pad25-A11{slash}SDA2)") (class "Default")
      (node (ref "U$1") (pin "25-A11/SDA2") (pinfunction "25-A11/RX6/SDA2_25-A11/SDA2") (pintype "bidirectional"))
    )
    (net (code "148") (name "unconnected-(U$1-32-OUT1B-Pad32-OUTB1)") (class "Default")
      (node (ref "U$1") (pin "32-OUTB1") (pinfunction "32-OUT1B_32-OUTB1") (pintype "bidirectional"))
    )
    (net (code "149") (name "unconnected-(U$1-Pad3V3-1)") (class "Default")
      (node (ref "U$1") (pin "3V3-1") (pinfunction "3V3-1_3V3-1") (pintype "bidirectional"))
    )
    (net (code "150") (name "unconnected-(U$1-Pad3V3-2)") (class "Default")
      (node (ref "U$1") (pin "3V3-2") (pinfunction "3V3-2_3V3-2") (pintype "bidirectional"))
    )
    (net (code "151") (name "unconnected-(U$1-Pad6-OUT1D)") (class "Default")
      (node (ref "U$1") (pin "6-OUT1D") (pinfunction "6-OUT1D_6-OUT1D") (pintype "bidirectional"))
    )
    (net (code "152") (name "unconnected-(U$1-Pad9-OUT1C)") (class "Default")
      (node (ref "U$1") (pin "9-OUT1C") (pinfunction "9-OUT1C_9-OUT1C") (pintype "bidirectional"))
    )
    (net (code "153") (name "unconnected-(U$1-Pad11-MOSI{slash}CTX1)") (class "Default")
      (node (ref "U$1") (pin "11-MOSI/CTX1") (pinfunction "11-MOSI/CTX1_11-MOSI/CTX1") (pintype "bidirectional"))
    )
    (net (code "154") (name "unconnected-(U$1-Pad13-SCK{slash}CRX1{slash}LED)") (class "Default")
      (node (ref "U$1") (pin "13-SCK/CRX1/LED") (pinfunction "13-SCK/CRX1/LED_13-SCK/CRX1/LED") (pintype "bidirectional"))
    )
    (net (code "155") (name "unconnected-(U$1-Pad18-A4{slash}SDA0)") (class "Default")
      (node (ref "U$1") (pin "18-A4/SDA0") (pinfunction "18-A4/SDA0_18-A4/SDA0") (pintype "bidirectional"))
    )
    (net (code "156") (name "unconnected-(U$1-Pad20-A6{slash}TX5{slash}LRCLK1)") (class "Default")
      (node (ref "U$1") (pin "20-A6/TX5/LRCLK1") (pinfunction "20-A6/TX5/LRCLK1_20-A6/TX5/LRCLK1") (pintype "bidirectional"))
    )
    (net (code "157") (name "unconnected-(U$1-Pad21-A7{slash}RX5{slash}BCLK1)") (class "Default")
      (node (ref "U$1") (pin "21-A7/RX5/BCLK1") (pinfunction "21-A7/RX5/BCLK1_21-A7/RX5/BCLK1") (pintype "bidirectional"))
    )
    (net (code "158") (name "unconnected-(U$1-Pad24-A10{slash}TX6{slash}SCL2)") (class "Default")
      (node (ref "U$1") (pin "24-A10/TX6/SCL2") (pinfunction "24-A10/TX6/SCL2_24-A10/TX6/SCL2") (pintype "bidirectional"))
    )
    (net (code "159") (name "unconnected-(U$1-Pad26-A12{slash}MOSI1)") (class "Default")
      (node (ref "U$1") (pin "26-A12/MOSI1") (pinfunction "26-A12/MOSI1_26-A12/MOSI1") (pintype "bidirectional"))
    )
    (net (code "160") (name "unconnected-(U$1-Pad27-A13{slash}SCK1)") (class "Default")
      (node (ref "U$1") (pin "27-A13/SCK1") (pinfunction "27-A13/SCK1_27-A13/SCK1") (pintype "bidirectional"))
    )
    (net (code "161") (name "unconnected-(U$1-Pad28-RX7)") (class "Default")
      (node (ref "U$1") (pin "28-RX7") (pinfunction "28-RX7_28-RX7") (pintype "bidirectional"))
    )
    (net (code "162") (name "unconnected-(U$1-Pad29-TX7)") (class "Default")
      (node (ref "U$1") (pin "29-TX7") (pinfunction "29-TX7_29-TX7") (pintype "bidirectional"))
    )
    (net (code "163") (name "unconnected-(U$1-Pad30-CRX3)") (class "Default")
      (node (ref "U$1") (pin "30-CRX3") (pinfunction "30-CRX3_30-CRX3") (pintype "bidirectional"))
    )
    (net (code "164") (name "unconnected-(U$1-Pad31-CTX3)") (class "Default")
      (node (ref "U$1") (pin "31-CTX3") (pinfunction "31-CTX3_31-CTX3") (pintype "bidirectional"))
    )
    (net (code "165") (name "unconnected-(U$1-Pad33-MCLK2)") (class "Default")
      (node (ref "U$1") (pin "33-MCLK2") (pinfunction "33-MCLK2_33-MCLK2") (pintype "bidirectional"))
    )
    (net (code "166") (name "unconnected-(U$1-PadON{slash}OFF)") (class "Default")
      (node (ref "U$1") (pin "ON/OFF") (pinfunction "ON/OFF_ON/OFF") (pintype "bidirectional"))
    )
    (net (code "167") (name "unconnected-(U$1-PadPROGRAM)") (class "Default")
      (node (ref "U$1") (pin "PROGRAM") (pinfunction "PROGRAM_PROGRAM") (pintype "bidirectional"))
    )
    (net (code "168") (name "unconnected-(U$1-PadVBAT)") (class "Default")
      (node (ref "U$1") (pin "VBAT") (pinfunction "VBAT_VBAT") (pintype "bidirectional"))
    )
  )
)
